# piezo-driver_v0_95-R004.net
KiCad netlist of a schematic drawn in EAGLE
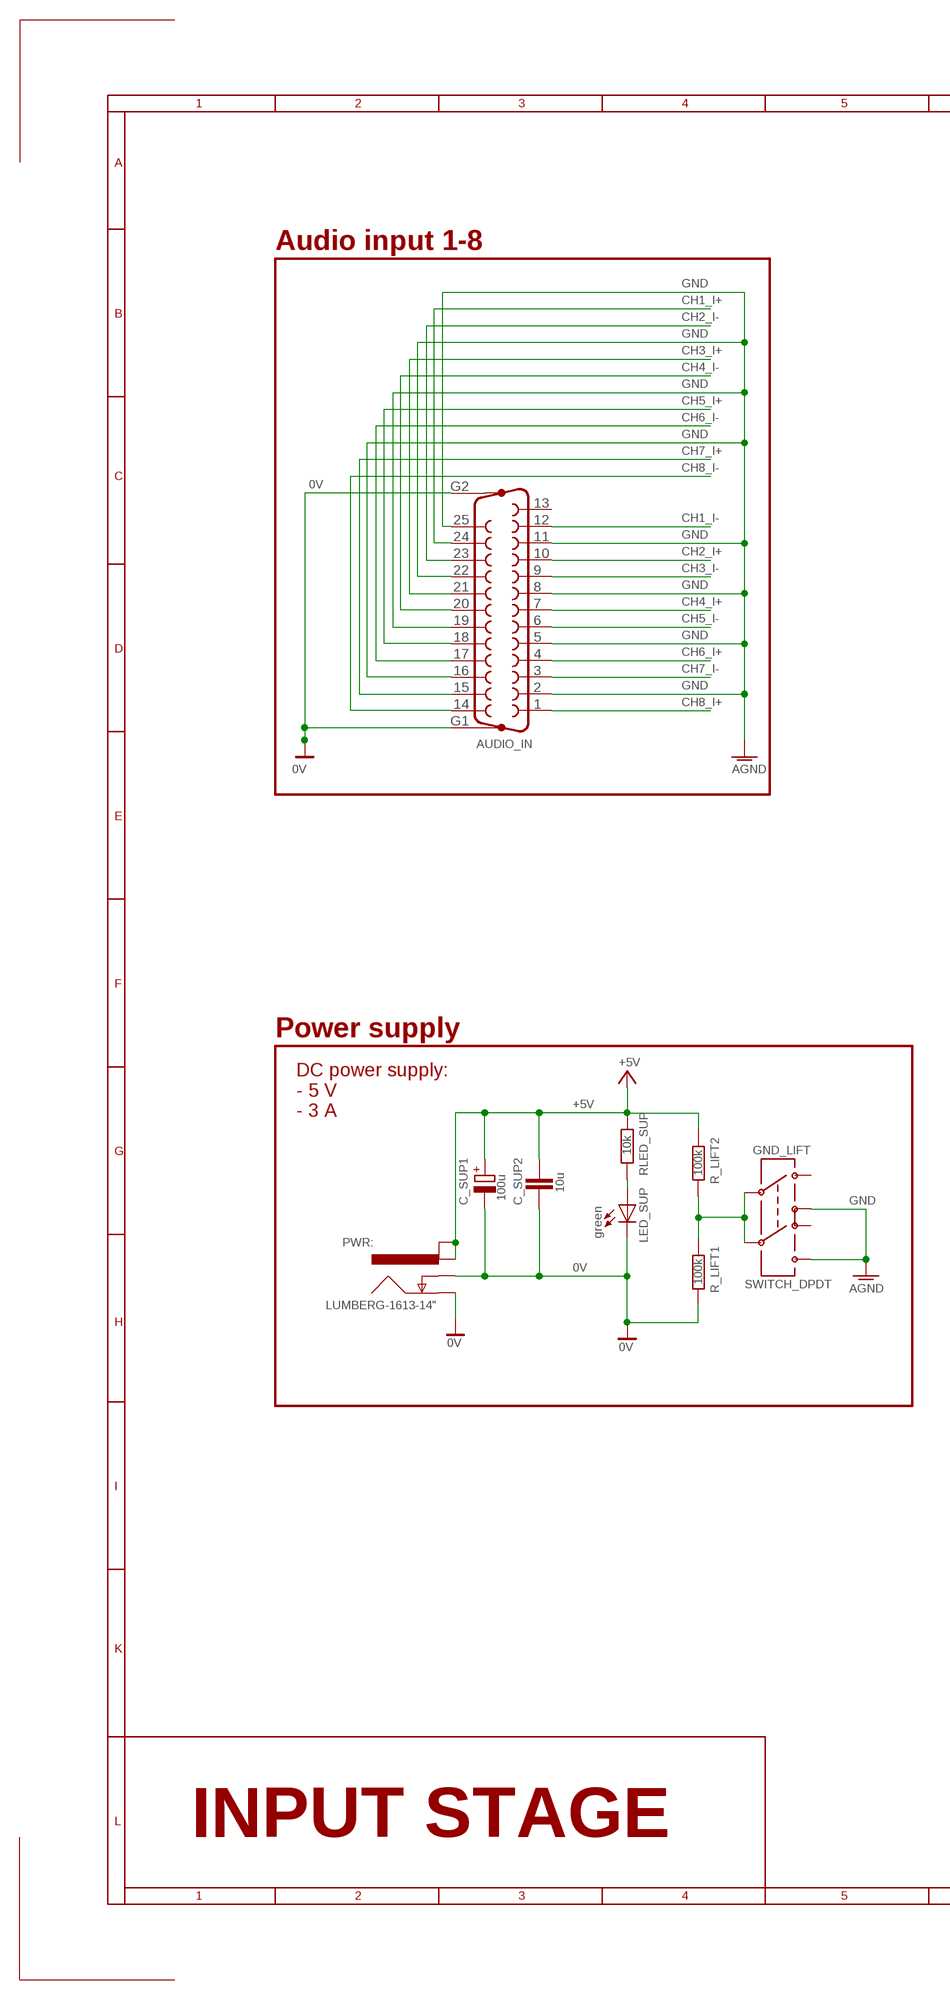
[diagram p0: schematic, sheet 1, part 1 of 2]
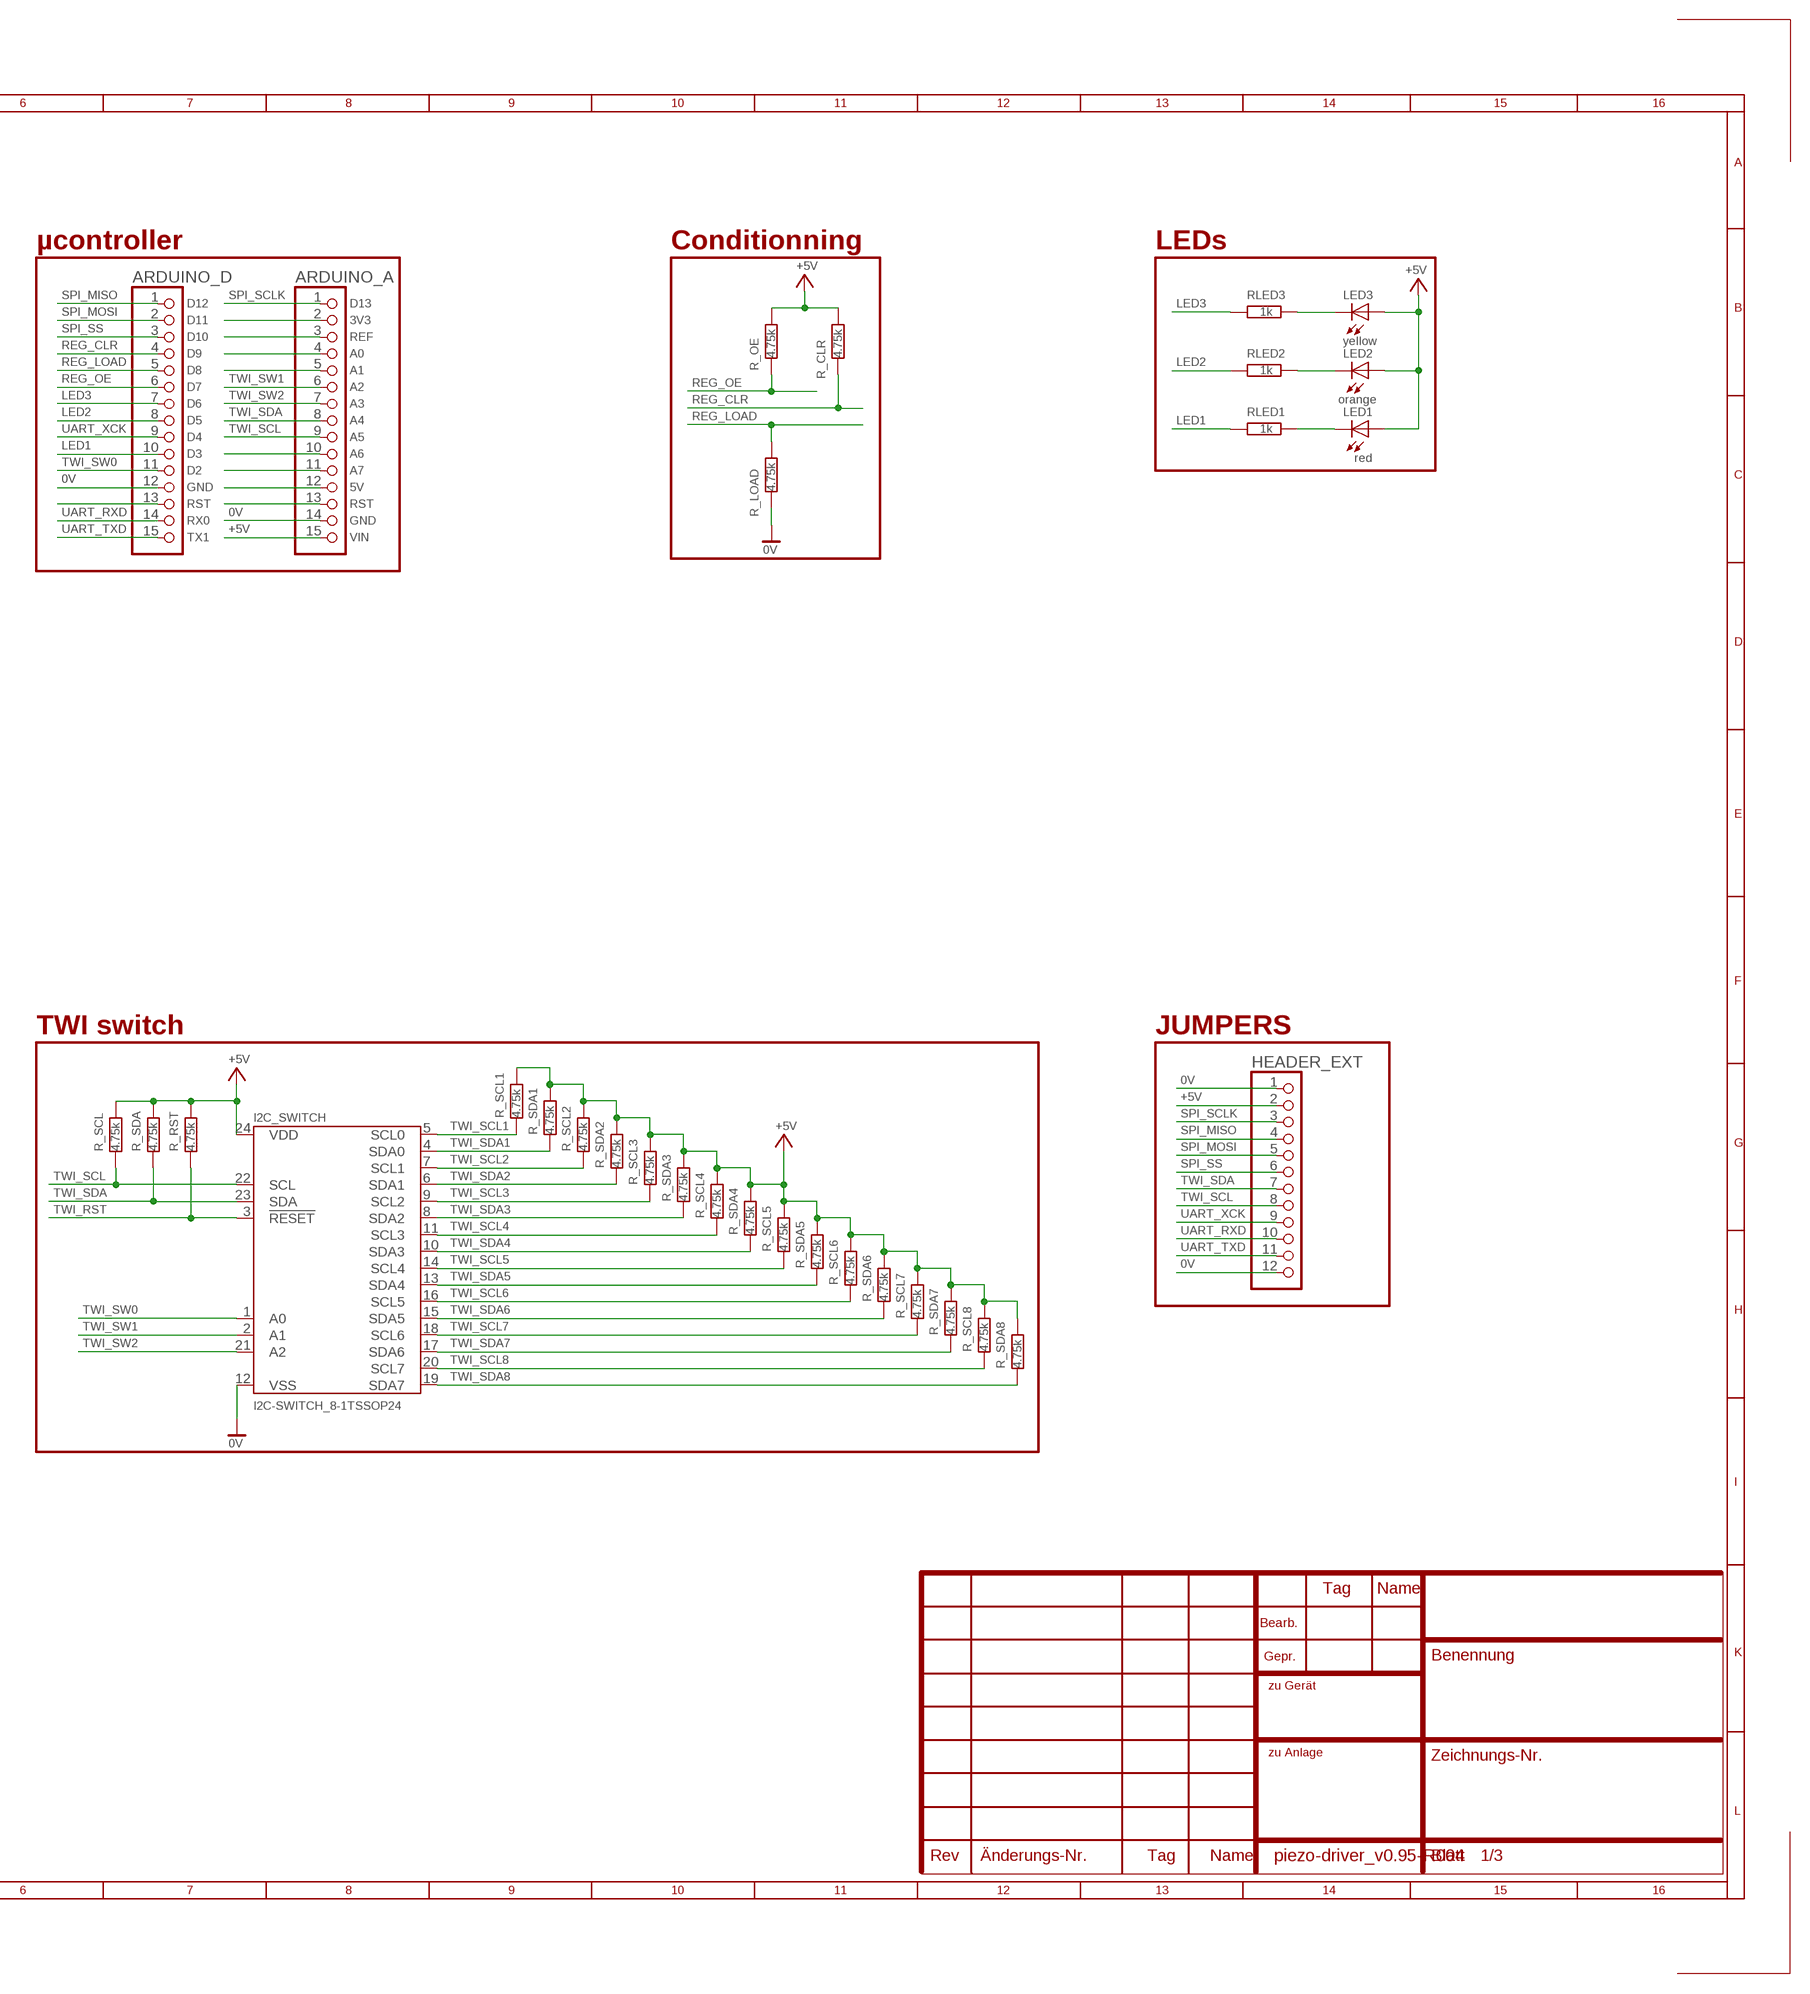
[diagram p1: schematic, sheet 1, part 2 of 2]
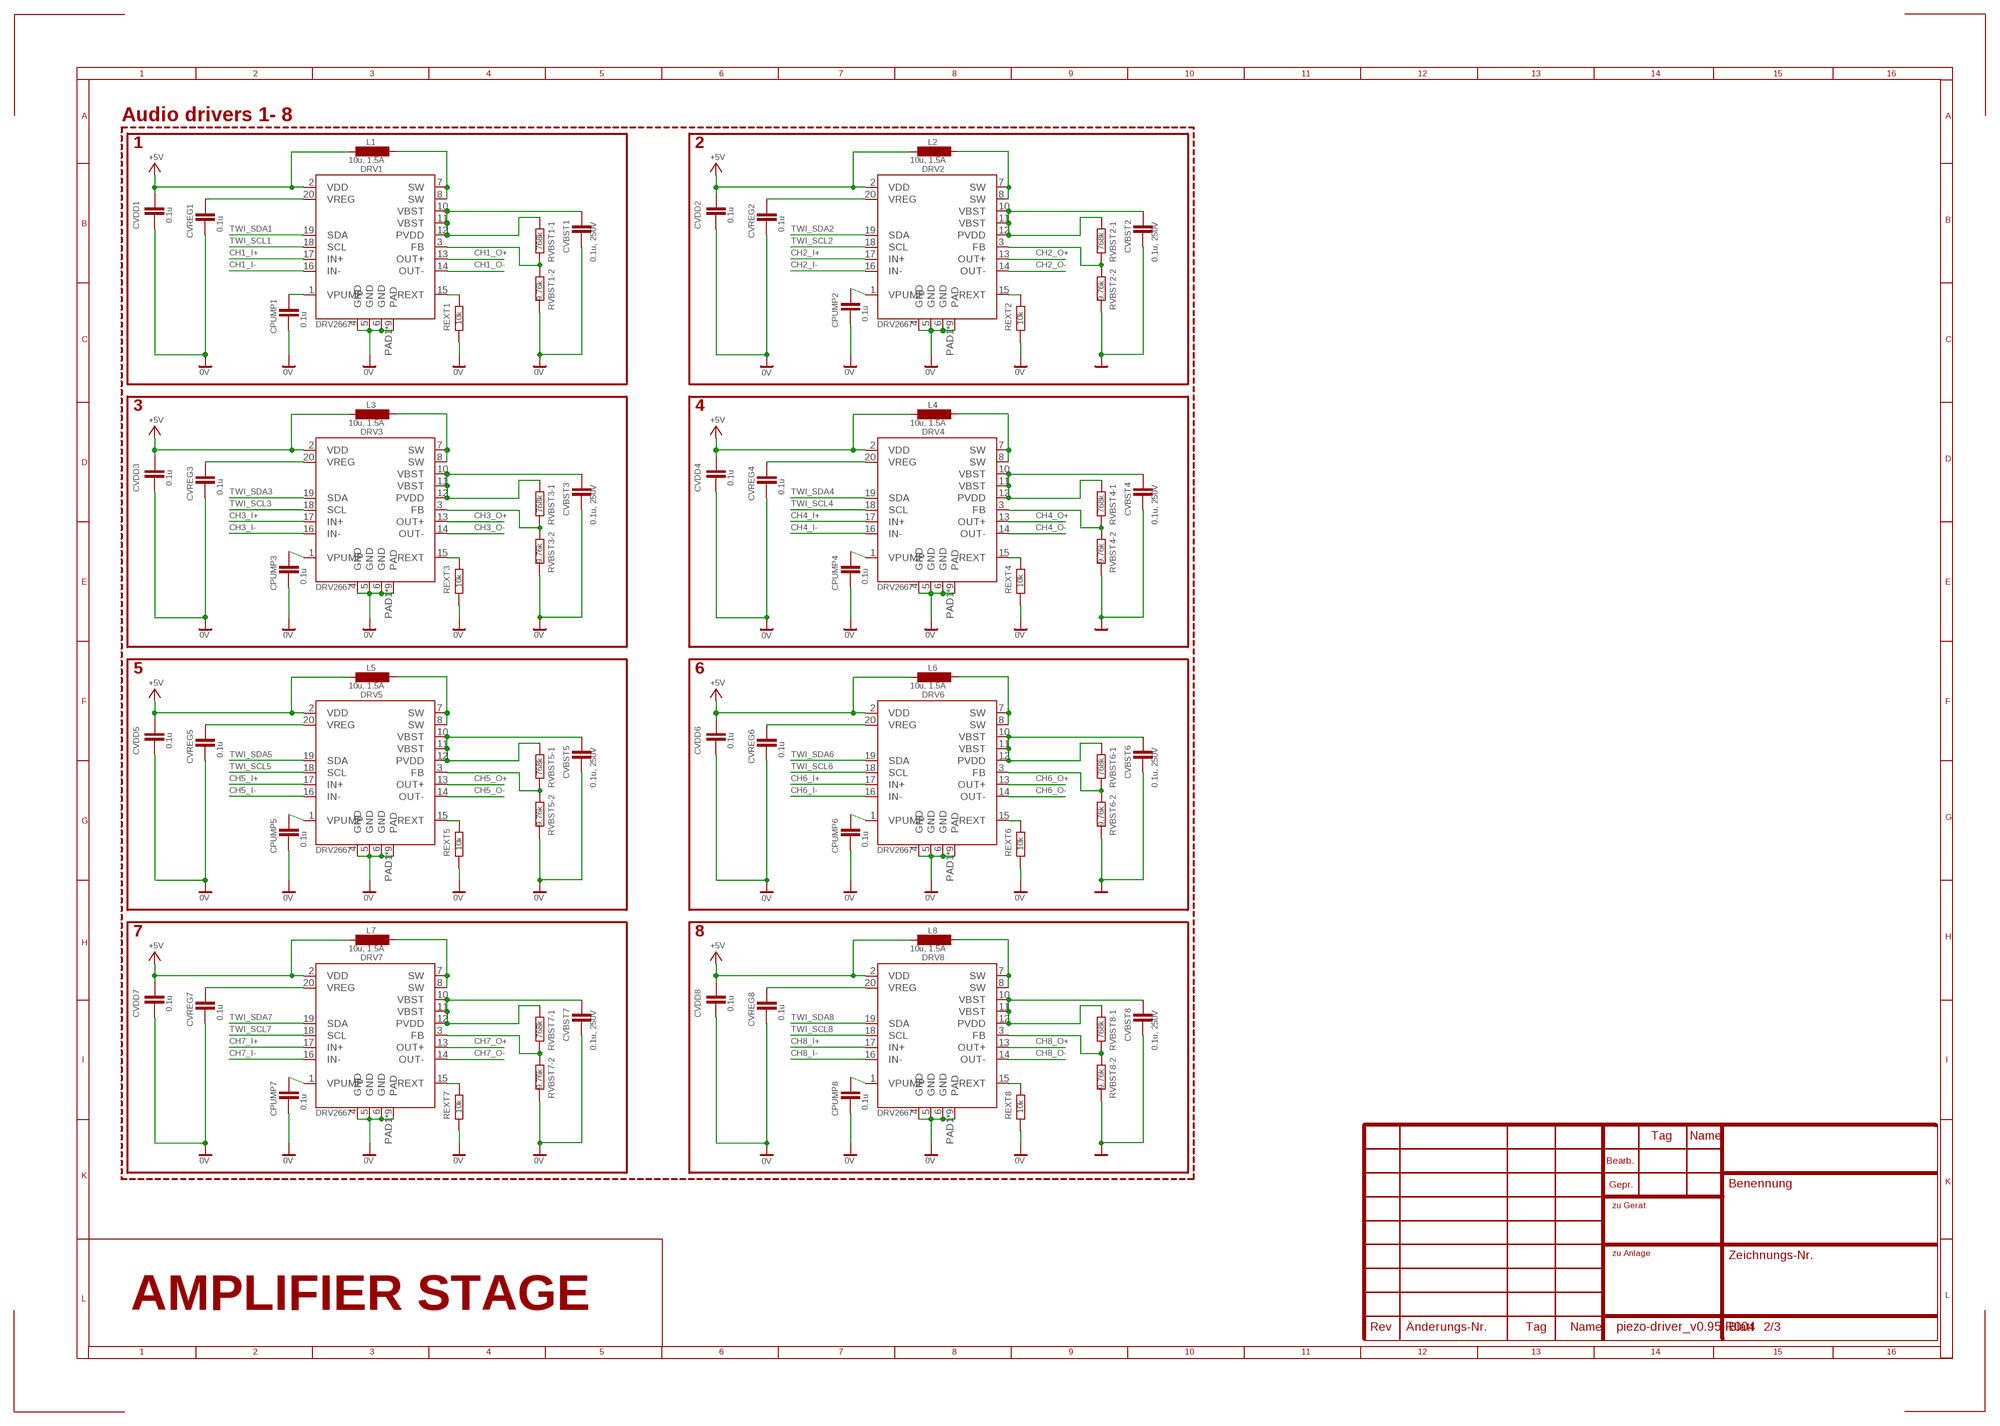
[diagram p2: schematic, sheet 2]
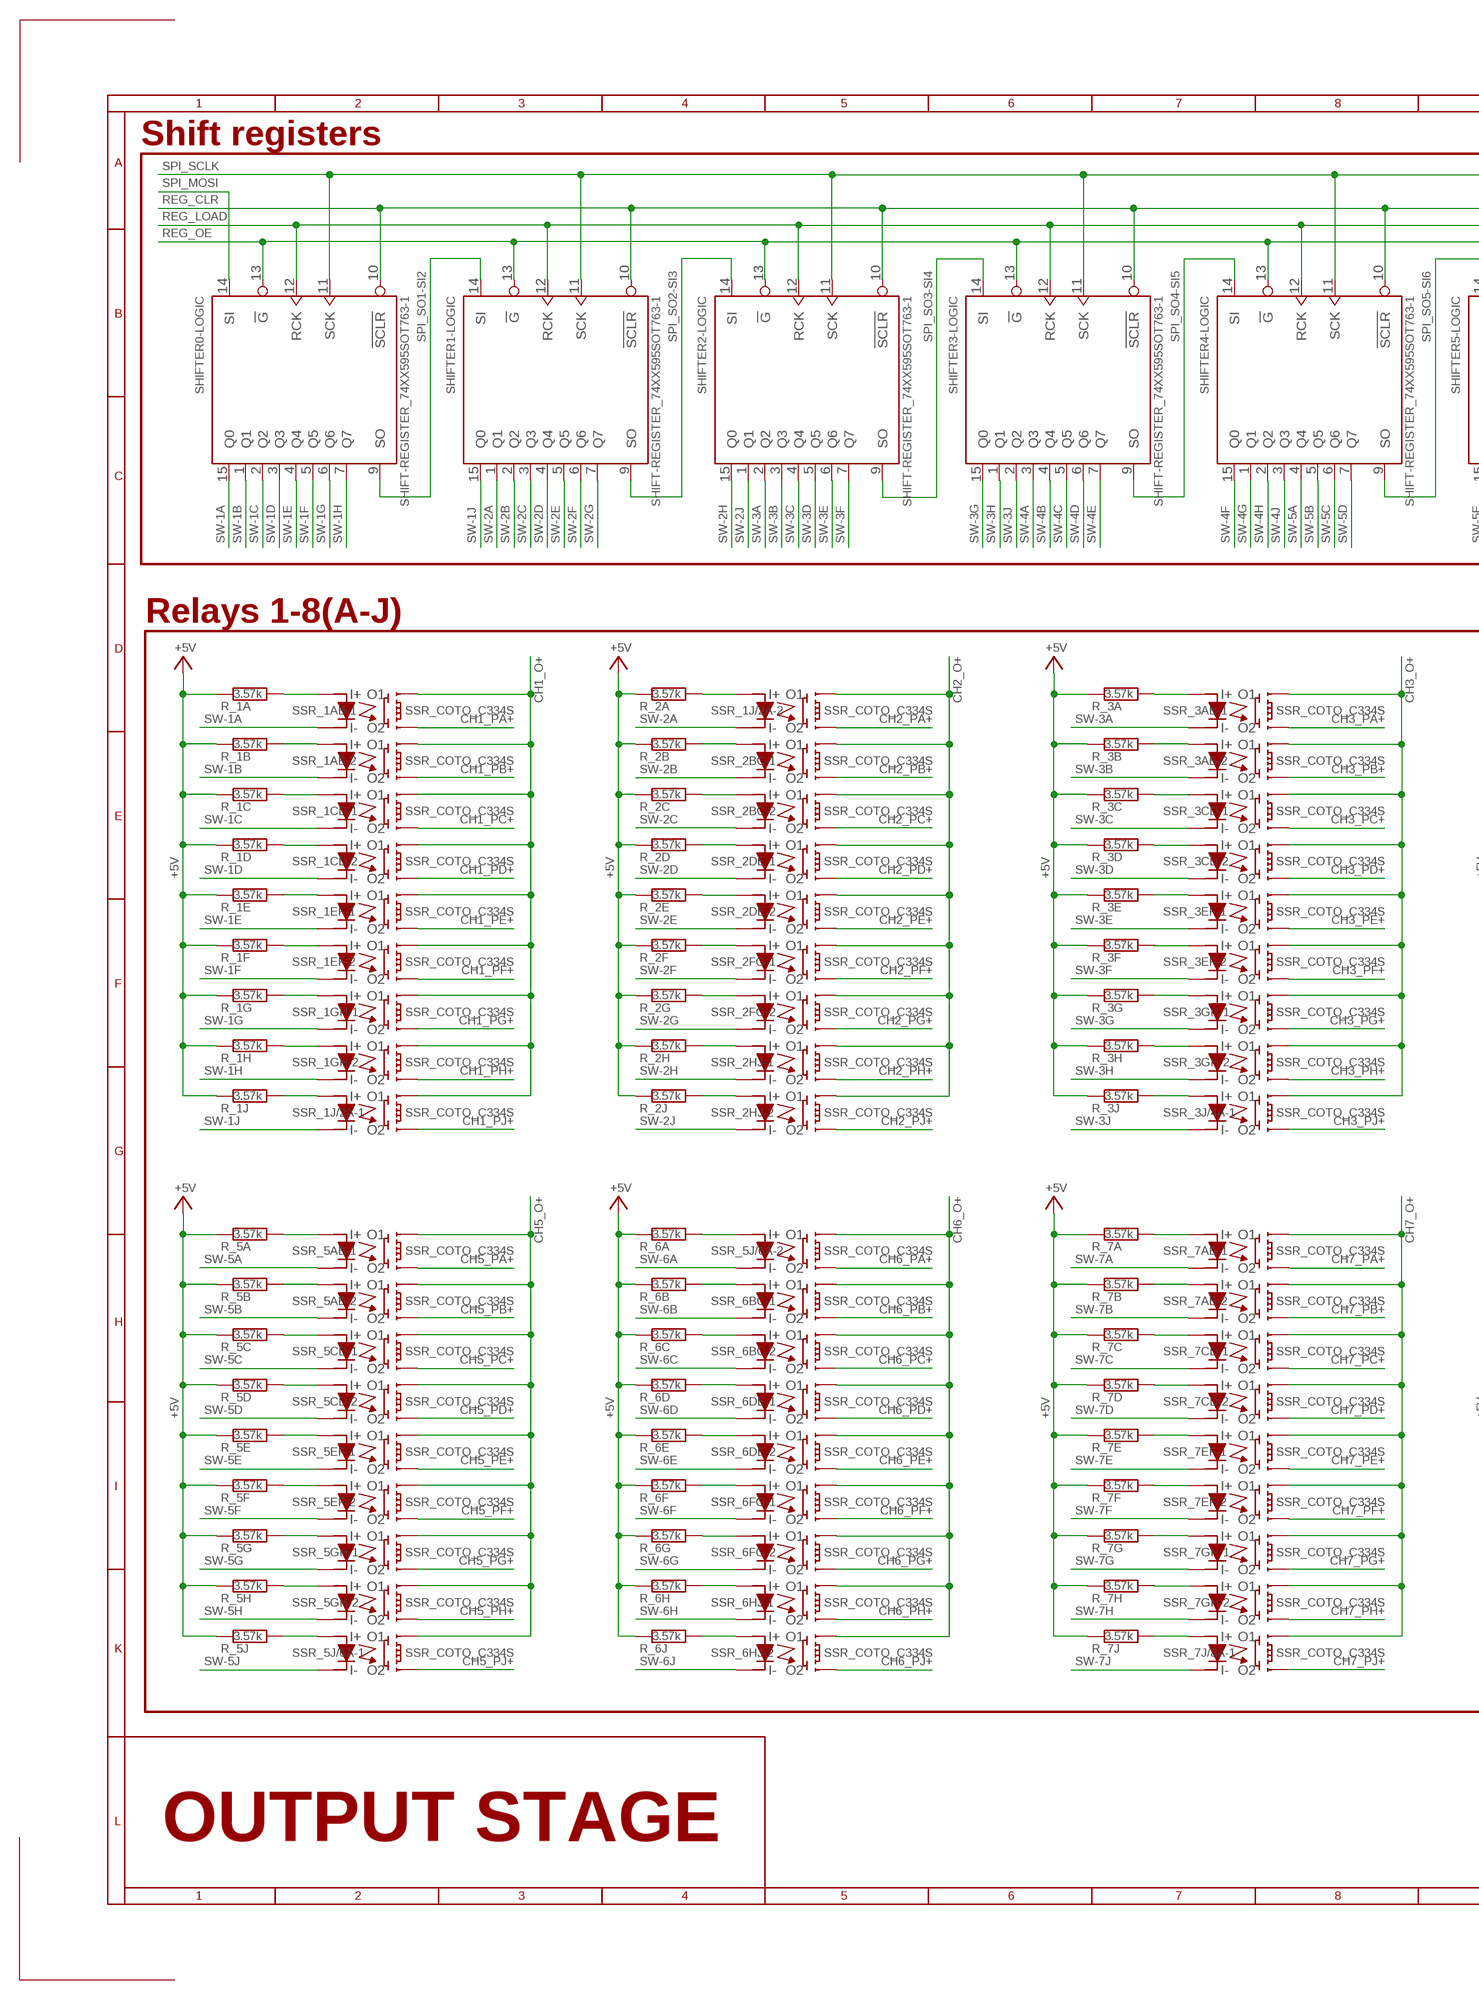
[diagram p3: schematic, sheet 3, part 1 of 2]
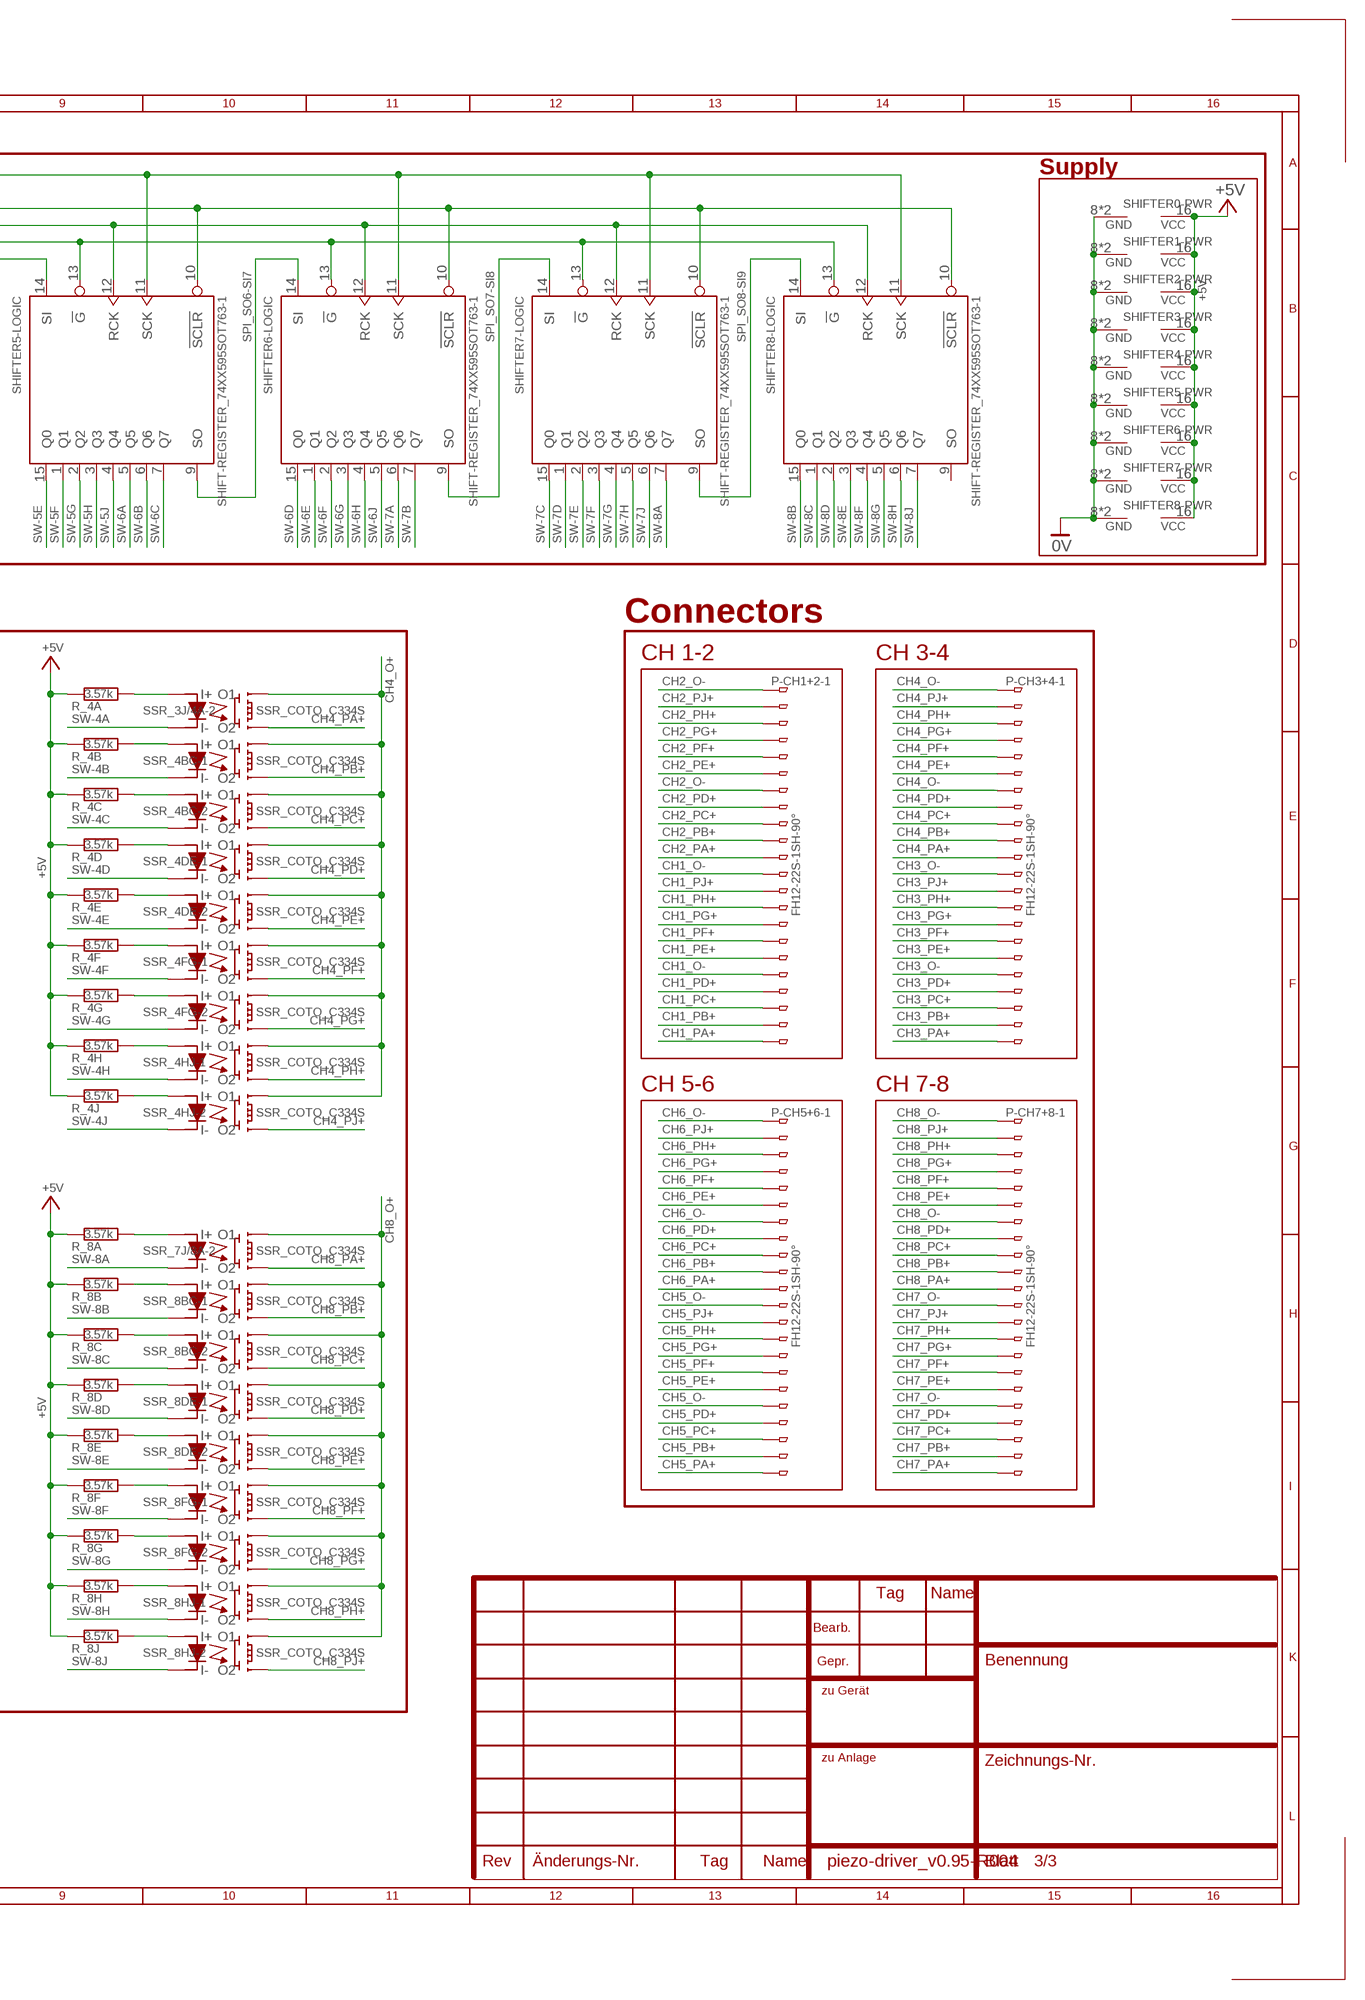
[diagram p4: schematic, sheet 3, part 2 of 2]

(export (version "E")
  (design (tool "Eeschema 10.0.6"))
  (components
    (comp (ref "CPUMP1")
      (value "0.1u")
      (footprint "eagle-import:C0402")
      (libsource (lib "eagle-import") (part "C-EUC0402"))
    )
    (comp (ref "CPUMP2")
      (value "0.1u")
      (footprint "eagle-import:C0402")
      (libsource (lib "eagle-import") (part "C-EUC0402"))
    )
    (comp (ref "CPUMP3")
      (value "0.1u")
      (footprint "eagle-import:C0402")
      (libsource (lib "eagle-import") (part "C-EUC0402"))
    )
    (comp (ref "CPUMP4")
      (value "0.1u")
      (footprint "eagle-import:C0402")
      (libsource (lib "eagle-import") (part "C-EUC0402"))
    )
    (comp (ref "CPUMP5")
      (value "0.1u")
      (footprint "eagle-import:C0402")
      (libsource (lib "eagle-import") (part "C-EUC0402"))
    )
    (comp (ref "CPUMP6")
      (value "0.1u")
      (footprint "eagle-import:C0402")
      (libsource (lib "eagle-import") (part "C-EUC0402"))
    )
    (comp (ref "CPUMP7")
      (value "0.1u")
      (footprint "eagle-import:C0402")
      (libsource (lib "eagle-import") (part "C-EUC0402"))
    )
    (comp (ref "CPUMP8")
      (value "0.1u")
      (footprint "eagle-import:C0402")
      (libsource (lib "eagle-import") (part "C-EUC0402"))
    )
    (comp (ref "CVBST1")
      (value "0.1u, 250V")
      (footprint "eagle-import:C0805")
      (libsource (lib "eagle-import") (part "C-EUC0805"))
    )
    (comp (ref "CVBST2")
      (value "0.1u, 250V")
      (footprint "eagle-import:C0805")
      (libsource (lib "eagle-import") (part "C-EUC0805"))
    )
    (comp (ref "CVBST3")
      (value "0.1u, 250V")
      (footprint "eagle-import:C0805")
      (libsource (lib "eagle-import") (part "C-EUC0805"))
    )
    (comp (ref "CVBST4")
      (value "0.1u, 250V")
      (footprint "eagle-import:C0805")
      (libsource (lib "eagle-import") (part "C-EUC0805"))
    )
    (comp (ref "CVBST5")
      (value "0.1u, 250V")
      (footprint "eagle-import:C0805")
      (libsource (lib "eagle-import") (part "C-EUC0805"))
    )
    (comp (ref "CVBST6")
      (value "0.1u, 250V")
      (footprint "eagle-import:C0805")
      (libsource (lib "eagle-import") (part "C-EUC0805"))
    )
    (comp (ref "CVBST7")
      (value "0.1u, 250V")
      (footprint "eagle-import:C0805")
      (libsource (lib "eagle-import") (part "C-EUC0805"))
    )
    (comp (ref "CVBST8")
      (value "0.1u, 250V")
      (footprint "eagle-import:C0805")
      (libsource (lib "eagle-import") (part "C-EUC0805"))
    )
    (comp (ref "CVDD1")
      (value "0.1u")
      (footprint "eagle-import:C0402")
      (libsource (lib "eagle-import") (part "C-EUC0402"))
    )
    (comp (ref "CVDD2")
      (value "0.1u")
      (footprint "eagle-import:C0402")
      (libsource (lib "eagle-import") (part "C-EUC0402"))
    )
    (comp (ref "CVDD3")
      (value "0.1u")
      (footprint "eagle-import:C0402")
      (libsource (lib "eagle-import") (part "C-EUC0402"))
    )
    (comp (ref "CVDD4")
      (value "0.1u")
      (footprint "eagle-import:C0402")
      (libsource (lib "eagle-import") (part "C-EUC0402"))
    )
    (comp (ref "CVDD5")
      (value "0.1u")
      (footprint "eagle-import:C0402")
      (libsource (lib "eagle-import") (part "C-EUC0402"))
    )
    (comp (ref "CVDD6")
      (value "0.1u")
      (footprint "eagle-import:C0402")
      (libsource (lib "eagle-import") (part "C-EUC0402"))
    )
    (comp (ref "CVDD7")
      (value "0.1u")
      (footprint "eagle-import:C0402")
      (libsource (lib "eagle-import") (part "C-EUC0402"))
    )
    (comp (ref "CVDD8")
      (value "0.1u")
      (footprint "eagle-import:C0402")
      (libsource (lib "eagle-import") (part "C-EUC0402"))
    )
    (comp (ref "CVREG1")
      (value "0.1u")
      (footprint "eagle-import:C0402")
      (libsource (lib "eagle-import") (part "C-EUC0402"))
    )
    (comp (ref "CVREG2")
      (value "0.1u")
      (footprint "eagle-import:C0402")
      (libsource (lib "eagle-import") (part "C-EUC0402"))
    )
    (comp (ref "CVREG3")
      (value "0.1u")
      (footprint "eagle-import:C0402")
      (libsource (lib "eagle-import") (part "C-EUC0402"))
    )
    (comp (ref "CVREG4")
      (value "0.1u")
      (footprint "eagle-import:C0402")
      (libsource (lib "eagle-import") (part "C-EUC0402"))
    )
    (comp (ref "CVREG5")
      (value "0.1u")
      (footprint "eagle-import:C0402")
      (libsource (lib "eagle-import") (part "C-EUC0402"))
    )
    (comp (ref "CVREG6")
      (value "0.1u")
      (footprint "eagle-import:C0402")
      (libsource (lib "eagle-import") (part "C-EUC0402"))
    )
    (comp (ref "CVREG7")
      (value "0.1u")
      (footprint "eagle-import:C0402")
      (libsource (lib "eagle-import") (part "C-EUC0402"))
    )
    (comp (ref "CVREG8")
      (value "0.1u")
      (footprint "eagle-import:C0402")
      (libsource (lib "eagle-import") (part "C-EUC0402"))
    )
    (comp (ref "DRV1")
      (value "DRV2667")
      (footprint "eagle-import:QFN-20_9TH")
      (libsource (lib "eagle-import") (part "DRV2667"))
    )
    (comp (ref "DRV2")
      (value "DRV2667")
      (footprint "eagle-import:QFN-20_9TH")
      (libsource (lib "eagle-import") (part "DRV2667"))
    )
    (comp (ref "DRV3")
      (value "DRV2667")
      (footprint "eagle-import:QFN-20_9TH")
      (libsource (lib "eagle-import") (part "DRV2667"))
    )
    (comp (ref "DRV4")
      (value "DRV2667")
      (footprint "eagle-import:QFN-20_9TH")
      (libsource (lib "eagle-import") (part "DRV2667"))
    )
    (comp (ref "DRV5")
      (value "DRV2667")
      (footprint "eagle-import:QFN-20_9TH")
      (libsource (lib "eagle-import") (part "DRV2667"))
    )
    (comp (ref "DRV6")
      (value "DRV2667")
      (footprint "eagle-import:QFN-20_9TH")
      (libsource (lib "eagle-import") (part "DRV2667"))
    )
    (comp (ref "DRV7")
      (value "DRV2667")
      (footprint "eagle-import:QFN-20_9TH")
      (libsource (lib "eagle-import") (part "DRV2667"))
    )
    (comp (ref "DRV8")
      (value "DRV2667")
      (footprint "eagle-import:QFN-20_9TH")
      (libsource (lib "eagle-import") (part "DRV2667"))
    )
    (comp (ref "L1")
      (value "10u, 1.5A")
      (footprint "eagle-import:L4.0X4.0")
      (libsource (lib "eagle-import") (part "L-EU4.0X4.0"))
    )
    (comp (ref "L2")
      (value "10u, 1.5A")
      (footprint "eagle-import:L4.0X4.0")
      (libsource (lib "eagle-import") (part "L-EU4.0X4.0"))
    )
    (comp (ref "L3")
      (value "10u, 1.5A")
      (footprint "eagle-import:L4.0X4.0")
      (libsource (lib "eagle-import") (part "L-EU4.0X4.0"))
    )
    (comp (ref "L4")
      (value "10u, 1.5A")
      (footprint "eagle-import:L4.0X4.0")
      (libsource (lib "eagle-import") (part "L-EU4.0X4.0"))
    )
    (comp (ref "L5")
      (value "10u, 1.5A")
      (footprint "eagle-import:L4.0X4.0")
      (libsource (lib "eagle-import") (part "L-EU4.0X4.0"))
    )
    (comp (ref "L6")
      (value "10u, 1.5A")
      (footprint "eagle-import:L4.0X4.0")
      (libsource (lib "eagle-import") (part "L-EU4.0X4.0"))
    )
    (comp (ref "L7")
      (value "10u, 1.5A")
      (footprint "eagle-import:L4.0X4.0")
      (libsource (lib "eagle-import") (part "L-EU4.0X4.0"))
    )
    (comp (ref "L8")
      (value "10u, 1.5A")
      (footprint "eagle-import:L4.0X4.0")
      (libsource (lib "eagle-import") (part "L-EU4.0X4.0"))
    )
    (comp (ref "REXT1")
      (value "10k")
      (footprint "eagle-import:R0402")
      (libsource (lib "eagle-import") (part "R-EU_R0402"))
    )
    (comp (ref "REXT2")
      (value "10k")
      (footprint "eagle-import:R0402")
      (libsource (lib "eagle-import") (part "R-EU_R0402"))
    )
    (comp (ref "REXT3")
      (value "10k")
      (footprint "eagle-import:R0402")
      (libsource (lib "eagle-import") (part "R-EU_R0402"))
    )
    (comp (ref "REXT4")
      (value "10k")
      (footprint "eagle-import:R0402")
      (libsource (lib "eagle-import") (part "R-EU_R0402"))
    )
    (comp (ref "REXT5")
      (value "10k")
      (footprint "eagle-import:R0402")
      (libsource (lib "eagle-import") (part "R-EU_R0402"))
    )
    (comp (ref "REXT6")
      (value "10k")
      (footprint "eagle-import:R0402")
      (libsource (lib "eagle-import") (part "R-EU_R0402"))
    )
    (comp (ref "REXT7")
      (value "10k")
      (footprint "eagle-import:R0402")
      (libsource (lib "eagle-import") (part "R-EU_R0402"))
    )
    (comp (ref "REXT8")
      (value "10k")
      (footprint "eagle-import:R0402")
      (libsource (lib "eagle-import") (part "R-EU_R0402"))
    )
    (comp (ref "RVBST1-1")
      (value "768k")
      (footprint "eagle-import:R0402")
      (libsource (lib "eagle-import") (part "R-EU_R0402"))
    )
    (comp (ref "RVBST1-2")
      (value "9.76k")
      (footprint "eagle-import:R0402")
      (libsource (lib "eagle-import") (part "R-EU_R0402"))
    )
    (comp (ref "RVBST2-1")
      (value "768k")
      (footprint "eagle-import:R0402")
      (libsource (lib "eagle-import") (part "R-EU_R0402"))
    )
    (comp (ref "RVBST2-2")
      (value "9.76k")
      (footprint "eagle-import:R0402")
      (libsource (lib "eagle-import") (part "R-EU_R0402"))
    )
    (comp (ref "RVBST3-1")
      (value "768k")
      (footprint "eagle-import:R0402")
      (libsource (lib "eagle-import") (part "R-EU_R0402"))
    )
    (comp (ref "RVBST3-2")
      (value "9.76k")
      (footprint "eagle-import:R0402")
      (libsource (lib "eagle-import") (part "R-EU_R0402"))
    )
    (comp (ref "RVBST4-1")
      (value "768k")
      (footprint "eagle-import:R0402")
      (libsource (lib "eagle-import") (part "R-EU_R0402"))
    )
    (comp (ref "RVBST4-2")
      (value "9.76k")
      (footprint "eagle-import:R0402")
      (libsource (lib "eagle-import") (part "R-EU_R0402"))
    )
    (comp (ref "RVBST5-1")
      (value "768k")
      (footprint "eagle-import:R0402")
      (libsource (lib "eagle-import") (part "R-EU_R0402"))
    )
    (comp (ref "RVBST5-2")
      (value "9.76k")
      (footprint "eagle-import:R0402")
      (libsource (lib "eagle-import") (part "R-EU_R0402"))
    )
    (comp (ref "RVBST6-1")
      (value "768k")
      (footprint "eagle-import:R0402")
      (libsource (lib "eagle-import") (part "R-EU_R0402"))
    )
    (comp (ref "RVBST6-2")
      (value "9.76k")
      (footprint "eagle-import:R0402")
      (libsource (lib "eagle-import") (part "R-EU_R0402"))
    )
    (comp (ref "RVBST7-1")
      (value "768k")
      (footprint "eagle-import:R0402")
      (libsource (lib "eagle-import") (part "R-EU_R0402"))
    )
    (comp (ref "RVBST7-2")
      (value "9.76k")
      (footprint "eagle-import:R0402")
      (libsource (lib "eagle-import") (part "R-EU_R0402"))
    )
    (comp (ref "RVBST8-1")
      (value "768k")
      (footprint "eagle-import:R0402")
      (libsource (lib "eagle-import") (part "R-EU_R0402"))
    )
    (comp (ref "RVBST8-2")
      (value "9.76k")
      (footprint "eagle-import:R0402")
      (libsource (lib "eagle-import") (part "R-EU_R0402"))
    )
    (comp (ref "P-CH1+2")
      (value "FH12-22S-1SH-90°")
      (footprint "eagle-import:FH12-22S-1SH")
      (libsource (lib "eagle-import") (part "FH12-22S-1SH-90°"))
    )
    (comp (ref "P-CH3+4")
      (value "FH12-22S-1SH-90°")
      (footprint "eagle-import:FH12-22S-1SH")
      (libsource (lib "eagle-import") (part "FH12-22S-1SH-90°"))
    )
    (comp (ref "P-CH5+6")
      (value "FH12-22S-1SH-90°")
      (footprint "eagle-import:FH12-22S-1SH")
      (libsource (lib "eagle-import") (part "FH12-22S-1SH-90°"))
    )
    (comp (ref "P-CH7+8")
      (value "FH12-22S-1SH-90°")
      (footprint "eagle-import:FH12-22S-1SH")
      (libsource (lib "eagle-import") (part "FH12-22S-1SH-90°"))
    )
    (comp (ref "R_1A")
      (value "3.57k")
      (footprint "eagle-import:R0402")
      (libsource (lib "eagle-import") (part "R-EU_R0402"))
    )
    (comp (ref "R_1B")
      (value "3.57k")
      (footprint "eagle-import:R0402")
      (libsource (lib "eagle-import") (part "R-EU_R0402"))
    )
    (comp (ref "R_1C")
      (value "3.57k")
      (footprint "eagle-import:R0402")
      (libsource (lib "eagle-import") (part "R-EU_R0402"))
    )
    (comp (ref "R_1D")
      (value "3.57k")
      (footprint "eagle-import:R0402")
      (libsource (lib "eagle-import") (part "R-EU_R0402"))
    )
    (comp (ref "R_1E")
      (value "3.57k")
      (footprint "eagle-import:R0402")
      (libsource (lib "eagle-import") (part "R-EU_R0402"))
    )
    (comp (ref "R_1F")
      (value "3.57k")
      (footprint "eagle-import:R0402")
      (libsource (lib "eagle-import") (part "R-EU_R0402"))
    )
    (comp (ref "R_1G")
      (value "3.57k")
      (footprint "eagle-import:R0402")
      (libsource (lib "eagle-import") (part "R-EU_R0402"))
    )
    (comp (ref "R_1H")
      (value "3.57k")
      (footprint "eagle-import:R0402")
      (libsource (lib "eagle-import") (part "R-EU_R0402"))
    )
    (comp (ref "R_1J")
      (value "3.57k")
      (footprint "eagle-import:R0402")
      (libsource (lib "eagle-import") (part "R-EU_R0402"))
    )
    (comp (ref "R_2A")
      (value "3.57k")
      (footprint "eagle-import:R0402")
      (libsource (lib "eagle-import") (part "R-EU_R0402"))
    )
    (comp (ref "R_2B")
      (value "3.57k")
      (footprint "eagle-import:R0402")
      (libsource (lib "eagle-import") (part "R-EU_R0402"))
    )
    (comp (ref "R_2C")
      (value "3.57k")
      (footprint "eagle-import:R0402")
      (libsource (lib "eagle-import") (part "R-EU_R0402"))
    )
    (comp (ref "R_2D")
      (value "3.57k")
      (footprint "eagle-import:R0402")
      (libsource (lib "eagle-import") (part "R-EU_R0402"))
    )
    (comp (ref "R_2E")
      (value "3.57k")
      (footprint "eagle-import:R0402")
      (libsource (lib "eagle-import") (part "R-EU_R0402"))
    )
    (comp (ref "R_2F")
      (value "3.57k")
      (footprint "eagle-import:R0402")
      (libsource (lib "eagle-import") (part "R-EU_R0402"))
    )
    (comp (ref "R_2G")
      (value "3.57k")
      (footprint "eagle-import:R0402")
      (libsource (lib "eagle-import") (part "R-EU_R0402"))
    )
    (comp (ref "R_2H")
      (value "3.57k")
      (footprint "eagle-import:R0402")
      (libsource (lib "eagle-import") (part "R-EU_R0402"))
    )
    (comp (ref "R_2J")
      (value "3.57k")
      (footprint "eagle-import:R0402")
      (libsource (lib "eagle-import") (part "R-EU_R0402"))
    )
    (comp (ref "R_3A")
      (value "3.57k")
      (footprint "eagle-import:R0402")
      (libsource (lib "eagle-import") (part "R-EU_R0402"))
    )
    (comp (ref "R_3B")
      (value "3.57k")
      (footprint "eagle-import:R0402")
      (libsource (lib "eagle-import") (part "R-EU_R0402"))
    )
    (comp (ref "R_3C")
      (value "3.57k")
      (footprint "eagle-import:R0402")
      (libsource (lib "eagle-import") (part "R-EU_R0402"))
    )
    (comp (ref "R_3D")
      (value "3.57k")
      (footprint "eagle-import:R0402")
      (libsource (lib "eagle-import") (part "R-EU_R0402"))
    )
    (comp (ref "R_3E")
      (value "3.57k")
      (footprint "eagle-import:R0402")
      (libsource (lib "eagle-import") (part "R-EU_R0402"))
    )
    (comp (ref "R_3F")
      (value "3.57k")
      (footprint "eagle-import:R0402")
      (libsource (lib "eagle-import") (part "R-EU_R0402"))
    )
    (comp (ref "R_3G")
      (value "3.57k")
      (footprint "eagle-import:R0402")
      (libsource (lib "eagle-import") (part "R-EU_R0402"))
    )
    (comp (ref "R_3H")
      (value "3.57k")
      (footprint "eagle-import:R0402")
      (libsource (lib "eagle-import") (part "R-EU_R0402"))
    )
    (comp (ref "R_3J")
      (value "3.57k")
      (footprint "eagle-import:R0402")
      (libsource (lib "eagle-import") (part "R-EU_R0402"))
    )
    (comp (ref "R_4A")
      (value "3.57k")
      (footprint "eagle-import:R0402")
      (libsource (lib "eagle-import") (part "R-EU_R0402"))
    )
    (comp (ref "R_4B")
      (value "3.57k")
      (footprint "eagle-import:R0402")
      (libsource (lib "eagle-import") (part "R-EU_R0402"))
    )
    (comp (ref "R_4C")
      (value "3.57k")
      (footprint "eagle-import:R0402")
      (libsource (lib "eagle-import") (part "R-EU_R0402"))
    )
    (comp (ref "R_4D")
      (value "3.57k")
      (footprint "eagle-import:R0402")
      (libsource (lib "eagle-import") (part "R-EU_R0402"))
    )
    (comp (ref "R_4E")
      (value "3.57k")
      (footprint "eagle-import:R0402")
      (libsource (lib "eagle-import") (part "R-EU_R0402"))
    )
    (comp (ref "R_4F")
      (value "3.57k")
      (footprint "eagle-import:R0402")
      (libsource (lib "eagle-import") (part "R-EU_R0402"))
    )
    (comp (ref "R_4G")
      (value "3.57k")
      (footprint "eagle-import:R0402")
      (libsource (lib "eagle-import") (part "R-EU_R0402"))
    )
    (comp (ref "R_4H")
      (value "3.57k")
      (footprint "eagle-import:R0402")
      (libsource (lib "eagle-import") (part "R-EU_R0402"))
    )
    (comp (ref "R_4J")
      (value "3.57k")
      (footprint "eagle-import:R0402")
      (libsource (lib "eagle-import") (part "R-EU_R0402"))
    )
    (comp (ref "R_5A")
      (value "3.57k")
      (footprint "eagle-import:R0402")
      (libsource (lib "eagle-import") (part "R-EU_R0402"))
    )
    (comp (ref "R_5B")
      (value "3.57k")
      (footprint "eagle-import:R0402")
      (libsource (lib "eagle-import") (part "R-EU_R0402"))
    )
    (comp (ref "R_5C")
      (value "3.57k")
      (footprint "eagle-import:R0402")
      (libsource (lib "eagle-import") (part "R-EU_R0402"))
    )
    (comp (ref "R_5D")
      (value "3.57k")
      (footprint "eagle-import:R0402")
      (libsource (lib "eagle-import") (part "R-EU_R0402"))
    )
    (comp (ref "R_5E")
      (value "3.57k")
      (footprint "eagle-import:R0402")
      (libsource (lib "eagle-import") (part "R-EU_R0402"))
    )
    (comp (ref "R_5F")
      (value "3.57k")
      (footprint "eagle-import:R0402")
      (libsource (lib "eagle-import") (part "R-EU_R0402"))
    )
    (comp (ref "R_5G")
      (value "3.57k")
      (footprint "eagle-import:R0402")
      (libsource (lib "eagle-import") (part "R-EU_R0402"))
    )
    (comp (ref "R_5H")
      (value "3.57k")
      (footprint "eagle-import:R0402")
      (libsource (lib "eagle-import") (part "R-EU_R0402"))
    )
    (comp (ref "R_5J")
      (value "3.57k")
      (footprint "eagle-import:R0402")
      (libsource (lib "eagle-import") (part "R-EU_R0402"))
    )
    (comp (ref "R_6A")
      (value "3.57k")
      (footprint "eagle-import:R0402")
      (libsource (lib "eagle-import") (part "R-EU_R0402"))
    )
    (comp (ref "R_6B")
      (value "3.57k")
      (footprint "eagle-import:R0402")
      (libsource (lib "eagle-import") (part "R-EU_R0402"))
    )
    (comp (ref "R_6C")
      (value "3.57k")
      (footprint "eagle-import:R0402")
      (libsource (lib "eagle-import") (part "R-EU_R0402"))
    )
    (comp (ref "R_6D")
      (value "3.57k")
      (footprint "eagle-import:R0402")
      (libsource (lib "eagle-import") (part "R-EU_R0402"))
    )
    (comp (ref "R_6E")
      (value "3.57k")
      (footprint "eagle-import:R0402")
      (libsource (lib "eagle-import") (part "R-EU_R0402"))
    )
    (comp (ref "R_6F")
      (value "3.57k")
      (footprint "eagle-import:R0402")
      (libsource (lib "eagle-import") (part "R-EU_R0402"))
    )
    (comp (ref "R_6G")
      (value "3.57k")
      (footprint "eagle-import:R0402")
      (libsource (lib "eagle-import") (part "R-EU_R0402"))
    )
    (comp (ref "R_6H")
      (value "3.57k")
      (footprint "eagle-import:R0402")
      (libsource (lib "eagle-import") (part "R-EU_R0402"))
    )
    (comp (ref "R_6J")
      (value "3.57k")
      (footprint "eagle-import:R0402")
      (libsource (lib "eagle-import") (part "R-EU_R0402"))
    )
    (comp (ref "R_7A")
      (value "3.57k")
      (footprint "eagle-import:R0402")
      (libsource (lib "eagle-import") (part "R-EU_R0402"))
    )
    (comp (ref "R_7B")
      (value "3.57k")
      (footprint "eagle-import:R0402")
      (libsource (lib "eagle-import") (part "R-EU_R0402"))
    )
    (comp (ref "R_7C")
      (value "3.57k")
      (footprint "eagle-import:R0402")
      (libsource (lib "eagle-import") (part "R-EU_R0402"))
    )
    (comp (ref "R_7D")
      (value "3.57k")
      (footprint "eagle-import:R0402")
      (libsource (lib "eagle-import") (part "R-EU_R0402"))
    )
    (comp (ref "R_7E")
      (value "3.57k")
      (footprint "eagle-import:R0402")
      (libsource (lib "eagle-import") (part "R-EU_R0402"))
    )
    (comp (ref "R_7F")
      (value "3.57k")
      (footprint "eagle-import:R0402")
      (libsource (lib "eagle-import") (part "R-EU_R0402"))
    )
    (comp (ref "R_7G")
      (value "3.57k")
      (footprint "eagle-import:R0402")
      (libsource (lib "eagle-import") (part "R-EU_R0402"))
    )
    (comp (ref "R_7H")
      (value "3.57k")
      (footprint "eagle-import:R0402")
      (libsource (lib "eagle-import") (part "R-EU_R0402"))
    )
    (comp (ref "R_7J")
      (value "3.57k")
      (footprint "eagle-import:R0402")
      (libsource (lib "eagle-import") (part "R-EU_R0402"))
    )
    (comp (ref "R_8A")
      (value "3.57k")
      (footprint "eagle-import:R0402")
      (libsource (lib "eagle-import") (part "R-EU_R0402"))
    )
    (comp (ref "R_8B")
      (value "3.57k")
      (footprint "eagle-import:R0402")
      (libsource (lib "eagle-import") (part "R-EU_R0402"))
    )
    (comp (ref "R_8C")
      (value "3.57k")
      (footprint "eagle-import:R0402")
      (libsource (lib "eagle-import") (part "R-EU_R0402"))
    )
    (comp (ref "R_8D")
      (value "3.57k")
      (footprint "eagle-import:R0402")
      (libsource (lib "eagle-import") (part "R-EU_R0402"))
    )
    (comp (ref "R_8E")
      (value "3.57k")
      (footprint "eagle-import:R0402")
      (libsource (lib "eagle-import") (part "R-EU_R0402"))
    )
    (comp (ref "R_8F")
      (value "3.57k")
      (footprint "eagle-import:R0402")
      (libsource (lib "eagle-import") (part "R-EU_R0402"))
    )
    (comp (ref "R_8G")
      (value "3.57k")
      (footprint "eagle-import:R0402")
      (libsource (lib "eagle-import") (part "R-EU_R0402"))
    )
    (comp (ref "R_8H")
      (value "3.57k")
      (footprint "eagle-import:R0402")
      (libsource (lib "eagle-import") (part "R-EU_R0402"))
    )
    (comp (ref "R_8J")
      (value "3.57k")
      (footprint "eagle-import:R0402")
      (libsource (lib "eagle-import") (part "R-EU_R0402"))
    )
    (comp (ref "SHIFTER0")
      (value "SHIFT-REGISTER_74XX595SOT763-1")
      (footprint "eagle-import:SOT763-1")
      (libsource (lib "eagle-import") (part "SHIFT-REGISTER_74XX595SOT763-1"))
    )
    (comp (ref "SHIFTER1")
      (value "SHIFT-REGISTER_74XX595SOT763-1")
      (footprint "eagle-import:SOT763-1")
      (libsource (lib "eagle-import") (part "SHIFT-REGISTER_74XX595SOT763-1"))
    )
    (comp (ref "SHIFTER2")
      (value "SHIFT-REGISTER_74XX595SOT763-1")
      (footprint "eagle-import:SOT763-1")
      (libsource (lib "eagle-import") (part "SHIFT-REGISTER_74XX595SOT763-1"))
    )
    (comp (ref "SHIFTER3")
      (value "SHIFT-REGISTER_74XX595SOT763-1")
      (footprint "eagle-import:SOT763-1")
      (libsource (lib "eagle-import") (part "SHIFT-REGISTER_74XX595SOT763-1"))
    )
    (comp (ref "SHIFTER4")
      (value "SHIFT-REGISTER_74XX595SOT763-1")
      (footprint "eagle-import:SOT763-1")
      (libsource (lib "eagle-import") (part "SHIFT-REGISTER_74XX595SOT763-1"))
    )
    (comp (ref "SHIFTER5")
      (value "SHIFT-REGISTER_74XX595SOT763-1")
      (footprint "eagle-import:SOT763-1")
      (libsource (lib "eagle-import") (part "SHIFT-REGISTER_74XX595SOT763-1"))
    )
    (comp (ref "SHIFTER6")
      (value "SHIFT-REGISTER_74XX595SOT763-1")
      (footprint "eagle-import:SOT763-1")
      (libsource (lib "eagle-import") (part "SHIFT-REGISTER_74XX595SOT763-1"))
    )
    (comp (ref "SHIFTER7")
      (value "SHIFT-REGISTER_74XX595SOT763-1")
      (footprint "eagle-import:SOT763-1")
      (libsource (lib "eagle-import") (part "SHIFT-REGISTER_74XX595SOT763-1"))
    )
    (comp (ref "SHIFTER8")
      (value "SHIFT-REGISTER_74XX595SOT763-1")
      (footprint "eagle-import:SOT763-1")
      (libsource (lib "eagle-import") (part "SHIFT-REGISTER_74XX595SOT763-1"))
    )
    (comp (ref "SSR_1AB")
      (value "SSR_COTO_C334S")
      (footprint "eagle-import:SOP8")
      (libsource (lib "eagle-import") (part "SSR_COTO_C334S"))
    )
    (comp (ref "SSR_1CD")
      (value "SSR_COTO_C334S")
      (footprint "eagle-import:SOP8")
      (libsource (lib "eagle-import") (part "SSR_COTO_C334S"))
    )
    (comp (ref "SSR_1EF")
      (value "SSR_COTO_C334S")
      (footprint "eagle-import:SOP8")
      (libsource (lib "eagle-import") (part "SSR_COTO_C334S"))
    )
    (comp (ref "SSR_1GH")
      (value "SSR_COTO_C334S")
      (footprint "eagle-import:SOP8")
      (libsource (lib "eagle-import") (part "SSR_COTO_C334S"))
    )
    (comp (ref "SSR_1J/2A")
      (value "SSR_COTO_C334S")
      (footprint "eagle-import:SOP8")
      (libsource (lib "eagle-import") (part "SSR_COTO_C334S"))
    )
    (comp (ref "SSR_2BC")
      (value "SSR_COTO_C334S")
      (footprint "eagle-import:SOP8")
      (libsource (lib "eagle-import") (part "SSR_COTO_C334S"))
    )
    (comp (ref "SSR_2DE")
      (value "SSR_COTO_C334S")
      (footprint "eagle-import:SOP8")
      (libsource (lib "eagle-import") (part "SSR_COTO_C334S"))
    )
    (comp (ref "SSR_2FG")
      (value "SSR_COTO_C334S")
      (footprint "eagle-import:SOP8")
      (libsource (lib "eagle-import") (part "SSR_COTO_C334S"))
    )
    (comp (ref "SSR_2HJ")
      (value "SSR_COTO_C334S")
      (footprint "eagle-import:SOP8")
      (libsource (lib "eagle-import") (part "SSR_COTO_C334S"))
    )
    (comp (ref "SSR_3AB")
      (value "SSR_COTO_C334S")
      (footprint "eagle-import:SOP8")
      (libsource (lib "eagle-import") (part "SSR_COTO_C334S"))
    )
    (comp (ref "SSR_3CD")
      (value "SSR_COTO_C334S")
      (footprint "eagle-import:SOP8")
      (libsource (lib "eagle-import") (part "SSR_COTO_C334S"))
    )
    (comp (ref "SSR_3EF")
      (value "SSR_COTO_C334S")
      (footprint "eagle-import:SOP8")
      (libsource (lib "eagle-import") (part "SSR_COTO_C334S"))
    )
    (comp (ref "SSR_3GH")
      (value "SSR_COTO_C334S")
      (footprint "eagle-import:SOP8")
      (libsource (lib "eagle-import") (part "SSR_COTO_C334S"))
    )
    (comp (ref "SSR_3J/4A")
      (value "SSR_COTO_C334S")
      (footprint "eagle-import:SOP8")
      (libsource (lib "eagle-import") (part "SSR_COTO_C334S"))
    )
    (comp (ref "SSR_4BC")
      (value "SSR_COTO_C334S")
      (footprint "eagle-import:SOP8")
      (libsource (lib "eagle-import") (part "SSR_COTO_C334S"))
    )
    (comp (ref "SSR_4DE")
      (value "SSR_COTO_C334S")
      (footprint "eagle-import:SOP8")
      (libsource (lib "eagle-import") (part "SSR_COTO_C334S"))
    )
    (comp (ref "SSR_4FG")
      (value "SSR_COTO_C334S")
      (footprint "eagle-import:SOP8")
      (libsource (lib "eagle-import") (part "SSR_COTO_C334S"))
    )
    (comp (ref "SSR_4HJ")
      (value "SSR_COTO_C334S")
      (footprint "eagle-import:SOP8")
      (libsource (lib "eagle-import") (part "SSR_COTO_C334S"))
    )
    (comp (ref "SSR_5AB")
      (value "SSR_COTO_C334S")
      (footprint "eagle-import:SOP8")
      (libsource (lib "eagle-import") (part "SSR_COTO_C334S"))
    )
    (comp (ref "SSR_5CD")
      (value "SSR_COTO_C334S")
      (footprint "eagle-import:SOP8")
      (libsource (lib "eagle-import") (part "SSR_COTO_C334S"))
    )
    (comp (ref "SSR_5EF")
      (value "SSR_COTO_C334S")
      (footprint "eagle-import:SOP8")
      (libsource (lib "eagle-import") (part "SSR_COTO_C334S"))
    )
    (comp (ref "SSR_5GH")
      (value "SSR_COTO_C334S")
      (footprint "eagle-import:SOP8")
      (libsource (lib "eagle-import") (part "SSR_COTO_C334S"))
    )
    (comp (ref "SSR_5J/6A")
      (value "SSR_COTO_C334S")
      (footprint "eagle-import:SOP8")
      (libsource (lib "eagle-import") (part "SSR_COTO_C334S"))
    )
    (comp (ref "SSR_6BC")
      (value "SSR_COTO_C334S")
      (footprint "eagle-import:SOP8")
      (libsource (lib "eagle-import") (part "SSR_COTO_C334S"))
    )
    (comp (ref "SSR_6DE")
      (value "SSR_COTO_C334S")
      (footprint "eagle-import:SOP8")
      (libsource (lib "eagle-import") (part "SSR_COTO_C334S"))
    )
    (comp (ref "SSR_6FG")
      (value "SSR_COTO_C334S")
      (footprint "eagle-import:SOP8")
      (libsource (lib "eagle-import") (part "SSR_COTO_C334S"))
    )
    (comp (ref "SSR_6HJ")
      (value "SSR_COTO_C334S")
      (footprint "eagle-import:SOP8")
      (libsource (lib "eagle-import") (part "SSR_COTO_C334S"))
    )
    (comp (ref "SSR_7AB")
      (value "SSR_COTO_C334S")
      (footprint "eagle-import:SOP8")
      (libsource (lib "eagle-import") (part "SSR_COTO_C334S"))
    )
    (comp (ref "SSR_7CD")
      (value "SSR_COTO_C334S")
      (footprint "eagle-import:SOP8")
      (libsource (lib "eagle-import") (part "SSR_COTO_C334S"))
    )
    (comp (ref "SSR_7EF")
      (value "SSR_COTO_C334S")
      (footprint "eagle-import:SOP8")
      (libsource (lib "eagle-import") (part "SSR_COTO_C334S"))
    )
    (comp (ref "SSR_7GH")
      (value "SSR_COTO_C334S")
      (footprint "eagle-import:SOP8")
      (libsource (lib "eagle-import") (part "SSR_COTO_C334S"))
    )
    (comp (ref "SSR_7J/8A")
      (value "SSR_COTO_C334S")
      (footprint "eagle-import:SOP8")
      (libsource (lib "eagle-import") (part "SSR_COTO_C334S"))
    )
    (comp (ref "SSR_8BC")
      (value "SSR_COTO_C334S")
      (footprint "eagle-import:SOP8")
      (libsource (lib "eagle-import") (part "SSR_COTO_C334S"))
    )
    (comp (ref "SSR_8DE")
      (value "SSR_COTO_C334S")
      (footprint "eagle-import:SOP8")
      (libsource (lib "eagle-import") (part "SSR_COTO_C334S"))
    )
    (comp (ref "SSR_8FG")
      (value "SSR_COTO_C334S")
      (footprint "eagle-import:SOP8")
      (libsource (lib "eagle-import") (part "SSR_COTO_C334S"))
    )
    (comp (ref "SSR_8HJ")
      (value "SSR_COTO_C334S")
      (footprint "eagle-import:SOP8")
      (libsource (lib "eagle-import") (part "SSR_COTO_C334S"))
    )
    (comp (ref "ARDUINO_A")
      (value "PINHD-1X15")
      (footprint "eagle-import:1X15")
      (libsource (lib "eagle-import") (part "PINHD-1X15"))
    )
    (comp (ref "ARDUINO_D")
      (value "PINHD-1X15")
      (footprint "eagle-import:1X15")
      (libsource (lib "eagle-import") (part "PINHD-1X15"))
    )
    (comp (ref "AUDIO_IN")
      (value "F25HP")
      (footprint "eagle-import:F25HP")
      (libsource (lib "eagle-import") (part "F25HP"))
    )
    (comp (ref "C_SUP1")
      (value "100u")
      (footprint "eagle-import:EIA3216")
      (libsource (lib "eagle-import") (part "CAP_POL12061"))
    )
    (comp (ref "C_SUP2")
      (value "10u")
      (footprint "eagle-import:C0805K")
      (libsource (lib "eagle-import") (part "C-EUC0805K"))
    )
    (comp (ref "GND_LIFT")
      (value "SWITCH_DPDT")
      (footprint "eagle-import:SWITCH_JS202011")
      (libsource (lib "eagle-import") (part "SWITCH_DPDT"))
    )
    (comp (ref "HEADER_EXT")
      (value "PINHD-1X12")
      (footprint "eagle-import:1X12")
      (libsource (lib "eagle-import") (part "PINHD-1X12"))
    )
    (comp (ref "I2C_SWITCH")
      (value "I2C-SWITCH_8-1TSSOP24")
      (footprint "eagle-import:TSSOP24")
      (libsource (lib "eagle-import") (part "I2C-SWITCH_8-1TSSOP24"))
    )
    (comp (ref "LED1")
      (value "red")
      (footprint "eagle-import:LED-1206")
      (libsource (lib "eagle-import") (part "LED1206"))
    )
    (comp (ref "LED2")
      (value "orange")
      (footprint "eagle-import:LED-1206")
      (libsource (lib "eagle-import") (part "LED1206"))
    )
    (comp (ref "LED3")
      (value "yellow")
      (footprint "eagle-import:LED-1206")
      (libsource (lib "eagle-import") (part "LED1206"))
    )
    (comp (ref "LED_SUP")
      (value "green")
      (footprint "eagle-import:LED-1206")
      (libsource (lib "eagle-import") (part "LED1206"))
    )
    (comp (ref "PWR:")
      (value "LUMBERG-1613-14\"")
      (footprint "eagle-import:LUMBERG-1613_14")
      (libsource (lib "eagle-import") (part "LUMBERG-1613-14{dblquote}"))
    )
    (comp (ref "RLED1")
      (value "1k")
      (footprint "eagle-import:R0402")
      (libsource (lib "eagle-import") (part "R-EU_R0402"))
    )
    (comp (ref "RLED2")
      (value "1k")
      (footprint "eagle-import:R0402")
      (libsource (lib "eagle-import") (part "R-EU_R0402"))
    )
    (comp (ref "RLED3")
      (value "1k")
      (footprint "eagle-import:R0402")
      (libsource (lib "eagle-import") (part "R-EU_R0402"))
    )
    (comp (ref "RLED_SUP")
      (value "10k")
      (footprint "eagle-import:R0402")
      (libsource (lib "eagle-import") (part "R-EU_R0402"))
    )
    (comp (ref "R_CLR")
      (value "4.75k")
      (footprint "eagle-import:R0402")
      (libsource (lib "eagle-import") (part "R-EU_R0402"))
    )
    (comp (ref "R_LIFT1")
      (value "100k")
      (footprint "eagle-import:R0402")
      (libsource (lib "eagle-import") (part "R-EU_R0402"))
    )
    (comp (ref "R_LIFT2")
      (value "100k")
      (footprint "eagle-import:R0402")
      (libsource (lib "eagle-import") (part "R-EU_R0402"))
    )
    (comp (ref "R_LOAD")
      (value "4.75k")
      (footprint "eagle-import:R0402")
      (libsource (lib "eagle-import") (part "R-EU_R0402"))
    )
    (comp (ref "R_OE")
      (value "4.75k")
      (footprint "eagle-import:R0402")
      (libsource (lib "eagle-import") (part "R-EU_R0402"))
    )
    (comp (ref "R_RST")
      (value "4.75k")
      (footprint "eagle-import:R0402")
      (libsource (lib "eagle-import") (part "R-EU_R0402"))
    )
    (comp (ref "R_SCL")
      (value "4.75k")
      (footprint "eagle-import:R0402")
      (libsource (lib "eagle-import") (part "R-EU_R0402"))
    )
    (comp (ref "R_SCL1")
      (value "4.75k")
      (footprint "eagle-import:R0402")
      (libsource (lib "eagle-import") (part "R-EU_R0402"))
    )
    (comp (ref "R_SCL2")
      (value "4.75k")
      (footprint "eagle-import:R0402")
      (libsource (lib "eagle-import") (part "R-EU_R0402"))
    )
    (comp (ref "R_SCL3")
      (value "4.75k")
      (footprint "eagle-import:R0402")
      (libsource (lib "eagle-import") (part "R-EU_R0402"))
    )
    (comp (ref "R_SCL4")
      (value "4.75k")
      (footprint "eagle-import:R0402")
      (libsource (lib "eagle-import") (part "R-EU_R0402"))
    )
    (comp (ref "R_SCL5")
      (value "4.75k")
      (footprint "eagle-import:R0402")
      (libsource (lib "eagle-import") (part "R-EU_R0402"))
    )
    (comp (ref "R_SCL6")
      (value "4.75k")
      (footprint "eagle-import:R0402")
      (libsource (lib "eagle-import") (part "R-EU_R0402"))
    )
    (comp (ref "R_SCL7")
      (value "4.75k")
      (footprint "eagle-import:R0402")
      (libsource (lib "eagle-import") (part "R-EU_R0402"))
    )
    (comp (ref "R_SCL8")
      (value "4.75k")
      (footprint "eagle-import:R0402")
      (libsource (lib "eagle-import") (part "R-EU_R0402"))
    )
    (comp (ref "R_SDA")
      (value "4.75k")
      (footprint "eagle-import:R0402")
      (libsource (lib "eagle-import") (part "R-EU_R0402"))
    )
    (comp (ref "R_SDA1")
      (value "4.75k")
      (footprint "eagle-import:R0402")
      (libsource (lib "eagle-import") (part "R-EU_R0402"))
    )
    (comp (ref "R_SDA2")
      (value "4.75k")
      (footprint "eagle-import:R0402")
      (libsource (lib "eagle-import") (part "R-EU_R0402"))
    )
    (comp (ref "R_SDA3")
      (value "4.75k")
      (footprint "eagle-import:R0402")
      (libsource (lib "eagle-import") (part "R-EU_R0402"))
    )
    (comp (ref "R_SDA4")
      (value "4.75k")
      (footprint "eagle-import:R0402")
      (libsource (lib "eagle-import") (part "R-EU_R0402"))
    )
    (comp (ref "R_SDA5")
      (value "4.75k")
      (footprint "eagle-import:R0402")
      (libsource (lib "eagle-import") (part "R-EU_R0402"))
    )
    (comp (ref "R_SDA6")
      (value "4.75k")
      (footprint "eagle-import:R0402")
      (libsource (lib "eagle-import") (part "R-EU_R0402"))
    )
    (comp (ref "R_SDA7")
      (value "4.75k")
      (footprint "eagle-import:R0402")
      (libsource (lib "eagle-import") (part "R-EU_R0402"))
    )
    (comp (ref "R_SDA8")
      (value "4.75k")
      (footprint "eagle-import:R0402")
      (libsource (lib "eagle-import") (part "R-EU_R0402"))
    )
  )
  (nets
    (net (code "1") (name "+5V") (class "Default")
      (node (ref "ARDUINO_A") (pin "15") (pinfunction "15_15") (pintype "passive"))
      (node (ref "CVDD1") (pin "1") (pinfunction "1_1") (pintype "passive"))
      (node (ref "CVDD2") (pin "1") (pinfunction "1_1") (pintype "passive"))
      (node (ref "CVDD3") (pin "1") (pinfunction "1_1") (pintype "passive"))
      (node (ref "CVDD4") (pin "1") (pinfunction "1_1") (pintype "passive"))
      (node (ref "CVDD5") (pin "1") (pinfunction "1_1") (pintype "passive"))
      (node (ref "CVDD6") (pin "1") (pinfunction "1_1") (pintype "passive"))
      (node (ref "CVDD7") (pin "1") (pinfunction "1_1") (pintype "passive"))
      (node (ref "CVDD8") (pin "1") (pinfunction "1_1") (pintype "passive"))
      (node (ref "C_SUP1") (pin "A") (pinfunction "+_A") (pintype "passive"))
      (node (ref "C_SUP2") (pin "1") (pinfunction "1_1") (pintype "passive"))
      (node (ref "DRV1") (pin "2") (pinfunction "VDD_2") (pintype "bidirectional"))
      (node (ref "DRV2") (pin "2") (pinfunction "VDD_2") (pintype "bidirectional"))
      (node (ref "DRV3") (pin "2") (pinfunction "VDD_2") (pintype "bidirectional"))
      (node (ref "DRV4") (pin "2") (pinfunction "VDD_2") (pintype "bidirectional"))
      (node (ref "DRV5") (pin "2") (pinfunction "VDD_2") (pintype "bidirectional"))
      (node (ref "DRV6") (pin "2") (pinfunction "VDD_2") (pintype "bidirectional"))
      (node (ref "DRV7") (pin "2") (pinfunction "VDD_2") (pintype "bidirectional"))
      (node (ref "DRV8") (pin "2") (pinfunction "VDD_2") (pintype "bidirectional"))
      (node (ref "HEADER_EXT") (pin "2") (pinfunction "2_2") (pintype "passive"))
      (node (ref "I2C_SWITCH") (pin "24") (pinfunction "VDD_24") (pintype "bidirectional"))
      (node (ref "L1") (pin "2") (pinfunction "2_2") (pintype "passive"))
      (node (ref "L2") (pin "2") (pinfunction "2_2") (pintype "passive"))
      (node (ref "L3") (pin "2") (pinfunction "2_2") (pintype "passive"))
      (node (ref "L4") (pin "2") (pinfunction "2_2") (pintype "passive"))
      (node (ref "L5") (pin "2") (pinfunction "2_2") (pintype "passive"))
      (node (ref "L6") (pin "2") (pinfunction "2_2") (pintype "passive"))
      (node (ref "L7") (pin "2") (pinfunction "2_2") (pintype "passive"))
      (node (ref "L8") (pin "2") (pinfunction "2_2") (pintype "passive"))
      (node (ref "LED1") (pin "A") (pinfunction "A_A") (pintype "passive"))
      (node (ref "LED2") (pin "A") (pinfunction "A_A") (pintype "passive"))
      (node (ref "LED3") (pin "A") (pinfunction "A_A") (pintype "passive"))
      (node (ref "PWR:") (pin "3") (pinfunction "PWR_1_3") (pintype "power_in"))
      (node (ref "PWR:") (pin "4") (pinfunction "PWR_2_4") (pintype "power_in"))
      (node (ref "RLED_SUP") (pin "2") (pinfunction "2_2") (pintype "passive"))
      (node (ref "R_1A") (pin "2") (pinfunction "2_2") (pintype "passive"))
      (node (ref "R_1B") (pin "2") (pinfunction "2_2") (pintype "passive"))
      (node (ref "R_1C") (pin "2") (pinfunction "2_2") (pintype "passive"))
      (node (ref "R_1D") (pin "2") (pinfunction "2_2") (pintype "passive"))
      (node (ref "R_1E") (pin "2") (pinfunction "2_2") (pintype "passive"))
      (node (ref "R_1F") (pin "2") (pinfunction "2_2") (pintype "passive"))
      (node (ref "R_1G") (pin "2") (pinfunction "2_2") (pintype "passive"))
      (node (ref "R_1H") (pin "2") (pinfunction "2_2") (pintype "passive"))
      (node (ref "R_1J") (pin "2") (pinfunction "2_2") (pintype "passive"))
      (node (ref "R_2A") (pin "2") (pinfunction "2_2") (pintype "passive"))
      (node (ref "R_2B") (pin "2") (pinfunction "2_2") (pintype "passive"))
      (node (ref "R_2C") (pin "2") (pinfunction "2_2") (pintype "passive"))
      (node (ref "R_2D") (pin "2") (pinfunction "2_2") (pintype "passive"))
      (node (ref "R_2E") (pin "2") (pinfunction "2_2") (pintype "passive"))
      (node (ref "R_2F") (pin "2") (pinfunction "2_2") (pintype "passive"))
      (node (ref "R_2G") (pin "2") (pinfunction "2_2") (pintype "passive"))
      (node (ref "R_2H") (pin "2") (pinfunction "2_2") (pintype "passive"))
      (node (ref "R_2J") (pin "2") (pinfunction "2_2") (pintype "passive"))
      (node (ref "R_3A") (pin "2") (pinfunction "2_2") (pintype "passive"))
      (node (ref "R_3B") (pin "2") (pinfunction "2_2") (pintype "passive"))
      (node (ref "R_3C") (pin "2") (pinfunction "2_2") (pintype "passive"))
      (node (ref "R_3D") (pin "2") (pinfunction "2_2") (pintype "passive"))
      (node (ref "R_3E") (pin "2") (pinfunction "2_2") (pintype "passive"))
      (node (ref "R_3F") (pin "2") (pinfunction "2_2") (pintype "passive"))
      (node (ref "R_3G") (pin "2") (pinfunction "2_2") (pintype "passive"))
      (node (ref "R_3H") (pin "2") (pinfunction "2_2") (pintype "passive"))
      (node (ref "R_3J") (pin "2") (pinfunction "2_2") (pintype "passive"))
      (node (ref "R_4A") (pin "2") (pinfunction "2_2") (pintype "passive"))
      (node (ref "R_4B") (pin "2") (pinfunction "2_2") (pintype "passive"))
      (node (ref "R_4C") (pin "2") (pinfunction "2_2") (pintype "passive"))
      (node (ref "R_4D") (pin "2") (pinfunction "2_2") (pintype "passive"))
      (node (ref "R_4E") (pin "2") (pinfunction "2_2") (pintype "passive"))
      (node (ref "R_4F") (pin "2") (pinfunction "2_2") (pintype "passive"))
      (node (ref "R_4G") (pin "2") (pinfunction "2_2") (pintype "passive"))
      (node (ref "R_4H") (pin "2") (pinfunction "2_2") (pintype "passive"))
      (node (ref "R_4J") (pin "2") (pinfunction "2_2") (pintype "passive"))
      (node (ref "R_5A") (pin "2") (pinfunction "2_2") (pintype "passive"))
      (node (ref "R_5B") (pin "2") (pinfunction "2_2") (pintype "passive"))
      (node (ref "R_5C") (pin "2") (pinfunction "2_2") (pintype "passive"))
      (node (ref "R_5D") (pin "2") (pinfunction "2_2") (pintype "passive"))
      (node (ref "R_5E") (pin "2") (pinfunction "2_2") (pintype "passive"))
      (node (ref "R_5F") (pin "2") (pinfunction "2_2") (pintype "passive"))
      (node (ref "R_5G") (pin "2") (pinfunction "2_2") (pintype "passive"))
      (node (ref "R_5H") (pin "2") (pinfunction "2_2") (pintype "passive"))
      (node (ref "R_5J") (pin "2") (pinfunction "2_2") (pintype "passive"))
      (node (ref "R_6A") (pin "2") (pinfunction "2_2") (pintype "passive"))
      (node (ref "R_6B") (pin "2") (pinfunction "2_2") (pintype "passive"))
      (node (ref "R_6C") (pin "2") (pinfunction "2_2") (pintype "passive"))
      (node (ref "R_6D") (pin "2") (pinfunction "2_2") (pintype "passive"))
      (node (ref "R_6E") (pin "2") (pinfunction "2_2") (pintype "passive"))
      (node (ref "R_6F") (pin "2") (pinfunction "2_2") (pintype "passive"))
      (node (ref "R_6G") (pin "2") (pinfunction "2_2") (pintype "passive"))
      (node (ref "R_6H") (pin "2") (pinfunction "2_2") (pintype "passive"))
      (node (ref "R_6J") (pin "2") (pinfunction "2_2") (pintype "passive"))
      (node (ref "R_7A") (pin "2") (pinfunction "2_2") (pintype "passive"))
      (node (ref "R_7B") (pin "2") (pinfunction "2_2") (pintype "passive"))
      (node (ref "R_7C") (pin "2") (pinfunction "2_2") (pintype "passive"))
      (node (ref "R_7D") (pin "2") (pinfunction "2_2") (pintype "passive"))
      (node (ref "R_7E") (pin "2") (pinfunction "2_2") (pintype "passive"))
      (node (ref "R_7F") (pin "2") (pinfunction "2_2") (pintype "passive"))
      (node (ref "R_7G") (pin "2") (pinfunction "2_2") (pintype "passive"))
      (node (ref "R_7H") (pin "2") (pinfunction "2_2") (pintype "passive"))
      (node (ref "R_7J") (pin "2") (pinfunction "2_2") (pintype "passive"))
      (node (ref "R_8A") (pin "2") (pinfunction "2_2") (pintype "passive"))
      (node (ref "R_8B") (pin "2") (pinfunction "2_2") (pintype "passive"))
      (node (ref "R_8C") (pin "2") (pinfunction "2_2") (pintype "passive"))
      (node (ref "R_8D") (pin "2") (pinfunction "2_2") (pintype "passive"))
      (node (ref "R_8E") (pin "2") (pinfunction "2_2") (pintype "passive"))
      (node (ref "R_8F") (pin "2") (pinfunction "2_2") (pintype "passive"))
      (node (ref "R_8G") (pin "2") (pinfunction "2_2") (pintype "passive"))
      (node (ref "R_8H") (pin "2") (pinfunction "2_2") (pintype "passive"))
      (node (ref "R_8J") (pin "2") (pinfunction "2_2") (pintype "passive"))
      (node (ref "R_CLR") (pin "2") (pinfunction "2_2") (pintype "passive"))
      (node (ref "R_LIFT2") (pin "2") (pinfunction "2_2") (pintype "passive"))
      (node (ref "R_OE") (pin "2") (pinfunction "2_2") (pintype "passive"))
      (node (ref "R_RST") (pin "2") (pinfunction "2_2") (pintype "passive"))
      (node (ref "R_SCL") (pin "2") (pinfunction "2_2") (pintype "passive"))
      (node (ref "R_SCL1") (pin "2") (pinfunction "2_2") (pintype "passive"))
      (node (ref "R_SCL2") (pin "2") (pinfunction "2_2") (pintype "passive"))
      (node (ref "R_SCL3") (pin "2") (pinfunction "2_2") (pintype "passive"))
      (node (ref "R_SCL4") (pin "2") (pinfunction "2_2") (pintype "passive"))
      (node (ref "R_SCL5") (pin "2") (pinfunction "2_2") (pintype "passive"))
      (node (ref "R_SCL6") (pin "2") (pinfunction "2_2") (pintype "passive"))
      (node (ref "R_SCL7") (pin "2") (pinfunction "2_2") (pintype "passive"))
      (node (ref "R_SCL8") (pin "2") (pinfunction "2_2") (pintype "passive"))
      (node (ref "R_SDA") (pin "2") (pinfunction "2_2") (pintype "passive"))
      (node (ref "R_SDA1") (pin "2") (pinfunction "2_2") (pintype "passive"))
      (node (ref "R_SDA2") (pin "2") (pinfunction "2_2") (pintype "passive"))
      (node (ref "R_SDA3") (pin "2") (pinfunction "2_2") (pintype "passive"))
      (node (ref "R_SDA4") (pin "2") (pinfunction "2_2") (pintype "passive"))
      (node (ref "R_SDA5") (pin "2") (pinfunction "2_2") (pintype "passive"))
      (node (ref "R_SDA6") (pin "2") (pinfunction "2_2") (pintype "passive"))
      (node (ref "R_SDA7") (pin "2") (pinfunction "2_2") (pintype "passive"))
      (node (ref "R_SDA8") (pin "2") (pinfunction "2_2") (pintype "passive"))
      (node (ref "SHIFTER0") (pin "16") (pinfunction "VCC_16") (pintype "power_in"))
      (node (ref "SHIFTER1") (pin "16") (pinfunction "VCC_16") (pintype "power_in"))
      (node (ref "SHIFTER2") (pin "16") (pinfunction "VCC_16") (pintype "power_in"))
      (node (ref "SHIFTER3") (pin "16") (pinfunction "VCC_16") (pintype "power_in"))
      (node (ref "SHIFTER4") (pin "16") (pinfunction "VCC_16") (pintype "power_in"))
      (node (ref "SHIFTER5") (pin "16") (pinfunction "VCC_16") (pintype "power_in"))
      (node (ref "SHIFTER6") (pin "16") (pinfunction "VCC_16") (pintype "power_in"))
      (node (ref "SHIFTER7") (pin "16") (pinfunction "VCC_16") (pintype "power_in"))
      (node (ref "SHIFTER8") (pin "16") (pinfunction "VCC_16") (pintype "power_in"))
    )
    (net (code "2") (name "0V") (class "Default")
      (node (ref "ARDUINO_A") (pin "14") (pinfunction "14_14") (pintype "passive"))
      (node (ref "ARDUINO_D") (pin "12") (pinfunction "12_12") (pintype "passive"))
      (node (ref "AUDIO_IN") (pin "G1") (pinfunction "G1_G1") (pintype "passive"))
      (node (ref "AUDIO_IN") (pin "G2") (pinfunction "G2_G2") (pintype "passive"))
      (node (ref "CPUMP1") (pin "2") (pinfunction "2_2") (pintype "passive"))
      (node (ref "CPUMP2") (pin "2") (pinfunction "2_2") (pintype "passive"))
      (node (ref "CPUMP3") (pin "2") (pinfunction "2_2") (pintype "passive"))
      (node (ref "CPUMP4") (pin "2") (pinfunction "2_2") (pintype "passive"))
      (node (ref "CPUMP5") (pin "2") (pinfunction "2_2") (pintype "passive"))
      (node (ref "CPUMP6") (pin "2") (pinfunction "2_2") (pintype "passive"))
      (node (ref "CPUMP7") (pin "2") (pinfunction "2_2") (pintype "passive"))
      (node (ref "CPUMP8") (pin "2") (pinfunction "2_2") (pintype "passive"))
      (node (ref "CVBST1") (pin "2") (pinfunction "2_2") (pintype "passive"))
      (node (ref "CVBST2") (pin "2") (pinfunction "2_2") (pintype "passive"))
      (node (ref "CVBST3") (pin "2") (pinfunction "2_2") (pintype "passive"))
      (node (ref "CVBST4") (pin "2") (pinfunction "2_2") (pintype "passive"))
      (node (ref "CVBST5") (pin "2") (pinfunction "2_2") (pintype "passive"))
      (node (ref "CVBST6") (pin "2") (pinfunction "2_2") (pintype "passive"))
      (node (ref "CVBST7") (pin "2") (pinfunction "2_2") (pintype "passive"))
      (node (ref "CVBST8") (pin "2") (pinfunction "2_2") (pintype "passive"))
      (node (ref "CVDD1") (pin "2") (pinfunction "2_2") (pintype "passive"))
      (node (ref "CVDD2") (pin "2") (pinfunction "2_2") (pintype "passive"))
      (node (ref "CVDD3") (pin "2") (pinfunction "2_2") (pintype "passive"))
      (node (ref "CVDD4") (pin "2") (pinfunction "2_2") (pintype "passive"))
      (node (ref "CVDD5") (pin "2") (pinfunction "2_2") (pintype "passive"))
      (node (ref "CVDD6") (pin "2") (pinfunction "2_2") (pintype "passive"))
      (node (ref "CVDD7") (pin "2") (pinfunction "2_2") (pintype "passive"))
      (node (ref "CVDD8") (pin "2") (pinfunction "2_2") (pintype "passive"))
      (node (ref "CVREG1") (pin "2") (pinfunction "2_2") (pintype "passive"))
      (node (ref "CVREG2") (pin "2") (pinfunction "2_2") (pintype "passive"))
      (node (ref "CVREG3") (pin "2") (pinfunction "2_2") (pintype "passive"))
      (node (ref "CVREG4") (pin "2") (pinfunction "2_2") (pintype "passive"))
      (node (ref "CVREG5") (pin "2") (pinfunction "2_2") (pintype "passive"))
      (node (ref "CVREG6") (pin "2") (pinfunction "2_2") (pintype "passive"))
      (node (ref "CVREG7") (pin "2") (pinfunction "2_2") (pintype "passive"))
      (node (ref "CVREG8") (pin "2") (pinfunction "2_2") (pintype "passive"))
      (node (ref "C_SUP1") (pin "C") (pinfunction "-_C") (pintype "passive"))
      (node (ref "C_SUP2") (pin "2") (pinfunction "2_2") (pintype "passive"))
      (node (ref "DRV1") (pin "4") (pinfunction "GND_4") (pintype "bidirectional"))
      (node (ref "DRV1") (pin "5") (pinfunction "GND_5") (pintype "bidirectional"))
      (node (ref "DRV1") (pin "6") (pinfunction "GND_6") (pintype "bidirectional"))
      (node (ref "DRV1") (pin "PAD1") (pinfunction "PAD_PAD1") (pintype "bidirectional"))
      (node (ref "DRV1") (pin "PAD2") (pinfunction "PAD_PAD2") (pintype "bidirectional"))
      (node (ref "DRV1") (pin "PAD3") (pinfunction "PAD_PAD3") (pintype "bidirectional"))
      (node (ref "DRV1") (pin "PAD4") (pinfunction "PAD_PAD4") (pintype "bidirectional"))
      (node (ref "DRV1") (pin "PAD5") (pinfunction "PAD_PAD5") (pintype "bidirectional"))
      (node (ref "DRV1") (pin "PAD6") (pinfunction "PAD_PAD6") (pintype "bidirectional"))
      (node (ref "DRV1") (pin "PAD7") (pinfunction "PAD_PAD7") (pintype "bidirectional"))
      (node (ref "DRV1") (pin "PAD8") (pinfunction "PAD_PAD8") (pintype "bidirectional"))
      (node (ref "DRV1") (pin "PAD9") (pinfunction "PAD_PAD9") (pintype "bidirectional"))
      (node (ref "DRV2") (pin "4") (pinfunction "GND_4") (pintype "bidirectional"))
      (node (ref "DRV2") (pin "5") (pinfunction "GND_5") (pintype "bidirectional"))
      (node (ref "DRV2") (pin "6") (pinfunction "GND_6") (pintype "bidirectional"))
      (node (ref "DRV2") (pin "PAD1") (pinfunction "PAD_PAD1") (pintype "bidirectional"))
      (node (ref "DRV2") (pin "PAD2") (pinfunction "PAD_PAD2") (pintype "bidirectional"))
      (node (ref "DRV2") (pin "PAD3") (pinfunction "PAD_PAD3") (pintype "bidirectional"))
      (node (ref "DRV2") (pin "PAD4") (pinfunction "PAD_PAD4") (pintype "bidirectional"))
      (node (ref "DRV2") (pin "PAD5") (pinfunction "PAD_PAD5") (pintype "bidirectional"))
      (node (ref "DRV2") (pin "PAD6") (pinfunction "PAD_PAD6") (pintype "bidirectional"))
      (node (ref "DRV2") (pin "PAD7") (pinfunction "PAD_PAD7") (pintype "bidirectional"))
      (node (ref "DRV2") (pin "PAD8") (pinfunction "PAD_PAD8") (pintype "bidirectional"))
      (node (ref "DRV2") (pin "PAD9") (pinfunction "PAD_PAD9") (pintype "bidirectional"))
      (node (ref "DRV3") (pin "4") (pinfunction "GND_4") (pintype "bidirectional"))
      (node (ref "DRV3") (pin "5") (pinfunction "GND_5") (pintype "bidirectional"))
      (node (ref "DRV3") (pin "6") (pinfunction "GND_6") (pintype "bidirectional"))
      (node (ref "DRV3") (pin "PAD1") (pinfunction "PAD_PAD1") (pintype "bidirectional"))
      (node (ref "DRV3") (pin "PAD2") (pinfunction "PAD_PAD2") (pintype "bidirectional"))
      (node (ref "DRV3") (pin "PAD3") (pinfunction "PAD_PAD3") (pintype "bidirectional"))
      (node (ref "DRV3") (pin "PAD4") (pinfunction "PAD_PAD4") (pintype "bidirectional"))
      (node (ref "DRV3") (pin "PAD5") (pinfunction "PAD_PAD5") (pintype "bidirectional"))
      (node (ref "DRV3") (pin "PAD6") (pinfunction "PAD_PAD6") (pintype "bidirectional"))
      (node (ref "DRV3") (pin "PAD7") (pinfunction "PAD_PAD7") (pintype "bidirectional"))
      (node (ref "DRV3") (pin "PAD8") (pinfunction "PAD_PAD8") (pintype "bidirectional"))
      (node (ref "DRV3") (pin "PAD9") (pinfunction "PAD_PAD9") (pintype "bidirectional"))
      (node (ref "DRV4") (pin "4") (pinfunction "GND_4") (pintype "bidirectional"))
      (node (ref "DRV4") (pin "5") (pinfunction "GND_5") (pintype "bidirectional"))
      (node (ref "DRV4") (pin "6") (pinfunction "GND_6") (pintype "bidirectional"))
      (node (ref "DRV4") (pin "PAD1") (pinfunction "PAD_PAD1") (pintype "bidirectional"))
      (node (ref "DRV4") (pin "PAD2") (pinfunction "PAD_PAD2") (pintype "bidirectional"))
      (node (ref "DRV4") (pin "PAD3") (pinfunction "PAD_PAD3") (pintype "bidirectional"))
      (node (ref "DRV4") (pin "PAD4") (pinfunction "PAD_PAD4") (pintype "bidirectional"))
      (node (ref "DRV4") (pin "PAD5") (pinfunction "PAD_PAD5") (pintype "bidirectional"))
      (node (ref "DRV4") (pin "PAD6") (pinfunction "PAD_PAD6") (pintype "bidirectional"))
      (node (ref "DRV4") (pin "PAD7") (pinfunction "PAD_PAD7") (pintype "bidirectional"))
      (node (ref "DRV4") (pin "PAD8") (pinfunction "PAD_PAD8") (pintype "bidirectional"))
      (node (ref "DRV4") (pin "PAD9") (pinfunction "PAD_PAD9") (pintype "bidirectional"))
      (node (ref "DRV5") (pin "4") (pinfunction "GND_4") (pintype "bidirectional"))
      (node (ref "DRV5") (pin "5") (pinfunction "GND_5") (pintype "bidirectional"))
      (node (ref "DRV5") (pin "6") (pinfunction "GND_6") (pintype "bidirectional"))
      (node (ref "DRV5") (pin "PAD1") (pinfunction "PAD_PAD1") (pintype "bidirectional"))
      (node (ref "DRV5") (pin "PAD2") (pinfunction "PAD_PAD2") (pintype "bidirectional"))
      (node (ref "DRV5") (pin "PAD3") (pinfunction "PAD_PAD3") (pintype "bidirectional"))
      (node (ref "DRV5") (pin "PAD4") (pinfunction "PAD_PAD4") (pintype "bidirectional"))
      (node (ref "DRV5") (pin "PAD5") (pinfunction "PAD_PAD5") (pintype "bidirectional"))
      (node (ref "DRV5") (pin "PAD6") (pinfunction "PAD_PAD6") (pintype "bidirectional"))
      (node (ref "DRV5") (pin "PAD7") (pinfunction "PAD_PAD7") (pintype "bidirectional"))
      (node (ref "DRV5") (pin "PAD8") (pinfunction "PAD_PAD8") (pintype "bidirectional"))
      (node (ref "DRV5") (pin "PAD9") (pinfunction "PAD_PAD9") (pintype "bidirectional"))
      (node (ref "DRV6") (pin "4") (pinfunction "GND_4") (pintype "bidirectional"))
      (node (ref "DRV6") (pin "5") (pinfunction "GND_5") (pintype "bidirectional"))
      (node (ref "DRV6") (pin "6") (pinfunction "GND_6") (pintype "bidirectional"))
      (node (ref "DRV6") (pin "PAD1") (pinfunction "PAD_PAD1") (pintype "bidirectional"))
      (node (ref "DRV6") (pin "PAD2") (pinfunction "PAD_PAD2") (pintype "bidirectional"))
      (node (ref "DRV6") (pin "PAD3") (pinfunction "PAD_PAD3") (pintype "bidirectional"))
      (node (ref "DRV6") (pin "PAD4") (pinfunction "PAD_PAD4") (pintype "bidirectional"))
      (node (ref "DRV6") (pin "PAD5") (pinfunction "PAD_PAD5") (pintype "bidirectional"))
      (node (ref "DRV6") (pin "PAD6") (pinfunction "PAD_PAD6") (pintype "bidirectional"))
      (node (ref "DRV6") (pin "PAD7") (pinfunction "PAD_PAD7") (pintype "bidirectional"))
      (node (ref "DRV6") (pin "PAD8") (pinfunction "PAD_PAD8") (pintype "bidirectional"))
      (node (ref "DRV6") (pin "PAD9") (pinfunction "PAD_PAD9") (pintype "bidirectional"))
      (node (ref "DRV7") (pin "4") (pinfunction "GND_4") (pintype "bidirectional"))
      (node (ref "DRV7") (pin "5") (pinfunction "GND_5") (pintype "bidirectional"))
      (node (ref "DRV7") (pin "6") (pinfunction "GND_6") (pintype "bidirectional"))
      (node (ref "DRV7") (pin "PAD1") (pinfunction "PAD_PAD1") (pintype "bidirectional"))
      (node (ref "DRV7") (pin "PAD2") (pinfunction "PAD_PAD2") (pintype "bidirectional"))
      (node (ref "DRV7") (pin "PAD3") (pinfunction "PAD_PAD3") (pintype "bidirectional"))
      (node (ref "DRV7") (pin "PAD4") (pinfunction "PAD_PAD4") (pintype "bidirectional"))
      (node (ref "DRV7") (pin "PAD5") (pinfunction "PAD_PAD5") (pintype "bidirectional"))
      (node (ref "DRV7") (pin "PAD6") (pinfunction "PAD_PAD6") (pintype "bidirectional"))
      (node (ref "DRV7") (pin "PAD7") (pinfunction "PAD_PAD7") (pintype "bidirectional"))
      (node (ref "DRV7") (pin "PAD8") (pinfunction "PAD_PAD8") (pintype "bidirectional"))
      (node (ref "DRV7") (pin "PAD9") (pinfunction "PAD_PAD9") (pintype "bidirectional"))
      (node (ref "DRV8") (pin "4") (pinfunction "GND_4") (pintype "bidirectional"))
      (node (ref "DRV8") (pin "5") (pinfunction "GND_5") (pintype "bidirectional"))
      (node (ref "DRV8") (pin "6") (pinfunction "GND_6") (pintype "bidirectional"))
      (node (ref "DRV8") (pin "PAD1") (pinfunction "PAD_PAD1") (pintype "bidirectional"))
      (node (ref "DRV8") (pin "PAD2") (pinfunction "PAD_PAD2") (pintype "bidirectional"))
      (node (ref "DRV8") (pin "PAD3") (pinfunction "PAD_PAD3") (pintype "bidirectional"))
      (node (ref "DRV8") (pin "PAD4") (pinfunction "PAD_PAD4") (pintype "bidirectional"))
      (node (ref "DRV8") (pin "PAD5") (pinfunction "PAD_PAD5") (pintype "bidirectional"))
      (node (ref "DRV8") (pin "PAD6") (pinfunction "PAD_PAD6") (pintype "bidirectional"))
      (node (ref "DRV8") (pin "PAD7") (pinfunction "PAD_PAD7") (pintype "bidirectional"))
      (node (ref "DRV8") (pin "PAD8") (pinfunction "PAD_PAD8") (pintype "bidirectional"))
      (node (ref "DRV8") (pin "PAD9") (pinfunction "PAD_PAD9") (pintype "bidirectional"))
      (node (ref "HEADER_EXT") (pin "1") (pinfunction "1_1") (pintype "passive"))
      (node (ref "HEADER_EXT") (pin "12") (pinfunction "12_12") (pintype "passive"))
      (node (ref "I2C_SWITCH") (pin "12") (pinfunction "VSS_12") (pintype "bidirectional"))
      (node (ref "LED_SUP") (pin "C") (pinfunction "C_C") (pintype "passive"))
      (node (ref "PWR:") (pin "1") (pinfunction "GND_1") (pintype "power_in"))
      (node (ref "PWR:") (pin "2") (pinfunction "GND_INS_2") (pintype "power_in"))
      (node (ref "REXT1") (pin "1") (pinfunction "1_1") (pintype "passive"))
      (node (ref "REXT2") (pin "1") (pinfunction "1_1") (pintype "passive"))
      (node (ref "REXT3") (pin "1") (pinfunction "1_1") (pintype "passive"))
      (node (ref "REXT4") (pin "1") (pinfunction "1_1") (pintype "passive"))
      (node (ref "REXT5") (pin "1") (pinfunction "1_1") (pintype "passive"))
      (node (ref "REXT6") (pin "1") (pinfunction "1_1") (pintype "passive"))
      (node (ref "REXT7") (pin "1") (pinfunction "1_1") (pintype "passive"))
      (node (ref "REXT8") (pin "1") (pinfunction "1_1") (pintype "passive"))
      (node (ref "RVBST1-2") (pin "1") (pinfunction "1_1") (pintype "passive"))
      (node (ref "RVBST2-2") (pin "1") (pinfunction "1_1") (pintype "passive"))
      (node (ref "RVBST3-2") (pin "1") (pinfunction "1_1") (pintype "passive"))
      (node (ref "RVBST4-2") (pin "1") (pinfunction "1_1") (pintype "passive"))
      (node (ref "RVBST5-2") (pin "1") (pinfunction "1_1") (pintype "passive"))
      (node (ref "RVBST6-2") (pin "1") (pinfunction "1_1") (pintype "passive"))
      (node (ref "RVBST7-2") (pin "1") (pinfunction "1_1") (pintype "passive"))
      (node (ref "RVBST8-2") (pin "1") (pinfunction "1_1") (pintype "passive"))
      (node (ref "R_LIFT1") (pin "1") (pinfunction "1_1") (pintype "passive"))
      (node (ref "R_LOAD") (pin "1") (pinfunction "1_1") (pintype "passive"))
      (node (ref "SHIFTER0") (pin "8") (pinfunction "GND_8") (pintype "power_in"))
      (node (ref "SHIFTER0") (pin "PAD") (pinfunction "GND_PAD") (pintype "power_in"))
      (node (ref "SHIFTER1") (pin "8") (pinfunction "GND_8") (pintype "power_in"))
      (node (ref "SHIFTER1") (pin "PAD") (pinfunction "GND_PAD") (pintype "power_in"))
      (node (ref "SHIFTER2") (pin "8") (pinfunction "GND_8") (pintype "power_in"))
      (node (ref "SHIFTER2") (pin "PAD") (pinfunction "GND_PAD") (pintype "power_in"))
      (node (ref "SHIFTER3") (pin "8") (pinfunction "GND_8") (pintype "power_in"))
      (node (ref "SHIFTER3") (pin "PAD") (pinfunction "GND_PAD") (pintype "power_in"))
      (node (ref "SHIFTER4") (pin "8") (pinfunction "GND_8") (pintype "power_in"))
      (node (ref "SHIFTER4") (pin "PAD") (pinfunction "GND_PAD") (pintype "power_in"))
      (node (ref "SHIFTER5") (pin "8") (pinfunction "GND_8") (pintype "power_in"))
      (node (ref "SHIFTER5") (pin "PAD") (pinfunction "GND_PAD") (pintype "power_in"))
      (node (ref "SHIFTER6") (pin "8") (pinfunction "GND_8") (pintype "power_in"))
      (node (ref "SHIFTER6") (pin "PAD") (pinfunction "GND_PAD") (pintype "power_in"))
      (node (ref "SHIFTER7") (pin "8") (pinfunction "GND_8") (pintype "power_in"))
      (node (ref "SHIFTER7") (pin "PAD") (pinfunction "GND_PAD") (pintype "power_in"))
      (node (ref "SHIFTER8") (pin "8") (pinfunction "GND_8") (pintype "power_in"))
      (node (ref "SHIFTER8") (pin "PAD") (pinfunction "GND_PAD") (pintype "power_in"))
    )
    (net (code "3") (name "CH1_I+") (class "Default")
      (node (ref "AUDIO_IN") (pin "24") (pinfunction "24_24") (pintype "passive"))
      (node (ref "DRV1") (pin "17") (pinfunction "IN+_17") (pintype "bidirectional"))
    )
    (net (code "4") (name "CH1_I-") (class "Default")
      (node (ref "AUDIO_IN") (pin "12") (pinfunction "12_12") (pintype "passive"))
      (node (ref "DRV1") (pin "16") (pinfunction "IN-_16") (pintype "bidirectional"))
    )
    (net (code "5") (name "CH1_O+") (class "Default")
      (node (ref "DRV1") (pin "13") (pinfunction "OUT+_13") (pintype "bidirectional"))
      (node (ref "SSR_1AB") (pin "5") (pinfunction "O1_5") (pintype "bidirectional"))
      (node (ref "SSR_1AB") (pin "7") (pinfunction "O1_7") (pintype "bidirectional"))
      (node (ref "SSR_1CD") (pin "5") (pinfunction "O1_5") (pintype "bidirectional"))
      (node (ref "SSR_1CD") (pin "7") (pinfunction "O1_7") (pintype "bidirectional"))
      (node (ref "SSR_1EF") (pin "5") (pinfunction "O1_5") (pintype "bidirectional"))
      (node (ref "SSR_1EF") (pin "7") (pinfunction "O1_7") (pintype "bidirectional"))
      (node (ref "SSR_1GH") (pin "5") (pinfunction "O1_5") (pintype "bidirectional"))
      (node (ref "SSR_1GH") (pin "7") (pinfunction "O1_7") (pintype "bidirectional"))
      (node (ref "SSR_1J/2A") (pin "7") (pinfunction "O1_7") (pintype "bidirectional"))
    )
    (net (code "6") (name "CH1_O-") (class "Default")
      (node (ref "DRV1") (pin "14") (pinfunction "OUT-_14") (pintype "bidirectional"))
      (node (ref "P-CH1+2") (pin "12") (pinfunction "1_12") (pintype "passive"))
      (node (ref "P-CH1+2") (pin "18") (pinfunction "1_18") (pintype "passive"))
    )
    (net (code "7") (name "CH1_PA+") (class "Default")
      (node (ref "P-CH1+2") (pin "22") (pinfunction "1_22") (pintype "passive"))
      (node (ref "SSR_1AB") (pin "8") (pinfunction "O2_8") (pintype "bidirectional"))
    )
    (net (code "8") (name "CH1_PB+") (class "Default")
      (node (ref "P-CH1+2") (pin "21") (pinfunction "1_21") (pintype "passive"))
      (node (ref "SSR_1AB") (pin "6") (pinfunction "O2_6") (pintype "bidirectional"))
    )
    (net (code "9") (name "CH1_PC+") (class "Default")
      (node (ref "P-CH1+2") (pin "20") (pinfunction "1_20") (pintype "passive"))
      (node (ref "SSR_1CD") (pin "8") (pinfunction "O2_8") (pintype "bidirectional"))
    )
    (net (code "10") (name "CH1_PD+") (class "Default")
      (node (ref "P-CH1+2") (pin "19") (pinfunction "1_19") (pintype "passive"))
      (node (ref "SSR_1CD") (pin "6") (pinfunction "O2_6") (pintype "bidirectional"))
    )
    (net (code "11") (name "CH1_PE+") (class "Default")
      (node (ref "P-CH1+2") (pin "17") (pinfunction "1_17") (pintype "passive"))
      (node (ref "SSR_1EF") (pin "8") (pinfunction "O2_8") (pintype "bidirectional"))
    )
    (net (code "12") (name "CH1_PF+") (class "Default")
      (node (ref "P-CH1+2") (pin "16") (pinfunction "1_16") (pintype "passive"))
      (node (ref "SSR_1EF") (pin "6") (pinfunction "O2_6") (pintype "bidirectional"))
    )
    (net (code "13") (name "CH1_PG+") (class "Default")
      (node (ref "P-CH1+2") (pin "15") (pinfunction "1_15") (pintype "passive"))
      (node (ref "SSR_1GH") (pin "8") (pinfunction "O2_8") (pintype "bidirectional"))
    )
    (net (code "14") (name "CH1_PH+") (class "Default")
      (node (ref "P-CH1+2") (pin "14") (pinfunction "1_14") (pintype "passive"))
      (node (ref "SSR_1GH") (pin "6") (pinfunction "O2_6") (pintype "bidirectional"))
    )
    (net (code "15") (name "CH1_PJ+") (class "Default")
      (node (ref "P-CH1+2") (pin "13") (pinfunction "1_13") (pintype "passive"))
      (node (ref "SSR_1J/2A") (pin "8") (pinfunction "O2_8") (pintype "bidirectional"))
    )
    (net (code "16") (name "CH2_I+") (class "Default")
      (node (ref "AUDIO_IN") (pin "10") (pinfunction "10_10") (pintype "passive"))
      (node (ref "DRV2") (pin "17") (pinfunction "IN+_17") (pintype "bidirectional"))
    )
    (net (code "17") (name "CH2_I-") (class "Default")
      (node (ref "AUDIO_IN") (pin "23") (pinfunction "23_23") (pintype "passive"))
      (node (ref "DRV2") (pin "16") (pinfunction "IN-_16") (pintype "bidirectional"))
    )
    (net (code "18") (name "CH2_O+") (class "Default")
      (node (ref "DRV2") (pin "13") (pinfunction "OUT+_13") (pintype "bidirectional"))
      (node (ref "SSR_1J/2A") (pin "5") (pinfunction "O1_5") (pintype "bidirectional"))
      (node (ref "SSR_2BC") (pin "5") (pinfunction "O1_5") (pintype "bidirectional"))
      (node (ref "SSR_2BC") (pin "7") (pinfunction "O1_7") (pintype "bidirectional"))
      (node (ref "SSR_2DE") (pin "5") (pinfunction "O1_5") (pintype "bidirectional"))
      (node (ref "SSR_2DE") (pin "7") (pinfunction "O1_7") (pintype "bidirectional"))
      (node (ref "SSR_2FG") (pin "5") (pinfunction "O1_5") (pintype "bidirectional"))
      (node (ref "SSR_2FG") (pin "7") (pinfunction "O1_7") (pintype "bidirectional"))
      (node (ref "SSR_2HJ") (pin "5") (pinfunction "O1_5") (pintype "bidirectional"))
      (node (ref "SSR_2HJ") (pin "7") (pinfunction "O1_7") (pintype "bidirectional"))
    )
    (net (code "19") (name "CH2_O-") (class "Default")
      (node (ref "DRV2") (pin "14") (pinfunction "OUT-_14") (pintype "bidirectional"))
      (node (ref "P-CH1+2") (pin "1") (pinfunction "1_1") (pintype "passive"))
      (node (ref "P-CH1+2") (pin "7") (pinfunction "1_7") (pintype "passive"))
    )
    (net (code "20") (name "CH2_PA+") (class "Default")
      (node (ref "P-CH1+2") (pin "11") (pinfunction "1_11") (pintype "passive"))
      (node (ref "SSR_1J/2A") (pin "6") (pinfunction "O2_6") (pintype "bidirectional"))
    )
    (net (code "21") (name "CH2_PB+") (class "Default")
      (node (ref "P-CH1+2") (pin "10") (pinfunction "1_10") (pintype "passive"))
      (node (ref "SSR_2BC") (pin "8") (pinfunction "O2_8") (pintype "bidirectional"))
    )
    (net (code "22") (name "CH2_PC+") (class "Default")
      (node (ref "P-CH1+2") (pin "9") (pinfunction "1_9") (pintype "passive"))
      (node (ref "SSR_2BC") (pin "6") (pinfunction "O2_6") (pintype "bidirectional"))
    )
    (net (code "23") (name "CH2_PD+") (class "Default")
      (node (ref "P-CH1+2") (pin "8") (pinfunction "1_8") (pintype "passive"))
      (node (ref "SSR_2DE") (pin "8") (pinfunction "O2_8") (pintype "bidirectional"))
    )
    (net (code "24") (name "CH2_PE+") (class "Default")
      (node (ref "P-CH1+2") (pin "6") (pinfunction "1_6") (pintype "passive"))
      (node (ref "SSR_2DE") (pin "6") (pinfunction "O2_6") (pintype "bidirectional"))
    )
    (net (code "25") (name "CH2_PF+") (class "Default")
      (node (ref "P-CH1+2") (pin "5") (pinfunction "1_5") (pintype "passive"))
      (node (ref "SSR_2FG") (pin "8") (pinfunction "O2_8") (pintype "bidirectional"))
    )
    (net (code "26") (name "CH2_PG+") (class "Default")
      (node (ref "P-CH1+2") (pin "4") (pinfunction "1_4") (pintype "passive"))
      (node (ref "SSR_2FG") (pin "6") (pinfunction "O2_6") (pintype "bidirectional"))
    )
    (net (code "27") (name "CH2_PH+") (class "Default")
      (node (ref "P-CH1+2") (pin "3") (pinfunction "1_3") (pintype "passive"))
      (node (ref "SSR_2HJ") (pin "8") (pinfunction "O2_8") (pintype "bidirectional"))
    )
    (net (code "28") (name "CH2_PJ+") (class "Default")
      (node (ref "P-CH1+2") (pin "2") (pinfunction "1_2") (pintype "passive"))
      (node (ref "SSR_2HJ") (pin "6") (pinfunction "O2_6") (pintype "bidirectional"))
    )
    (net (code "29") (name "CH3_I+") (class "Default")
      (node (ref "AUDIO_IN") (pin "21") (pinfunction "21_21") (pintype "passive"))
      (node (ref "DRV3") (pin "17") (pinfunction "IN+_17") (pintype "bidirectional"))
    )
    (net (code "30") (name "CH3_I-") (class "Default")
      (node (ref "AUDIO_IN") (pin "9") (pinfunction "9_9") (pintype "passive"))
      (node (ref "DRV3") (pin "16") (pinfunction "IN-_16") (pintype "bidirectional"))
    )
    (net (code "31") (name "CH3_O+") (class "Default")
      (node (ref "DRV3") (pin "13") (pinfunction "OUT+_13") (pintype "bidirectional"))
      (node (ref "SSR_3AB") (pin "5") (pinfunction "O1_5") (pintype "bidirectional"))
      (node (ref "SSR_3AB") (pin "7") (pinfunction "O1_7") (pintype "bidirectional"))
      (node (ref "SSR_3CD") (pin "5") (pinfunction "O1_5") (pintype "bidirectional"))
      (node (ref "SSR_3CD") (pin "7") (pinfunction "O1_7") (pintype "bidirectional"))
      (node (ref "SSR_3EF") (pin "5") (pinfunction "O1_5") (pintype "bidirectional"))
      (node (ref "SSR_3EF") (pin "7") (pinfunction "O1_7") (pintype "bidirectional"))
      (node (ref "SSR_3GH") (pin "5") (pinfunction "O1_5") (pintype "bidirectional"))
      (node (ref "SSR_3GH") (pin "7") (pinfunction "O1_7") (pintype "bidirectional"))
      (node (ref "SSR_3J/4A") (pin "7") (pinfunction "O1_7") (pintype "bidirectional"))
    )
    (net (code "32") (name "CH3_O-") (class "Default")
      (node (ref "DRV3") (pin "14") (pinfunction "OUT-_14") (pintype "bidirectional"))
      (node (ref "P-CH3+4") (pin "12") (pinfunction "1_12") (pintype "passive"))
      (node (ref "P-CH3+4") (pin "18") (pinfunction "1_18") (pintype "passive"))
    )
    (net (code "33") (name "CH3_PA+") (class "Default")
      (node (ref "P-CH3+4") (pin "22") (pinfunction "1_22") (pintype "passive"))
      (node (ref "SSR_3AB") (pin "8") (pinfunction "O2_8") (pintype "bidirectional"))
    )
    (net (code "34") (name "CH3_PB+") (class "Default")
      (node (ref "P-CH3+4") (pin "21") (pinfunction "1_21") (pintype "passive"))
      (node (ref "SSR_3AB") (pin "6") (pinfunction "O2_6") (pintype "bidirectional"))
    )
    (net (code "35") (name "CH3_PC+") (class "Default")
      (node (ref "P-CH3+4") (pin "20") (pinfunction "1_20") (pintype "passive"))
      (node (ref "SSR_3CD") (pin "8") (pinfunction "O2_8") (pintype "bidirectional"))
    )
    (net (code "36") (name "CH3_PD+") (class "Default")
      (node (ref "P-CH3+4") (pin "19") (pinfunction "1_19") (pintype "passive"))
      (node (ref "SSR_3CD") (pin "6") (pinfunction "O2_6") (pintype "bidirectional"))
    )
    (net (code "37") (name "CH3_PE+") (class "Default")
      (node (ref "P-CH3+4") (pin "17") (pinfunction "1_17") (pintype "passive"))
      (node (ref "SSR_3EF") (pin "8") (pinfunction "O2_8") (pintype "bidirectional"))
    )
    (net (code "38") (name "CH3_PF+") (class "Default")
      (node (ref "P-CH3+4") (pin "16") (pinfunction "1_16") (pintype "passive"))
      (node (ref "SSR_3EF") (pin "6") (pinfunction "O2_6") (pintype "bidirectional"))
    )
    (net (code "39") (name "CH3_PG+") (class "Default")
      (node (ref "P-CH3+4") (pin "15") (pinfunction "1_15") (pintype "passive"))
      (node (ref "SSR_3GH") (pin "8") (pinfunction "O2_8") (pintype "bidirectional"))
    )
    (net (code "40") (name "CH3_PH+") (class "Default")
      (node (ref "P-CH3+4") (pin "14") (pinfunction "1_14") (pintype "passive"))
      (node (ref "SSR_3GH") (pin "6") (pinfunction "O2_6") (pintype "bidirectional"))
    )
    (net (code "41") (name "CH3_PJ+") (class "Default")
      (node (ref "P-CH3+4") (pin "13") (pinfunction "1_13") (pintype "passive"))
      (node (ref "SSR_3J/4A") (pin "8") (pinfunction "O2_8") (pintype "bidirectional"))
    )
    (net (code "42") (name "CH4_I+") (class "Default")
      (node (ref "AUDIO_IN") (pin "7") (pinfunction "7_7") (pintype "passive"))
      (node (ref "DRV4") (pin "17") (pinfunction "IN+_17") (pintype "bidirectional"))
    )
    (net (code "43") (name "CH4_I-") (class "Default")
      (node (ref "AUDIO_IN") (pin "20") (pinfunction "20_20") (pintype "passive"))
      (node (ref "DRV4") (pin "16") (pinfunction "IN-_16") (pintype "bidirectional"))
    )
    (net (code "44") (name "CH4_O+") (class "Default")
      (node (ref "DRV4") (pin "13") (pinfunction "OUT+_13") (pintype "bidirectional"))
      (node (ref "SSR_3J/4A") (pin "5") (pinfunction "O1_5") (pintype "bidirectional"))
      (node (ref "SSR_4BC") (pin "5") (pinfunction "O1_5") (pintype "bidirectional"))
      (node (ref "SSR_4BC") (pin "7") (pinfunction "O1_7") (pintype "bidirectional"))
      (node (ref "SSR_4DE") (pin "5") (pinfunction "O1_5") (pintype "bidirectional"))
      (node (ref "SSR_4DE") (pin "7") (pinfunction "O1_7") (pintype "bidirectional"))
      (node (ref "SSR_4FG") (pin "5") (pinfunction "O1_5") (pintype "bidirectional"))
      (node (ref "SSR_4FG") (pin "7") (pinfunction "O1_7") (pintype "bidirectional"))
      (node (ref "SSR_4HJ") (pin "5") (pinfunction "O1_5") (pintype "bidirectional"))
      (node (ref "SSR_4HJ") (pin "7") (pinfunction "O1_7") (pintype "bidirectional"))
    )
    (net (code "45") (name "CH4_O-") (class "Default")
      (node (ref "DRV4") (pin "14") (pinfunction "OUT-_14") (pintype "bidirectional"))
      (node (ref "P-CH3+4") (pin "1") (pinfunction "1_1") (pintype "passive"))
      (node (ref "P-CH3+4") (pin "7") (pinfunction "1_7") (pintype "passive"))
    )
    (net (code "46") (name "CH4_PA+") (class "Default")
      (node (ref "P-CH3+4") (pin "11") (pinfunction "1_11") (pintype "passive"))
      (node (ref "SSR_3J/4A") (pin "6") (pinfunction "O2_6") (pintype "bidirectional"))
    )
    (net (code "47") (name "CH4_PB+") (class "Default")
      (node (ref "P-CH3+4") (pin "10") (pinfunction "1_10") (pintype "passive"))
      (node (ref "SSR_4BC") (pin "8") (pinfunction "O2_8") (pintype "bidirectional"))
    )
    (net (code "48") (name "CH4_PC+") (class "Default")
      (node (ref "P-CH3+4") (pin "9") (pinfunction "1_9") (pintype "passive"))
      (node (ref "SSR_4BC") (pin "6") (pinfunction "O2_6") (pintype "bidirectional"))
    )
    (net (code "49") (name "CH4_PD+") (class "Default")
      (node (ref "P-CH3+4") (pin "8") (pinfunction "1_8") (pintype "passive"))
      (node (ref "SSR_4DE") (pin "8") (pinfunction "O2_8") (pintype "bidirectional"))
    )
    (net (code "50") (name "CH4_PE+") (class "Default")
      (node (ref "P-CH3+4") (pin "6") (pinfunction "1_6") (pintype "passive"))
      (node (ref "SSR_4DE") (pin "6") (pinfunction "O2_6") (pintype "bidirectional"))
    )
    (net (code "51") (name "CH4_PF+") (class "Default")
      (node (ref "P-CH3+4") (pin "5") (pinfunction "1_5") (pintype "passive"))
      (node (ref "SSR_4FG") (pin "8") (pinfunction "O2_8") (pintype "bidirectional"))
    )
    (net (code "52") (name "CH4_PG+") (class "Default")
      (node (ref "P-CH3+4") (pin "4") (pinfunction "1_4") (pintype "passive"))
      (node (ref "SSR_4FG") (pin "6") (pinfunction "O2_6") (pintype "bidirectional"))
    )
    (net (code "53") (name "CH4_PH+") (class "Default")
      (node (ref "P-CH3+4") (pin "3") (pinfunction "1_3") (pintype "passive"))
      (node (ref "SSR_4HJ") (pin "8") (pinfunction "O2_8") (pintype "bidirectional"))
    )
    (net (code "54") (name "CH4_PJ+") (class "Default")
      (node (ref "P-CH3+4") (pin "2") (pinfunction "1_2") (pintype "passive"))
      (node (ref "SSR_4HJ") (pin "6") (pinfunction "O2_6") (pintype "bidirectional"))
    )
    (net (code "55") (name "CH5_I+") (class "Default")
      (node (ref "AUDIO_IN") (pin "18") (pinfunction "18_18") (pintype "passive"))
      (node (ref "DRV5") (pin "17") (pinfunction "IN+_17") (pintype "bidirectional"))
    )
    (net (code "56") (name "CH5_I-") (class "Default")
      (node (ref "AUDIO_IN") (pin "6") (pinfunction "6_6") (pintype "passive"))
      (node (ref "DRV5") (pin "16") (pinfunction "IN-_16") (pintype "bidirectional"))
    )
    (net (code "57") (name "CH5_O+") (class "Default")
      (node (ref "DRV5") (pin "13") (pinfunction "OUT+_13") (pintype "bidirectional"))
      (node (ref "SSR_5AB") (pin "5") (pinfunction "O1_5") (pintype "bidirectional"))
      (node (ref "SSR_5AB") (pin "7") (pinfunction "O1_7") (pintype "bidirectional"))
      (node (ref "SSR_5CD") (pin "5") (pinfunction "O1_5") (pintype "bidirectional"))
      (node (ref "SSR_5CD") (pin "7") (pinfunction "O1_7") (pintype "bidirectional"))
      (node (ref "SSR_5EF") (pin "5") (pinfunction "O1_5") (pintype "bidirectional"))
      (node (ref "SSR_5EF") (pin "7") (pinfunction "O1_7") (pintype "bidirectional"))
      (node (ref "SSR_5GH") (pin "5") (pinfunction "O1_5") (pintype "bidirectional"))
      (node (ref "SSR_5GH") (pin "7") (pinfunction "O1_7") (pintype "bidirectional"))
      (node (ref "SSR_5J/6A") (pin "7") (pinfunction "O1_7") (pintype "bidirectional"))
    )
    (net (code "58") (name "CH5_O-") (class "Default")
      (node (ref "DRV5") (pin "14") (pinfunction "OUT-_14") (pintype "bidirectional"))
      (node (ref "P-CH5+6") (pin "12") (pinfunction "1_12") (pintype "passive"))
      (node (ref "P-CH5+6") (pin "18") (pinfunction "1_18") (pintype "passive"))
    )
    (net (code "59") (name "CH5_PA+") (class "Default")
      (node (ref "P-CH5+6") (pin "22") (pinfunction "1_22") (pintype "passive"))
      (node (ref "SSR_5AB") (pin "8") (pinfunction "O2_8") (pintype "bidirectional"))
    )
    (net (code "60") (name "CH5_PB+") (class "Default")
      (node (ref "P-CH5+6") (pin "21") (pinfunction "1_21") (pintype "passive"))
      (node (ref "SSR_5AB") (pin "6") (pinfunction "O2_6") (pintype "bidirectional"))
    )
    (net (code "61") (name "CH5_PC+") (class "Default")
      (node (ref "P-CH5+6") (pin "20") (pinfunction "1_20") (pintype "passive"))
      (node (ref "SSR_5CD") (pin "8") (pinfunction "O2_8") (pintype "bidirectional"))
    )
    (net (code "62") (name "CH5_PD+") (class "Default")
      (node (ref "P-CH5+6") (pin "19") (pinfunction "1_19") (pintype "passive"))
      (node (ref "SSR_5CD") (pin "6") (pinfunction "O2_6") (pintype "bidirectional"))
    )
    (net (code "63") (name "CH5_PE+") (class "Default")
      (node (ref "P-CH5+6") (pin "17") (pinfunction "1_17") (pintype "passive"))
      (node (ref "SSR_5EF") (pin "8") (pinfunction "O2_8") (pintype "bidirectional"))
    )
    (net (code "64") (name "CH5_PF+") (class "Default")
      (node (ref "P-CH5+6") (pin "16") (pinfunction "1_16") (pintype "passive"))
      (node (ref "SSR_5EF") (pin "6") (pinfunction "O2_6") (pintype "bidirectional"))
    )
    (net (code "65") (name "CH5_PG+") (class "Default")
      (node (ref "P-CH5+6") (pin "15") (pinfunction "1_15") (pintype "passive"))
      (node (ref "SSR_5GH") (pin "8") (pinfunction "O2_8") (pintype "bidirectional"))
    )
    (net (code "66") (name "CH5_PH+") (class "Default")
      (node (ref "P-CH5+6") (pin "14") (pinfunction "1_14") (pintype "passive"))
      (node (ref "SSR_5GH") (pin "6") (pinfunction "O2_6") (pintype "bidirectional"))
    )
    (net (code "67") (name "CH5_PJ+") (class "Default")
      (node (ref "P-CH5+6") (pin "13") (pinfunction "1_13") (pintype "passive"))
      (node (ref "SSR_5J/6A") (pin "8") (pinfunction "O2_8") (pintype "bidirectional"))
    )
    (net (code "68") (name "CH6_I+") (class "Default")
      (node (ref "AUDIO_IN") (pin "4") (pinfunction "4_4") (pintype "passive"))
      (node (ref "DRV6") (pin "17") (pinfunction "IN+_17") (pintype "bidirectional"))
    )
    (net (code "69") (name "CH6_I-") (class "Default")
      (node (ref "AUDIO_IN") (pin "17") (pinfunction "17_17") (pintype "passive"))
      (node (ref "DRV6") (pin "16") (pinfunction "IN-_16") (pintype "bidirectional"))
    )
    (net (code "70") (name "CH6_O+") (class "Default")
      (node (ref "DRV6") (pin "13") (pinfunction "OUT+_13") (pintype "bidirectional"))
      (node (ref "SSR_5J/6A") (pin "5") (pinfunction "O1_5") (pintype "bidirectional"))
      (node (ref "SSR_6BC") (pin "5") (pinfunction "O1_5") (pintype "bidirectional"))
      (node (ref "SSR_6BC") (pin "7") (pinfunction "O1_7") (pintype "bidirectional"))
      (node (ref "SSR_6DE") (pin "5") (pinfunction "O1_5") (pintype "bidirectional"))
      (node (ref "SSR_6DE") (pin "7") (pinfunction "O1_7") (pintype "bidirectional"))
      (node (ref "SSR_6FG") (pin "5") (pinfunction "O1_5") (pintype "bidirectional"))
      (node (ref "SSR_6FG") (pin "7") (pinfunction "O1_7") (pintype "bidirectional"))
      (node (ref "SSR_6HJ") (pin "5") (pinfunction "O1_5") (pintype "bidirectional"))
      (node (ref "SSR_6HJ") (pin "7") (pinfunction "O1_7") (pintype "bidirectional"))
    )
    (net (code "71") (name "CH6_O-") (class "Default")
      (node (ref "DRV6") (pin "14") (pinfunction "OUT-_14") (pintype "bidirectional"))
      (node (ref "P-CH5+6") (pin "1") (pinfunction "1_1") (pintype "passive"))
      (node (ref "P-CH5+6") (pin "7") (pinfunction "1_7") (pintype "passive"))
    )
    (net (code "72") (name "CH6_PA+") (class "Default")
      (node (ref "P-CH5+6") (pin "11") (pinfunction "1_11") (pintype "passive"))
      (node (ref "SSR_5J/6A") (pin "6") (pinfunction "O2_6") (pintype "bidirectional"))
    )
    (net (code "73") (name "CH6_PB+") (class "Default")
      (node (ref "P-CH5+6") (pin "10") (pinfunction "1_10") (pintype "passive"))
      (node (ref "SSR_6BC") (pin "8") (pinfunction "O2_8") (pintype "bidirectional"))
    )
    (net (code "74") (name "CH6_PC+") (class "Default")
      (node (ref "P-CH5+6") (pin "9") (pinfunction "1_9") (pintype "passive"))
      (node (ref "SSR_6BC") (pin "6") (pinfunction "O2_6") (pintype "bidirectional"))
    )
    (net (code "75") (name "CH6_PD+") (class "Default")
      (node (ref "P-CH5+6") (pin "8") (pinfunction "1_8") (pintype "passive"))
      (node (ref "SSR_6DE") (pin "8") (pinfunction "O2_8") (pintype "bidirectional"))
    )
    (net (code "76") (name "CH6_PE+") (class "Default")
      (node (ref "P-CH5+6") (pin "6") (pinfunction "1_6") (pintype "passive"))
      (node (ref "SSR_6DE") (pin "6") (pinfunction "O2_6") (pintype "bidirectional"))
    )
    (net (code "77") (name "CH6_PF+") (class "Default")
      (node (ref "P-CH5+6") (pin "5") (pinfunction "1_5") (pintype "passive"))
      (node (ref "SSR_6FG") (pin "8") (pinfunction "O2_8") (pintype "bidirectional"))
    )
    (net (code "78") (name "CH6_PG+") (class "Default")
      (node (ref "P-CH5+6") (pin "4") (pinfunction "1_4") (pintype "passive"))
      (node (ref "SSR_6FG") (pin "6") (pinfunction "O2_6") (pintype "bidirectional"))
    )
    (net (code "79") (name "CH6_PH+") (class "Default")
      (node (ref "P-CH5+6") (pin "3") (pinfunction "1_3") (pintype "passive"))
      (node (ref "SSR_6HJ") (pin "8") (pinfunction "O2_8") (pintype "bidirectional"))
    )
    (net (code "80") (name "CH6_PJ+") (class "Default")
      (node (ref "P-CH5+6") (pin "2") (pinfunction "1_2") (pintype "passive"))
      (node (ref "SSR_6HJ") (pin "6") (pinfunction "O2_6") (pintype "bidirectional"))
    )
    (net (code "81") (name "CH7_I+") (class "Default")
      (node (ref "AUDIO_IN") (pin "15") (pinfunction "15_15") (pintype "passive"))
      (node (ref "DRV7") (pin "17") (pinfunction "IN+_17") (pintype "bidirectional"))
    )
    (net (code "82") (name "CH7_I-") (class "Default")
      (node (ref "AUDIO_IN") (pin "3") (pinfunction "3_3") (pintype "passive"))
      (node (ref "DRV7") (pin "16") (pinfunction "IN-_16") (pintype "bidirectional"))
    )
    (net (code "83") (name "CH7_O+") (class "Default")
      (node (ref "DRV7") (pin "13") (pinfunction "OUT+_13") (pintype "bidirectional"))
      (node (ref "SSR_7AB") (pin "5") (pinfunction "O1_5") (pintype "bidirectional"))
      (node (ref "SSR_7AB") (pin "7") (pinfunction "O1_7") (pintype "bidirectional"))
      (node (ref "SSR_7CD") (pin "5") (pinfunction "O1_5") (pintype "bidirectional"))
      (node (ref "SSR_7CD") (pin "7") (pinfunction "O1_7") (pintype "bidirectional"))
      (node (ref "SSR_7EF") (pin "5") (pinfunction "O1_5") (pintype "bidirectional"))
      (node (ref "SSR_7EF") (pin "7") (pinfunction "O1_7") (pintype "bidirectional"))
      (node (ref "SSR_7GH") (pin "5") (pinfunction "O1_5") (pintype "bidirectional"))
      (node (ref "SSR_7GH") (pin "7") (pinfunction "O1_7") (pintype "bidirectional"))
      (node (ref "SSR_7J/8A") (pin "7") (pinfunction "O1_7") (pintype "bidirectional"))
    )
    (net (code "84") (name "CH7_O-") (class "Default")
      (node (ref "DRV7") (pin "14") (pinfunction "OUT-_14") (pintype "bidirectional"))
      (node (ref "P-CH7+8") (pin "12") (pinfunction "1_12") (pintype "passive"))
      (node (ref "P-CH7+8") (pin "18") (pinfunction "1_18") (pintype "passive"))
    )
    (net (code "85") (name "CH7_PA+") (class "Default")
      (node (ref "P-CH7+8") (pin "22") (pinfunction "1_22") (pintype "passive"))
      (node (ref "SSR_7AB") (pin "8") (pinfunction "O2_8") (pintype "bidirectional"))
    )
    (net (code "86") (name "CH7_PB+") (class "Default")
      (node (ref "P-CH7+8") (pin "21") (pinfunction "1_21") (pintype "passive"))
      (node (ref "SSR_7AB") (pin "6") (pinfunction "O2_6") (pintype "bidirectional"))
    )
    (net (code "87") (name "CH7_PC+") (class "Default")
      (node (ref "P-CH7+8") (pin "20") (pinfunction "1_20") (pintype "passive"))
      (node (ref "SSR_7CD") (pin "8") (pinfunction "O2_8") (pintype "bidirectional"))
    )
    (net (code "88") (name "CH7_PD+") (class "Default")
      (node (ref "P-CH7+8") (pin "19") (pinfunction "1_19") (pintype "passive"))
      (node (ref "SSR_7CD") (pin "6") (pinfunction "O2_6") (pintype "bidirectional"))
    )
    (net (code "89") (name "CH7_PE+") (class "Default")
      (node (ref "P-CH7+8") (pin "17") (pinfunction "1_17") (pintype "passive"))
      (node (ref "SSR_7EF") (pin "8") (pinfunction "O2_8") (pintype "bidirectional"))
    )
    (net (code "90") (name "CH7_PF+") (class "Default")
      (node (ref "P-CH7+8") (pin "16") (pinfunction "1_16") (pintype "passive"))
      (node (ref "SSR_7EF") (pin "6") (pinfunction "O2_6") (pintype "bidirectional"))
    )
    (net (code "91") (name "CH7_PG+") (class "Default")
      (node (ref "P-CH7+8") (pin "15") (pinfunction "1_15") (pintype "passive"))
      (node (ref "SSR_7GH") (pin "8") (pinfunction "O2_8") (pintype "bidirectional"))
    )
    (net (code "92") (name "CH7_PH+") (class "Default")
      (node (ref "P-CH7+8") (pin "14") (pinfunction "1_14") (pintype "passive"))
      (node (ref "SSR_7GH") (pin "6") (pinfunction "O2_6") (pintype "bidirectional"))
    )
    (net (code "93") (name "CH7_PJ+") (class "Default")
      (node (ref "P-CH7+8") (pin "13") (pinfunction "1_13") (pintype "passive"))
      (node (ref "SSR_7J/8A") (pin "8") (pinfunction "O2_8") (pintype "bidirectional"))
    )
    (net (code "94") (name "CH8_I+") (class "Default")
      (node (ref "AUDIO_IN") (pin "1") (pinfunction "1_1") (pintype "passive"))
      (node (ref "DRV8") (pin "17") (pinfunction "IN+_17") (pintype "bidirectional"))
    )
    (net (code "95") (name "CH8_I-") (class "Default")
      (node (ref "AUDIO_IN") (pin "14") (pinfunction "14_14") (pintype "passive"))
      (node (ref "DRV8") (pin "16") (pinfunction "IN-_16") (pintype "bidirectional"))
    )
    (net (code "96") (name "CH8_O+") (class "Default")
      (node (ref "DRV8") (pin "13") (pinfunction "OUT+_13") (pintype "bidirectional"))
      (node (ref "SSR_7J/8A") (pin "5") (pinfunction "O1_5") (pintype "bidirectional"))
      (node (ref "SSR_8BC") (pin "5") (pinfunction "O1_5") (pintype "bidirectional"))
      (node (ref "SSR_8BC") (pin "7") (pinfunction "O1_7") (pintype "bidirectional"))
      (node (ref "SSR_8DE") (pin "5") (pinfunction "O1_5") (pintype "bidirectional"))
      (node (ref "SSR_8DE") (pin "7") (pinfunction "O1_7") (pintype "bidirectional"))
      (node (ref "SSR_8FG") (pin "5") (pinfunction "O1_5") (pintype "bidirectional"))
      (node (ref "SSR_8FG") (pin "7") (pinfunction "O1_7") (pintype "bidirectional"))
      (node (ref "SSR_8HJ") (pin "5") (pinfunction "O1_5") (pintype "bidirectional"))
      (node (ref "SSR_8HJ") (pin "7") (pinfunction "O1_7") (pintype "bidirectional"))
    )
    (net (code "97") (name "CH8_O-") (class "Default")
      (node (ref "DRV8") (pin "14") (pinfunction "OUT-_14") (pintype "bidirectional"))
      (node (ref "P-CH7+8") (pin "1") (pinfunction "1_1") (pintype "passive"))
      (node (ref "P-CH7+8") (pin "7") (pinfunction "1_7") (pintype "passive"))
    )
    (net (code "98") (name "CH8_PA+") (class "Default")
      (node (ref "P-CH7+8") (pin "11") (pinfunction "1_11") (pintype "passive"))
      (node (ref "SSR_7J/8A") (pin "6") (pinfunction "O2_6") (pintype "bidirectional"))
    )
    (net (code "99") (name "CH8_PB+") (class "Default")
      (node (ref "P-CH7+8") (pin "10") (pinfunction "1_10") (pintype "passive"))
      (node (ref "SSR_8BC") (pin "8") (pinfunction "O2_8") (pintype "bidirectional"))
    )
    (net (code "100") (name "CH8_PC+") (class "Default")
      (node (ref "P-CH7+8") (pin "9") (pinfunction "1_9") (pintype "passive"))
      (node (ref "SSR_8BC") (pin "6") (pinfunction "O2_6") (pintype "bidirectional"))
    )
    (net (code "101") (name "CH8_PD+") (class "Default")
      (node (ref "P-CH7+8") (pin "8") (pinfunction "1_8") (pintype "passive"))
      (node (ref "SSR_8DE") (pin "8") (pinfunction "O2_8") (pintype "bidirectional"))
    )
    (net (code "102") (name "CH8_PE+") (class "Default")
      (node (ref "P-CH7+8") (pin "6") (pinfunction "1_6") (pintype "passive"))
      (node (ref "SSR_8DE") (pin "6") (pinfunction "O2_6") (pintype "bidirectional"))
    )
    (net (code "103") (name "CH8_PF+") (class "Default")
      (node (ref "P-CH7+8") (pin "5") (pinfunction "1_5") (pintype "passive"))
      (node (ref "SSR_8FG") (pin "8") (pinfunction "O2_8") (pintype "bidirectional"))
    )
    (net (code "104") (name "CH8_PG+") (class "Default")
      (node (ref "P-CH7+8") (pin "4") (pinfunction "1_4") (pintype "passive"))
      (node (ref "SSR_8FG") (pin "6") (pinfunction "O2_6") (pintype "bidirectional"))
    )
    (net (code "105") (name "CH8_PH+") (class "Default")
      (node (ref "P-CH7+8") (pin "3") (pinfunction "1_3") (pintype "passive"))
      (node (ref "SSR_8HJ") (pin "8") (pinfunction "O2_8") (pintype "bidirectional"))
    )
    (net (code "106") (name "CH8_PJ+") (class "Default")
      (node (ref "P-CH7+8") (pin "2") (pinfunction "1_2") (pintype "passive"))
      (node (ref "SSR_8HJ") (pin "6") (pinfunction "O2_6") (pintype "bidirectional"))
    )
    (net (code "107") (name "GND") (class "Default")
      (node (ref "AUDIO_IN") (pin "11") (pinfunction "11_11") (pintype "passive"))
      (node (ref "AUDIO_IN") (pin "16") (pinfunction "16_16") (pintype "passive"))
      (node (ref "AUDIO_IN") (pin "19") (pinfunction "19_19") (pintype "passive"))
      (node (ref "AUDIO_IN") (pin "2") (pinfunction "2_2") (pintype "passive"))
      (node (ref "AUDIO_IN") (pin "22") (pinfunction "22_22") (pintype "passive"))
      (node (ref "AUDIO_IN") (pin "25") (pinfunction "25_25") (pintype "passive"))
      (node (ref "AUDIO_IN") (pin "5") (pinfunction "5_5") (pintype "passive"))
      (node (ref "AUDIO_IN") (pin "8") (pinfunction "8_8") (pintype "passive"))
      (node (ref "GND_LIFT") (pin "1") (pinfunction "T1A_1") (pintype "bidirectional"))
      (node (ref "GND_LIFT") (pin "6") (pinfunction "T2A_6") (pintype "bidirectional"))
    )
    (net (code "108") (name "LED1") (class "Default")
      (node (ref "ARDUINO_D") (pin "10") (pinfunction "10_10") (pintype "passive"))
      (node (ref "RLED1") (pin "1") (pinfunction "1_1") (pintype "passive"))
    )
    (net (code "109") (name "LED2") (class "Default")
      (node (ref "ARDUINO_D") (pin "8") (pinfunction "8_8") (pintype "passive"))
      (node (ref "RLED2") (pin "1") (pinfunction "1_1") (pintype "passive"))
    )
    (net (code "110") (name "LED3") (class "Default")
      (node (ref "ARDUINO_D") (pin "7") (pinfunction "7_7") (pintype "passive"))
      (node (ref "RLED3") (pin "1") (pinfunction "1_1") (pintype "passive"))
    )
    (net (code "111") (name "Net-(DRV1-FB)") (class "Default")
      (node (ref "DRV1") (pin "3") (pinfunction "FB_3") (pintype "bidirectional"))
      (node (ref "RVBST1-1") (pin "1") (pinfunction "1_1") (pintype "passive"))
      (node (ref "RVBST1-2") (pin "2") (pinfunction "2_2") (pintype "passive"))
    )
    (net (code "112") (name "Net-(DRV1-PVDD)") (class "Default")
      (node (ref "CVBST1") (pin "1") (pinfunction "1_1") (pintype "passive"))
      (node (ref "DRV1") (pin "10") (pinfunction "VBST_10") (pintype "bidirectional"))
      (node (ref "DRV1") (pin "11") (pinfunction "VBST_11") (pintype "bidirectional"))
      (node (ref "DRV1") (pin "12") (pinfunction "PVDD_12") (pintype "bidirectional"))
      (node (ref "RVBST1-1") (pin "2") (pinfunction "2_2") (pintype "passive"))
    )
    (net (code "113") (name "Net-(DRV1-REXT)") (class "Default")
      (node (ref "DRV1") (pin "15") (pinfunction "REXT_15") (pintype "bidirectional"))
      (node (ref "REXT1") (pin "2") (pinfunction "2_2") (pintype "passive"))
    )
    (net (code "114") (name "Net-(DRV1-SW-Pad7)") (class "Default")
      (node (ref "DRV1") (pin "7") (pinfunction "SW_7") (pintype "bidirectional"))
      (node (ref "DRV1") (pin "8") (pinfunction "SW_8") (pintype "bidirectional"))
      (node (ref "L1") (pin "1") (pinfunction "1_1") (pintype "passive"))
    )
    (net (code "115") (name "Net-(DRV1-VPUMP)") (class "Default")
      (node (ref "CPUMP1") (pin "1") (pinfunction "1_1") (pintype "passive"))
      (node (ref "DRV1") (pin "1") (pinfunction "VPUMP_1") (pintype "bidirectional"))
    )
    (net (code "116") (name "Net-(DRV1-VREG)") (class "Default")
      (node (ref "CVREG1") (pin "1") (pinfunction "1_1") (pintype "passive"))
      (node (ref "DRV1") (pin "20") (pinfunction "VREG_20") (pintype "bidirectional"))
    )
    (net (code "117") (name "Net-(DRV2-FB)") (class "Default")
      (node (ref "DRV2") (pin "3") (pinfunction "FB_3") (pintype "bidirectional"))
      (node (ref "RVBST2-1") (pin "1") (pinfunction "1_1") (pintype "passive"))
      (node (ref "RVBST2-2") (pin "2") (pinfunction "2_2") (pintype "passive"))
    )
    (net (code "118") (name "Net-(DRV2-PVDD)") (class "Default")
      (node (ref "CVBST2") (pin "1") (pinfunction "1_1") (pintype "passive"))
      (node (ref "DRV2") (pin "10") (pinfunction "VBST_10") (pintype "bidirectional"))
      (node (ref "DRV2") (pin "11") (pinfunction "VBST_11") (pintype "bidirectional"))
      (node (ref "DRV2") (pin "12") (pinfunction "PVDD_12") (pintype "bidirectional"))
      (node (ref "RVBST2-1") (pin "2") (pinfunction "2_2") (pintype "passive"))
    )
    (net (code "119") (name "Net-(DRV2-REXT)") (class "Default")
      (node (ref "DRV2") (pin "15") (pinfunction "REXT_15") (pintype "bidirectional"))
      (node (ref "REXT2") (pin "2") (pinfunction "2_2") (pintype "passive"))
    )
    (net (code "120") (name "Net-(DRV2-SW-Pad7)") (class "Default")
      (node (ref "DRV2") (pin "7") (pinfunction "SW_7") (pintype "bidirectional"))
      (node (ref "DRV2") (pin "8") (pinfunction "SW_8") (pintype "bidirectional"))
      (node (ref "L2") (pin "1") (pinfunction "1_1") (pintype "passive"))
    )
    (net (code "121") (name "Net-(DRV2-VPUMP)") (class "Default")
      (node (ref "CPUMP2") (pin "1") (pinfunction "1_1") (pintype "passive"))
      (node (ref "DRV2") (pin "1") (pinfunction "VPUMP_1") (pintype "bidirectional"))
    )
    (net (code "122") (name "Net-(DRV2-VREG)") (class "Default")
      (node (ref "CVREG2") (pin "1") (pinfunction "1_1") (pintype "passive"))
      (node (ref "DRV2") (pin "20") (pinfunction "VREG_20") (pintype "bidirectional"))
    )
    (net (code "123") (name "Net-(DRV3-FB)") (class "Default")
      (node (ref "DRV3") (pin "3") (pinfunction "FB_3") (pintype "bidirectional"))
      (node (ref "RVBST3-1") (pin "1") (pinfunction "1_1") (pintype "passive"))
      (node (ref "RVBST3-2") (pin "2") (pinfunction "2_2") (pintype "passive"))
    )
    (net (code "124") (name "Net-(DRV3-PVDD)") (class "Default")
      (node (ref "CVBST3") (pin "1") (pinfunction "1_1") (pintype "passive"))
      (node (ref "DRV3") (pin "10") (pinfunction "VBST_10") (pintype "bidirectional"))
      (node (ref "DRV3") (pin "11") (pinfunction "VBST_11") (pintype "bidirectional"))
      (node (ref "DRV3") (pin "12") (pinfunction "PVDD_12") (pintype "bidirectional"))
      (node (ref "RVBST3-1") (pin "2") (pinfunction "2_2") (pintype "passive"))
    )
    (net (code "125") (name "Net-(DRV3-REXT)") (class "Default")
      (node (ref "DRV3") (pin "15") (pinfunction "REXT_15") (pintype "bidirectional"))
      (node (ref "REXT3") (pin "2") (pinfunction "2_2") (pintype "passive"))
    )
    (net (code "126") (name "Net-(DRV3-SW-Pad7)") (class "Default")
      (node (ref "DRV3") (pin "7") (pinfunction "SW_7") (pintype "bidirectional"))
      (node (ref "DRV3") (pin "8") (pinfunction "SW_8") (pintype "bidirectional"))
      (node (ref "L3") (pin "1") (pinfunction "1_1") (pintype "passive"))
    )
    (net (code "127") (name "Net-(DRV3-VPUMP)") (class "Default")
      (node (ref "CPUMP3") (pin "1") (pinfunction "1_1") (pintype "passive"))
      (node (ref "DRV3") (pin "1") (pinfunction "VPUMP_1") (pintype "bidirectional"))
    )
    (net (code "128") (name "Net-(DRV3-VREG)") (class "Default")
      (node (ref "CVREG3") (pin "1") (pinfunction "1_1") (pintype "passive"))
      (node (ref "DRV3") (pin "20") (pinfunction "VREG_20") (pintype "bidirectional"))
    )
    (net (code "129") (name "Net-(DRV4-FB)") (class "Default")
      (node (ref "DRV4") (pin "3") (pinfunction "FB_3") (pintype "bidirectional"))
      (node (ref "RVBST4-1") (pin "1") (pinfunction "1_1") (pintype "passive"))
      (node (ref "RVBST4-2") (pin "2") (pinfunction "2_2") (pintype "passive"))
    )
    (net (code "130") (name "Net-(DRV4-PVDD)") (class "Default")
      (node (ref "CVBST4") (pin "1") (pinfunction "1_1") (pintype "passive"))
      (node (ref "DRV4") (pin "10") (pinfunction "VBST_10") (pintype "bidirectional"))
      (node (ref "DRV4") (pin "11") (pinfunction "VBST_11") (pintype "bidirectional"))
      (node (ref "DRV4") (pin "12") (pinfunction "PVDD_12") (pintype "bidirectional"))
      (node (ref "RVBST4-1") (pin "2") (pinfunction "2_2") (pintype "passive"))
    )
    (net (code "131") (name "Net-(DRV4-REXT)") (class "Default")
      (node (ref "DRV4") (pin "15") (pinfunction "REXT_15") (pintype "bidirectional"))
      (node (ref "REXT4") (pin "2") (pinfunction "2_2") (pintype "passive"))
    )
    (net (code "132") (name "Net-(DRV4-SW-Pad7)") (class "Default")
      (node (ref "DRV4") (pin "7") (pinfunction "SW_7") (pintype "bidirectional"))
      (node (ref "DRV4") (pin "8") (pinfunction "SW_8") (pintype "bidirectional"))
      (node (ref "L4") (pin "1") (pinfunction "1_1") (pintype "passive"))
    )
    (net (code "133") (name "Net-(DRV4-VPUMP)") (class "Default")
      (node (ref "CPUMP4") (pin "1") (pinfunction "1_1") (pintype "passive"))
      (node (ref "DRV4") (pin "1") (pinfunction "VPUMP_1") (pintype "bidirectional"))
    )
    (net (code "134") (name "Net-(DRV4-VREG)") (class "Default")
      (node (ref "CVREG4") (pin "1") (pinfunction "1_1") (pintype "passive"))
      (node (ref "DRV4") (pin "20") (pinfunction "VREG_20") (pintype "bidirectional"))
    )
    (net (code "135") (name "Net-(DRV5-FB)") (class "Default")
      (node (ref "DRV5") (pin "3") (pinfunction "FB_3") (pintype "bidirectional"))
      (node (ref "RVBST5-1") (pin "1") (pinfunction "1_1") (pintype "passive"))
      (node (ref "RVBST5-2") (pin "2") (pinfunction "2_2") (pintype "passive"))
    )
    (net (code "136") (name "Net-(DRV5-PVDD)") (class "Default")
      (node (ref "CVBST5") (pin "1") (pinfunction "1_1") (pintype "passive"))
      (node (ref "DRV5") (pin "10") (pinfunction "VBST_10") (pintype "bidirectional"))
      (node (ref "DRV5") (pin "11") (pinfunction "VBST_11") (pintype "bidirectional"))
      (node (ref "DRV5") (pin "12") (pinfunction "PVDD_12") (pintype "bidirectional"))
      (node (ref "RVBST5-1") (pin "2") (pinfunction "2_2") (pintype "passive"))
    )
    (net (code "137") (name "Net-(DRV5-REXT)") (class "Default")
      (node (ref "DRV5") (pin "15") (pinfunction "REXT_15") (pintype "bidirectional"))
      (node (ref "REXT5") (pin "2") (pinfunction "2_2") (pintype "passive"))
    )
    (net (code "138") (name "Net-(DRV5-SW-Pad7)") (class "Default")
      (node (ref "DRV5") (pin "7") (pinfunction "SW_7") (pintype "bidirectional"))
      (node (ref "DRV5") (pin "8") (pinfunction "SW_8") (pintype "bidirectional"))
      (node (ref "L5") (pin "1") (pinfunction "1_1") (pintype "passive"))
    )
    (net (code "139") (name "Net-(DRV5-VPUMP)") (class "Default")
      (node (ref "CPUMP5") (pin "1") (pinfunction "1_1") (pintype "passive"))
      (node (ref "DRV5") (pin "1") (pinfunction "VPUMP_1") (pintype "bidirectional"))
    )
    (net (code "140") (name "Net-(DRV5-VREG)") (class "Default")
      (node (ref "CVREG5") (pin "1") (pinfunction "1_1") (pintype "passive"))
      (node (ref "DRV5") (pin "20") (pinfunction "VREG_20") (pintype "bidirectional"))
    )
    (net (code "141") (name "Net-(DRV6-FB)") (class "Default")
      (node (ref "DRV6") (pin "3") (pinfunction "FB_3") (pintype "bidirectional"))
      (node (ref "RVBST6-1") (pin "1") (pinfunction "1_1") (pintype "passive"))
      (node (ref "RVBST6-2") (pin "2") (pinfunction "2_2") (pintype "passive"))
    )
    (net (code "142") (name "Net-(DRV6-PVDD)") (class "Default")
      (node (ref "CVBST6") (pin "1") (pinfunction "1_1") (pintype "passive"))
      (node (ref "DRV6") (pin "10") (pinfunction "VBST_10") (pintype "bidirectional"))
      (node (ref "DRV6") (pin "11") (pinfunction "VBST_11") (pintype "bidirectional"))
      (node (ref "DRV6") (pin "12") (pinfunction "PVDD_12") (pintype "bidirectional"))
      (node (ref "RVBST6-1") (pin "2") (pinfunction "2_2") (pintype "passive"))
    )
    (net (code "143") (name "Net-(DRV6-REXT)") (class "Default")
      (node (ref "DRV6") (pin "15") (pinfunction "REXT_15") (pintype "bidirectional"))
      (node (ref "REXT6") (pin "2") (pinfunction "2_2") (pintype "passive"))
    )
    (net (code "144") (name "Net-(DRV6-SW-Pad7)") (class "Default")
      (node (ref "DRV6") (pin "7") (pinfunction "SW_7") (pintype "bidirectional"))
      (node (ref "DRV6") (pin "8") (pinfunction "SW_8") (pintype "bidirectional"))
      (node (ref "L6") (pin "1") (pinfunction "1_1") (pintype "passive"))
    )
    (net (code "145") (name "Net-(DRV6-VPUMP)") (class "Default")
      (node (ref "CPUMP6") (pin "1") (pinfunction "1_1") (pintype "passive"))
      (node (ref "DRV6") (pin "1") (pinfunction "VPUMP_1") (pintype "bidirectional"))
    )
    (net (code "146") (name "Net-(DRV6-VREG)") (class "Default")
      (node (ref "CVREG6") (pin "1") (pinfunction "1_1") (pintype "passive"))
      (node (ref "DRV6") (pin "20") (pinfunction "VREG_20") (pintype "bidirectional"))
    )
    (net (code "147") (name "Net-(DRV7-FB)") (class "Default")
      (node (ref "DRV7") (pin "3") (pinfunction "FB_3") (pintype "bidirectional"))
      (node (ref "RVBST7-1") (pin "1") (pinfunction "1_1") (pintype "passive"))
      (node (ref "RVBST7-2") (pin "2") (pinfunction "2_2") (pintype "passive"))
    )
    (net (code "148") (name "Net-(DRV7-PVDD)") (class "Default")
      (node (ref "CVBST7") (pin "1") (pinfunction "1_1") (pintype "passive"))
      (node (ref "DRV7") (pin "10") (pinfunction "VBST_10") (pintype "bidirectional"))
      (node (ref "DRV7") (pin "11") (pinfunction "VBST_11") (pintype "bidirectional"))
      (node (ref "DRV7") (pin "12") (pinfunction "PVDD_12") (pintype "bidirectional"))
      (node (ref "RVBST7-1") (pin "2") (pinfunction "2_2") (pintype "passive"))
    )
    (net (code "149") (name "Net-(DRV7-REXT)") (class "Default")
      (node (ref "DRV7") (pin "15") (pinfunction "REXT_15") (pintype "bidirectional"))
      (node (ref "REXT7") (pin "2") (pinfunction "2_2") (pintype "passive"))
    )
    (net (code "150") (name "Net-(DRV7-SW-Pad7)") (class "Default")
      (node (ref "DRV7") (pin "7") (pinfunction "SW_7") (pintype "bidirectional"))
      (node (ref "DRV7") (pin "8") (pinfunction "SW_8") (pintype "bidirectional"))
      (node (ref "L7") (pin "1") (pinfunction "1_1") (pintype "passive"))
    )
    (net (code "151") (name "Net-(DRV7-VPUMP)") (class "Default")
      (node (ref "CPUMP7") (pin "1") (pinfunction "1_1") (pintype "passive"))
      (node (ref "DRV7") (pin "1") (pinfunction "VPUMP_1") (pintype "bidirectional"))
    )
    (net (code "152") (name "Net-(DRV7-VREG)") (class "Default")
      (node (ref "CVREG7") (pin "1") (pinfunction "1_1") (pintype "passive"))
      (node (ref "DRV7") (pin "20") (pinfunction "VREG_20") (pintype "bidirectional"))
    )
    (net (code "153") (name "Net-(DRV8-FB)") (class "Default")
      (node (ref "DRV8") (pin "3") (pinfunction "FB_3") (pintype "bidirectional"))
      (node (ref "RVBST8-1") (pin "1") (pinfunction "1_1") (pintype "passive"))
      (node (ref "RVBST8-2") (pin "2") (pinfunction "2_2") (pintype "passive"))
    )
    (net (code "154") (name "Net-(DRV8-PVDD)") (class "Default")
      (node (ref "CVBST8") (pin "1") (pinfunction "1_1") (pintype "passive"))
      (node (ref "DRV8") (pin "10") (pinfunction "VBST_10") (pintype "bidirectional"))
      (node (ref "DRV8") (pin "11") (pinfunction "VBST_11") (pintype "bidirectional"))
      (node (ref "DRV8") (pin "12") (pinfunction "PVDD_12") (pintype "bidirectional"))
      (node (ref "RVBST8-1") (pin "2") (pinfunction "2_2") (pintype "passive"))
    )
    (net (code "155") (name "Net-(DRV8-REXT)") (class "Default")
      (node (ref "DRV8") (pin "15") (pinfunction "REXT_15") (pintype "bidirectional"))
      (node (ref "REXT8") (pin "2") (pinfunction "2_2") (pintype "passive"))
    )
    (net (code "156") (name "Net-(DRV8-SW-Pad7)") (class "Default")
      (node (ref "DRV8") (pin "7") (pinfunction "SW_7") (pintype "bidirectional"))
      (node (ref "DRV8") (pin "8") (pinfunction "SW_8") (pintype "bidirectional"))
      (node (ref "L8") (pin "1") (pinfunction "1_1") (pintype "passive"))
    )
    (net (code "157") (name "Net-(DRV8-VPUMP)") (class "Default")
      (node (ref "CPUMP8") (pin "1") (pinfunction "1_1") (pintype "passive"))
      (node (ref "DRV8") (pin "1") (pinfunction "VPUMP_1") (pintype "bidirectional"))
    )
    (net (code "158") (name "Net-(DRV8-VREG)") (class "Default")
      (node (ref "CVREG8") (pin "1") (pinfunction "1_1") (pintype "passive"))
      (node (ref "DRV8") (pin "20") (pinfunction "VREG_20") (pintype "bidirectional"))
    )
    (net (code "159") (name "Net-(GND_LIFT-P1)") (class "Default")
      (node (ref "GND_LIFT") (pin "2") (pinfunction "P1_2") (pintype "bidirectional"))
      (node (ref "GND_LIFT") (pin "5") (pinfunction "P2_5") (pintype "bidirectional"))
      (node (ref "R_LIFT1") (pin "2") (pinfunction "2_2") (pintype "passive"))
      (node (ref "R_LIFT2") (pin "1") (pinfunction "1_1") (pintype "passive"))
    )
    (net (code "160") (name "Net-(LED1-PadC)") (class "Default")
      (node (ref "LED1") (pin "C") (pinfunction "C_C") (pintype "passive"))
      (node (ref "RLED1") (pin "2") (pinfunction "2_2") (pintype "passive"))
    )
    (net (code "161") (name "Net-(LED2-PadC)") (class "Default")
      (node (ref "LED2") (pin "C") (pinfunction "C_C") (pintype "passive"))
      (node (ref "RLED2") (pin "2") (pinfunction "2_2") (pintype "passive"))
    )
    (net (code "162") (name "Net-(LED3-PadC)") (class "Default")
      (node (ref "LED3") (pin "C") (pinfunction "C_C") (pintype "passive"))
      (node (ref "RLED3") (pin "2") (pinfunction "2_2") (pintype "passive"))
    )
    (net (code "163") (name "Net-(LED_SUP-PadA)") (class "Default")
      (node (ref "LED_SUP") (pin "A") (pinfunction "A_A") (pintype "passive"))
      (node (ref "RLED_SUP") (pin "1") (pinfunction "1_1") (pintype "passive"))
    )
    (net (code "164") (name "Net-(SSR_1ABA-I+)") (class "Default")
      (node (ref "R_1A") (pin "1") (pinfunction "1_1") (pintype "passive"))
      (node (ref "SSR_1AB") (pin "1") (pinfunction "I+_1") (pintype "bidirectional"))
    )
    (net (code "165") (name "Net-(SSR_1ABB-I+)") (class "Default")
      (node (ref "R_1B") (pin "1") (pinfunction "1_1") (pintype "passive"))
      (node (ref "SSR_1AB") (pin "3") (pinfunction "I+_3") (pintype "bidirectional"))
    )
    (net (code "166") (name "Net-(SSR_1CDA-I+)") (class "Default")
      (node (ref "R_1C") (pin "1") (pinfunction "1_1") (pintype "passive"))
      (node (ref "SSR_1CD") (pin "1") (pinfunction "I+_1") (pintype "bidirectional"))
    )
    (net (code "167") (name "Net-(SSR_1CDB-I+)") (class "Default")
      (node (ref "R_1D") (pin "1") (pinfunction "1_1") (pintype "passive"))
      (node (ref "SSR_1CD") (pin "3") (pinfunction "I+_3") (pintype "bidirectional"))
    )
    (net (code "168") (name "Net-(SSR_1EFA-I+)") (class "Default")
      (node (ref "R_1E") (pin "1") (pinfunction "1_1") (pintype "passive"))
      (node (ref "SSR_1EF") (pin "1") (pinfunction "I+_1") (pintype "bidirectional"))
    )
    (net (code "169") (name "Net-(SSR_1EFB-I+)") (class "Default")
      (node (ref "R_1F") (pin "1") (pinfunction "1_1") (pintype "passive"))
      (node (ref "SSR_1EF") (pin "3") (pinfunction "I+_3") (pintype "bidirectional"))
    )
    (net (code "170") (name "Net-(SSR_1GHA-I+)") (class "Default")
      (node (ref "R_1G") (pin "1") (pinfunction "1_1") (pintype "passive"))
      (node (ref "SSR_1GH") (pin "1") (pinfunction "I+_1") (pintype "bidirectional"))
    )
    (net (code "171") (name "Net-(SSR_1GHB-I+)") (class "Default")
      (node (ref "R_1H") (pin "1") (pinfunction "1_1") (pintype "passive"))
      (node (ref "SSR_1GH") (pin "3") (pinfunction "I+_3") (pintype "bidirectional"))
    )
    (net (code "172") (name "Net-(SSR_1J/2AA-I+)") (class "Default")
      (node (ref "R_1J") (pin "1") (pinfunction "1_1") (pintype "passive"))
      (node (ref "SSR_1J/2A") (pin "1") (pinfunction "I+_1") (pintype "bidirectional"))
    )
    (net (code "173") (name "Net-(SSR_1J/2AB-I+)") (class "Default")
      (node (ref "R_2A") (pin "1") (pinfunction "1_1") (pintype "passive"))
      (node (ref "SSR_1J/2A") (pin "3") (pinfunction "I+_3") (pintype "bidirectional"))
    )
    (net (code "174") (name "Net-(SSR_2BCA-I+)") (class "Default")
      (node (ref "R_2B") (pin "1") (pinfunction "1_1") (pintype "passive"))
      (node (ref "SSR_2BC") (pin "1") (pinfunction "I+_1") (pintype "bidirectional"))
    )
    (net (code "175") (name "Net-(SSR_2BCB-I+)") (class "Default")
      (node (ref "R_2C") (pin "1") (pinfunction "1_1") (pintype "passive"))
      (node (ref "SSR_2BC") (pin "3") (pinfunction "I+_3") (pintype "bidirectional"))
    )
    (net (code "176") (name "Net-(SSR_2DEA-I+)") (class "Default")
      (node (ref "R_2D") (pin "1") (pinfunction "1_1") (pintype "passive"))
      (node (ref "SSR_2DE") (pin "1") (pinfunction "I+_1") (pintype "bidirectional"))
    )
    (net (code "177") (name "Net-(SSR_2DEB-I+)") (class "Default")
      (node (ref "R_2E") (pin "1") (pinfunction "1_1") (pintype "passive"))
      (node (ref "SSR_2DE") (pin "3") (pinfunction "I+_3") (pintype "bidirectional"))
    )
    (net (code "178") (name "Net-(SSR_2FGA-I+)") (class "Default")
      (node (ref "R_2F") (pin "1") (pinfunction "1_1") (pintype "passive"))
      (node (ref "SSR_2FG") (pin "1") (pinfunction "I+_1") (pintype "bidirectional"))
    )
    (net (code "179") (name "Net-(SSR_2FGB-I+)") (class "Default")
      (node (ref "R_2G") (pin "1") (pinfunction "1_1") (pintype "passive"))
      (node (ref "SSR_2FG") (pin "3") (pinfunction "I+_3") (pintype "bidirectional"))
    )
    (net (code "180") (name "Net-(SSR_2HJA-I+)") (class "Default")
      (node (ref "R_2H") (pin "1") (pinfunction "1_1") (pintype "passive"))
      (node (ref "SSR_2HJ") (pin "1") (pinfunction "I+_1") (pintype "bidirectional"))
    )
    (net (code "181") (name "Net-(SSR_2HJB-I+)") (class "Default")
      (node (ref "R_2J") (pin "1") (pinfunction "1_1") (pintype "passive"))
      (node (ref "SSR_2HJ") (pin "3") (pinfunction "I+_3") (pintype "bidirectional"))
    )
    (net (code "182") (name "Net-(SSR_3ABA-I+)") (class "Default")
      (node (ref "R_3A") (pin "1") (pinfunction "1_1") (pintype "passive"))
      (node (ref "SSR_3AB") (pin "1") (pinfunction "I+_1") (pintype "bidirectional"))
    )
    (net (code "183") (name "Net-(SSR_3ABB-I+)") (class "Default")
      (node (ref "R_3B") (pin "1") (pinfunction "1_1") (pintype "passive"))
      (node (ref "SSR_3AB") (pin "3") (pinfunction "I+_3") (pintype "bidirectional"))
    )
    (net (code "184") (name "Net-(SSR_3CDA-I+)") (class "Default")
      (node (ref "R_3C") (pin "1") (pinfunction "1_1") (pintype "passive"))
      (node (ref "SSR_3CD") (pin "1") (pinfunction "I+_1") (pintype "bidirectional"))
    )
    (net (code "185") (name "Net-(SSR_3CDB-I+)") (class "Default")
      (node (ref "R_3D") (pin "1") (pinfunction "1_1") (pintype "passive"))
      (node (ref "SSR_3CD") (pin "3") (pinfunction "I+_3") (pintype "bidirectional"))
    )
    (net (code "186") (name "Net-(SSR_3EFA-I+)") (class "Default")
      (node (ref "R_3E") (pin "1") (pinfunction "1_1") (pintype "passive"))
      (node (ref "SSR_3EF") (pin "1") (pinfunction "I+_1") (pintype "bidirectional"))
    )
    (net (code "187") (name "Net-(SSR_3EFB-I+)") (class "Default")
      (node (ref "R_3F") (pin "1") (pinfunction "1_1") (pintype "passive"))
      (node (ref "SSR_3EF") (pin "3") (pinfunction "I+_3") (pintype "bidirectional"))
    )
    (net (code "188") (name "Net-(SSR_3GHA-I+)") (class "Default")
      (node (ref "R_3G") (pin "1") (pinfunction "1_1") (pintype "passive"))
      (node (ref "SSR_3GH") (pin "1") (pinfunction "I+_1") (pintype "bidirectional"))
    )
    (net (code "189") (name "Net-(SSR_3GHB-I+)") (class "Default")
      (node (ref "R_3H") (pin "1") (pinfunction "1_1") (pintype "passive"))
      (node (ref "SSR_3GH") (pin "3") (pinfunction "I+_3") (pintype "bidirectional"))
    )
    (net (code "190") (name "Net-(SSR_3J/4AA-I+)") (class "Default")
      (node (ref "R_3J") (pin "1") (pinfunction "1_1") (pintype "passive"))
      (node (ref "SSR_3J/4A") (pin "1") (pinfunction "I+_1") (pintype "bidirectional"))
    )
    (net (code "191") (name "Net-(SSR_3J/4AB-I+)") (class "Default")
      (node (ref "R_4A") (pin "1") (pinfunction "1_1") (pintype "passive"))
      (node (ref "SSR_3J/4A") (pin "3") (pinfunction "I+_3") (pintype "bidirectional"))
    )
    (net (code "192") (name "Net-(SSR_4BCA-I+)") (class "Default")
      (node (ref "R_4B") (pin "1") (pinfunction "1_1") (pintype "passive"))
      (node (ref "SSR_4BC") (pin "1") (pinfunction "I+_1") (pintype "bidirectional"))
    )
    (net (code "193") (name "Net-(SSR_4BCB-I+)") (class "Default")
      (node (ref "R_4C") (pin "1") (pinfunction "1_1") (pintype "passive"))
      (node (ref "SSR_4BC") (pin "3") (pinfunction "I+_3") (pintype "bidirectional"))
    )
    (net (code "194") (name "Net-(SSR_4DEA-I+)") (class "Default")
      (node (ref "R_4D") (pin "1") (pinfunction "1_1") (pintype "passive"))
      (node (ref "SSR_4DE") (pin "1") (pinfunction "I+_1") (pintype "bidirectional"))
    )
    (net (code "195") (name "Net-(SSR_4DEB-I+)") (class "Default")
      (node (ref "R_4E") (pin "1") (pinfunction "1_1") (pintype "passive"))
      (node (ref "SSR_4DE") (pin "3") (pinfunction "I+_3") (pintype "bidirectional"))
    )
    (net (code "196") (name "Net-(SSR_4FGA-I+)") (class "Default")
      (node (ref "R_4F") (pin "1") (pinfunction "1_1") (pintype "passive"))
      (node (ref "SSR_4FG") (pin "1") (pinfunction "I+_1") (pintype "bidirectional"))
    )
    (net (code "197") (name "Net-(SSR_4FGB-I+)") (class "Default")
      (node (ref "R_4G") (pin "1") (pinfunction "1_1") (pintype "passive"))
      (node (ref "SSR_4FG") (pin "3") (pinfunction "I+_3") (pintype "bidirectional"))
    )
    (net (code "198") (name "Net-(SSR_4HJA-I+)") (class "Default")
      (node (ref "R_4H") (pin "1") (pinfunction "1_1") (pintype "passive"))
      (node (ref "SSR_4HJ") (pin "1") (pinfunction "I+_1") (pintype "bidirectional"))
    )
    (net (code "199") (name "Net-(SSR_4HJB-I+)") (class "Default")
      (node (ref "R_4J") (pin "1") (pinfunction "1_1") (pintype "passive"))
      (node (ref "SSR_4HJ") (pin "3") (pinfunction "I+_3") (pintype "bidirectional"))
    )
    (net (code "200") (name "Net-(SSR_5ABA-I+)") (class "Default")
      (node (ref "R_5A") (pin "1") (pinfunction "1_1") (pintype "passive"))
      (node (ref "SSR_5AB") (pin "1") (pinfunction "I+_1") (pintype "bidirectional"))
    )
    (net (code "201") (name "Net-(SSR_5ABB-I+)") (class "Default")
      (node (ref "R_5B") (pin "1") (pinfunction "1_1") (pintype "passive"))
      (node (ref "SSR_5AB") (pin "3") (pinfunction "I+_3") (pintype "bidirectional"))
    )
    (net (code "202") (name "Net-(SSR_5CDA-I+)") (class "Default")
      (node (ref "R_5C") (pin "1") (pinfunction "1_1") (pintype "passive"))
      (node (ref "SSR_5CD") (pin "1") (pinfunction "I+_1") (pintype "bidirectional"))
    )
    (net (code "203") (name "Net-(SSR_5CDB-I+)") (class "Default")
      (node (ref "R_5D") (pin "1") (pinfunction "1_1") (pintype "passive"))
      (node (ref "SSR_5CD") (pin "3") (pinfunction "I+_3") (pintype "bidirectional"))
    )
    (net (code "204") (name "Net-(SSR_5EFA-I+)") (class "Default")
      (node (ref "R_5E") (pin "1") (pinfunction "1_1") (pintype "passive"))
      (node (ref "SSR_5EF") (pin "1") (pinfunction "I+_1") (pintype "bidirectional"))
    )
    (net (code "205") (name "Net-(SSR_5EFB-I+)") (class "Default")
      (node (ref "R_5F") (pin "1") (pinfunction "1_1") (pintype "passive"))
      (node (ref "SSR_5EF") (pin "3") (pinfunction "I+_3") (pintype "bidirectional"))
    )
    (net (code "206") (name "Net-(SSR_5GHA-I+)") (class "Default")
      (node (ref "R_5G") (pin "1") (pinfunction "1_1") (pintype "passive"))
      (node (ref "SSR_5GH") (pin "1") (pinfunction "I+_1") (pintype "bidirectional"))
    )
    (net (code "207") (name "Net-(SSR_5GHB-I+)") (class "Default")
      (node (ref "R_5H") (pin "1") (pinfunction "1_1") (pintype "passive"))
      (node (ref "SSR_5GH") (pin "3") (pinfunction "I+_3") (pintype "bidirectional"))
    )
    (net (code "208") (name "Net-(SSR_5J/6AA-I+)") (class "Default")
      (node (ref "R_5J") (pin "1") (pinfunction "1_1") (pintype "passive"))
      (node (ref "SSR_5J/6A") (pin "1") (pinfunction "I+_1") (pintype "bidirectional"))
    )
    (net (code "209") (name "Net-(SSR_5J/6AB-I+)") (class "Default")
      (node (ref "R_6A") (pin "1") (pinfunction "1_1") (pintype "passive"))
      (node (ref "SSR_5J/6A") (pin "3") (pinfunction "I+_3") (pintype "bidirectional"))
    )
    (net (code "210") (name "Net-(SSR_6BCA-I+)") (class "Default")
      (node (ref "R_6B") (pin "1") (pinfunction "1_1") (pintype "passive"))
      (node (ref "SSR_6BC") (pin "1") (pinfunction "I+_1") (pintype "bidirectional"))
    )
    (net (code "211") (name "Net-(SSR_6BCB-I+)") (class "Default")
      (node (ref "R_6C") (pin "1") (pinfunction "1_1") (pintype "passive"))
      (node (ref "SSR_6BC") (pin "3") (pinfunction "I+_3") (pintype "bidirectional"))
    )
    (net (code "212") (name "Net-(SSR_6DEA-I+)") (class "Default")
      (node (ref "R_6D") (pin "1") (pinfunction "1_1") (pintype "passive"))
      (node (ref "SSR_6DE") (pin "1") (pinfunction "I+_1") (pintype "bidirectional"))
    )
    (net (code "213") (name "Net-(SSR_6DEB-I+)") (class "Default")
      (node (ref "R_6E") (pin "1") (pinfunction "1_1") (pintype "passive"))
      (node (ref "SSR_6DE") (pin "3") (pinfunction "I+_3") (pintype "bidirectional"))
    )
    (net (code "214") (name "Net-(SSR_6FGA-I+)") (class "Default")
      (node (ref "R_6F") (pin "1") (pinfunction "1_1") (pintype "passive"))
      (node (ref "SSR_6FG") (pin "1") (pinfunction "I+_1") (pintype "bidirectional"))
    )
    (net (code "215") (name "Net-(SSR_6FGB-I+)") (class "Default")
      (node (ref "R_6G") (pin "1") (pinfunction "1_1") (pintype "passive"))
      (node (ref "SSR_6FG") (pin "3") (pinfunction "I+_3") (pintype "bidirectional"))
    )
    (net (code "216") (name "Net-(SSR_6HJA-I+)") (class "Default")
      (node (ref "R_6H") (pin "1") (pinfunction "1_1") (pintype "passive"))
      (node (ref "SSR_6HJ") (pin "1") (pinfunction "I+_1") (pintype "bidirectional"))
    )
    (net (code "217") (name "Net-(SSR_6HJB-I+)") (class "Default")
      (node (ref "R_6J") (pin "1") (pinfunction "1_1") (pintype "passive"))
      (node (ref "SSR_6HJ") (pin "3") (pinfunction "I+_3") (pintype "bidirectional"))
    )
    (net (code "218") (name "Net-(SSR_7ABA-I+)") (class "Default")
      (node (ref "R_7A") (pin "1") (pinfunction "1_1") (pintype "passive"))
      (node (ref "SSR_7AB") (pin "1") (pinfunction "I+_1") (pintype "bidirectional"))
    )
    (net (code "219") (name "Net-(SSR_7ABB-I+)") (class "Default")
      (node (ref "R_7B") (pin "1") (pinfunction "1_1") (pintype "passive"))
      (node (ref "SSR_7AB") (pin "3") (pinfunction "I+_3") (pintype "bidirectional"))
    )
    (net (code "220") (name "Net-(SSR_7CDA-I+)") (class "Default")
      (node (ref "R_7C") (pin "1") (pinfunction "1_1") (pintype "passive"))
      (node (ref "SSR_7CD") (pin "1") (pinfunction "I+_1") (pintype "bidirectional"))
    )
    (net (code "221") (name "Net-(SSR_7CDB-I+)") (class "Default")
      (node (ref "R_7D") (pin "1") (pinfunction "1_1") (pintype "passive"))
      (node (ref "SSR_7CD") (pin "3") (pinfunction "I+_3") (pintype "bidirectional"))
    )
    (net (code "222") (name "Net-(SSR_7EFA-I+)") (class "Default")
      (node (ref "R_7E") (pin "1") (pinfunction "1_1") (pintype "passive"))
      (node (ref "SSR_7EF") (pin "1") (pinfunction "I+_1") (pintype "bidirectional"))
    )
    (net (code "223") (name "Net-(SSR_7EFB-I+)") (class "Default")
      (node (ref "R_7F") (pin "1") (pinfunction "1_1") (pintype "passive"))
      (node (ref "SSR_7EF") (pin "3") (pinfunction "I+_3") (pintype "bidirectional"))
    )
    (net (code "224") (name "Net-(SSR_7GHA-I+)") (class "Default")
      (node (ref "R_7G") (pin "1") (pinfunction "1_1") (pintype "passive"))
      (node (ref "SSR_7GH") (pin "1") (pinfunction "I+_1") (pintype "bidirectional"))
    )
    (net (code "225") (name "Net-(SSR_7GHB-I+)") (class "Default")
      (node (ref "R_7H") (pin "1") (pinfunction "1_1") (pintype "passive"))
      (node (ref "SSR_7GH") (pin "3") (pinfunction "I+_3") (pintype "bidirectional"))
    )
    (net (code "226") (name "Net-(SSR_7J/8AA-I+)") (class "Default")
      (node (ref "R_7J") (pin "1") (pinfunction "1_1") (pintype "passive"))
      (node (ref "SSR_7J/8A") (pin "1") (pinfunction "I+_1") (pintype "bidirectional"))
    )
    (net (code "227") (name "Net-(SSR_7J/8AB-I+)") (class "Default")
      (node (ref "R_8A") (pin "1") (pinfunction "1_1") (pintype "passive"))
      (node (ref "SSR_7J/8A") (pin "3") (pinfunction "I+_3") (pintype "bidirectional"))
    )
    (net (code "228") (name "Net-(SSR_8BCA-I+)") (class "Default")
      (node (ref "R_8B") (pin "1") (pinfunction "1_1") (pintype "passive"))
      (node (ref "SSR_8BC") (pin "1") (pinfunction "I+_1") (pintype "bidirectional"))
    )
    (net (code "229") (name "Net-(SSR_8BCB-I+)") (class "Default")
      (node (ref "R_8C") (pin "1") (pinfunction "1_1") (pintype "passive"))
      (node (ref "SSR_8BC") (pin "3") (pinfunction "I+_3") (pintype "bidirectional"))
    )
    (net (code "230") (name "Net-(SSR_8DEA-I+)") (class "Default")
      (node (ref "R_8D") (pin "1") (pinfunction "1_1") (pintype "passive"))
      (node (ref "SSR_8DE") (pin "1") (pinfunction "I+_1") (pintype "bidirectional"))
    )
    (net (code "231") (name "Net-(SSR_8DEB-I+)") (class "Default")
      (node (ref "R_8E") (pin "1") (pinfunction "1_1") (pintype "passive"))
      (node (ref "SSR_8DE") (pin "3") (pinfunction "I+_3") (pintype "bidirectional"))
    )
    (net (code "232") (name "Net-(SSR_8FGA-I+)") (class "Default")
      (node (ref "R_8F") (pin "1") (pinfunction "1_1") (pintype "passive"))
      (node (ref "SSR_8FG") (pin "1") (pinfunction "I+_1") (pintype "bidirectional"))
    )
    (net (code "233") (name "Net-(SSR_8FGB-I+)") (class "Default")
      (node (ref "R_8G") (pin "1") (pinfunction "1_1") (pintype "passive"))
      (node (ref "SSR_8FG") (pin "3") (pinfunction "I+_3") (pintype "bidirectional"))
    )
    (net (code "234") (name "Net-(SSR_8HJA-I+)") (class "Default")
      (node (ref "R_8H") (pin "1") (pinfunction "1_1") (pintype "passive"))
      (node (ref "SSR_8HJ") (pin "1") (pinfunction "I+_1") (pintype "bidirectional"))
    )
    (net (code "235") (name "Net-(SSR_8HJB-I+)") (class "Default")
      (node (ref "R_8J") (pin "1") (pinfunction "1_1") (pintype "passive"))
      (node (ref "SSR_8HJ") (pin "3") (pinfunction "I+_3") (pintype "bidirectional"))
    )
    (net (code "236") (name "REG_CLR") (class "Default")
      (node (ref "ARDUINO_D") (pin "4") (pinfunction "4_4") (pintype "passive"))
      (node (ref "R_CLR") (pin "1") (pinfunction "1_1") (pintype "passive"))
      (node (ref "SHIFTER0") (pin "10") (pinfunction "~{SCLR}_10") (pintype "bidirectional"))
      (node (ref "SHIFTER1") (pin "10") (pinfunction "~{SCLR}_10") (pintype "bidirectional"))
      (node (ref "SHIFTER2") (pin "10") (pinfunction "~{SCLR}_10") (pintype "bidirectional"))
      (node (ref "SHIFTER3") (pin "10") (pinfunction "~{SCLR}_10") (pintype "bidirectional"))
      (node (ref "SHIFTER4") (pin "10") (pinfunction "~{SCLR}_10") (pintype "bidirectional"))
      (node (ref "SHIFTER5") (pin "10") (pinfunction "~{SCLR}_10") (pintype "bidirectional"))
      (node (ref "SHIFTER6") (pin "10") (pinfunction "~{SCLR}_10") (pintype "bidirectional"))
      (node (ref "SHIFTER7") (pin "10") (pinfunction "~{SCLR}_10") (pintype "bidirectional"))
      (node (ref "SHIFTER8") (pin "10") (pinfunction "~{SCLR}_10") (pintype "bidirectional"))
    )
    (net (code "237") (name "REG_LOAD") (class "Default")
      (node (ref "ARDUINO_D") (pin "5") (pinfunction "5_5") (pintype "passive"))
      (node (ref "R_LOAD") (pin "2") (pinfunction "2_2") (pintype "passive"))
      (node (ref "SHIFTER0") (pin "12") (pinfunction "RCK_12") (pintype "bidirectional"))
      (node (ref "SHIFTER1") (pin "12") (pinfunction "RCK_12") (pintype "bidirectional"))
      (node (ref "SHIFTER2") (pin "12") (pinfunction "RCK_12") (pintype "bidirectional"))
      (node (ref "SHIFTER3") (pin "12") (pinfunction "RCK_12") (pintype "bidirectional"))
      (node (ref "SHIFTER4") (pin "12") (pinfunction "RCK_12") (pintype "bidirectional"))
      (node (ref "SHIFTER5") (pin "12") (pinfunction "RCK_12") (pintype "bidirectional"))
      (node (ref "SHIFTER6") (pin "12") (pinfunction "RCK_12") (pintype "bidirectional"))
      (node (ref "SHIFTER7") (pin "12") (pinfunction "RCK_12") (pintype "bidirectional"))
      (node (ref "SHIFTER8") (pin "12") (pinfunction "RCK_12") (pintype "bidirectional"))
    )
    (net (code "238") (name "REG_OE") (class "Default")
      (node (ref "ARDUINO_D") (pin "6") (pinfunction "6_6") (pintype "passive"))
      (node (ref "R_OE") (pin "1") (pinfunction "1_1") (pintype "passive"))
      (node (ref "SHIFTER0") (pin "13") (pinfunction "~{G}_13") (pintype "bidirectional"))
      (node (ref "SHIFTER1") (pin "13") (pinfunction "~{G}_13") (pintype "bidirectional"))
      (node (ref "SHIFTER2") (pin "13") (pinfunction "~{G}_13") (pintype "bidirectional"))
      (node (ref "SHIFTER3") (pin "13") (pinfunction "~{G}_13") (pintype "bidirectional"))
      (node (ref "SHIFTER4") (pin "13") (pinfunction "~{G}_13") (pintype "bidirectional"))
      (node (ref "SHIFTER5") (pin "13") (pinfunction "~{G}_13") (pintype "bidirectional"))
      (node (ref "SHIFTER6") (pin "13") (pinfunction "~{G}_13") (pintype "bidirectional"))
      (node (ref "SHIFTER7") (pin "13") (pinfunction "~{G}_13") (pintype "bidirectional"))
      (node (ref "SHIFTER8") (pin "13") (pinfunction "~{G}_13") (pintype "bidirectional"))
    )
    (net (code "239") (name "SPI_MISO") (class "Default")
      (node (ref "ARDUINO_D") (pin "1") (pinfunction "1_1") (pintype "passive"))
      (node (ref "HEADER_EXT") (pin "4") (pinfunction "4_4") (pintype "passive"))
    )
    (net (code "240") (name "SPI_MOSI") (class "Default")
      (node (ref "ARDUINO_D") (pin "2") (pinfunction "2_2") (pintype "passive"))
      (node (ref "HEADER_EXT") (pin "5") (pinfunction "5_5") (pintype "passive"))
      (node (ref "SHIFTER0") (pin "14") (pinfunction "SI_14") (pintype "bidirectional"))
    )
    (net (code "241") (name "SPI_SCLK") (class "Default")
      (node (ref "ARDUINO_A") (pin "1") (pinfunction "1_1") (pintype "passive"))
      (node (ref "HEADER_EXT") (pin "3") (pinfunction "3_3") (pintype "passive"))
      (node (ref "SHIFTER0") (pin "11") (pinfunction "SCK_11") (pintype "bidirectional"))
      (node (ref "SHIFTER1") (pin "11") (pinfunction "SCK_11") (pintype "bidirectional"))
      (node (ref "SHIFTER2") (pin "11") (pinfunction "SCK_11") (pintype "bidirectional"))
      (node (ref "SHIFTER3") (pin "11") (pinfunction "SCK_11") (pintype "bidirectional"))
      (node (ref "SHIFTER4") (pin "11") (pinfunction "SCK_11") (pintype "bidirectional"))
      (node (ref "SHIFTER5") (pin "11") (pinfunction "SCK_11") (pintype "bidirectional"))
      (node (ref "SHIFTER6") (pin "11") (pinfunction "SCK_11") (pintype "bidirectional"))
      (node (ref "SHIFTER7") (pin "11") (pinfunction "SCK_11") (pintype "bidirectional"))
      (node (ref "SHIFTER8") (pin "11") (pinfunction "SCK_11") (pintype "bidirectional"))
    )
    (net (code "242") (name "SPI_SO1-SI2") (class "Default")
      (node (ref "SHIFTER0") (pin "9") (pinfunction "SO_9") (pintype "bidirectional"))
      (node (ref "SHIFTER1") (pin "14") (pinfunction "SI_14") (pintype "bidirectional"))
    )
    (net (code "243") (name "SPI_SO2-SI3") (class "Default")
      (node (ref "SHIFTER1") (pin "9") (pinfunction "SO_9") (pintype "bidirectional"))
      (node (ref "SHIFTER2") (pin "14") (pinfunction "SI_14") (pintype "bidirectional"))
    )
    (net (code "244") (name "SPI_SO3-SI4") (class "Default")
      (node (ref "SHIFTER2") (pin "9") (pinfunction "SO_9") (pintype "bidirectional"))
      (node (ref "SHIFTER3") (pin "14") (pinfunction "SI_14") (pintype "bidirectional"))
    )
    (net (code "245") (name "SPI_SO4-SI5") (class "Default")
      (node (ref "SHIFTER3") (pin "9") (pinfunction "SO_9") (pintype "bidirectional"))
      (node (ref "SHIFTER4") (pin "14") (pinfunction "SI_14") (pintype "bidirectional"))
    )
    (net (code "246") (name "SPI_SO5-SI6") (class "Default")
      (node (ref "SHIFTER4") (pin "9") (pinfunction "SO_9") (pintype "bidirectional"))
      (node (ref "SHIFTER5") (pin "14") (pinfunction "SI_14") (pintype "bidirectional"))
    )
    (net (code "247") (name "SPI_SO6-SI7") (class "Default")
      (node (ref "SHIFTER5") (pin "9") (pinfunction "SO_9") (pintype "bidirectional"))
      (node (ref "SHIFTER6") (pin "14") (pinfunction "SI_14") (pintype "bidirectional"))
    )
    (net (code "248") (name "SPI_SO7-SI8") (class "Default")
      (node (ref "SHIFTER6") (pin "9") (pinfunction "SO_9") (pintype "bidirectional"))
      (node (ref "SHIFTER7") (pin "14") (pinfunction "SI_14") (pintype "bidirectional"))
    )
    (net (code "249") (name "SPI_SO8-SI9") (class "Default")
      (node (ref "SHIFTER7") (pin "9") (pinfunction "SO_9") (pintype "bidirectional"))
      (node (ref "SHIFTER8") (pin "14") (pinfunction "SI_14") (pintype "bidirectional"))
    )
    (net (code "250") (name "SPI_SS") (class "Default")
      (node (ref "ARDUINO_D") (pin "3") (pinfunction "3_3") (pintype "passive"))
      (node (ref "HEADER_EXT") (pin "6") (pinfunction "6_6") (pintype "passive"))
    )
    (net (code "251") (name "SW-1A") (class "Default")
      (node (ref "SHIFTER0") (pin "15") (pinfunction "Q0_15") (pintype "bidirectional"))
      (node (ref "SSR_1AB") (pin "2") (pinfunction "I-_2") (pintype "bidirectional"))
    )
    (net (code "252") (name "SW-1B") (class "Default")
      (node (ref "SHIFTER0") (pin "1") (pinfunction "Q1_1") (pintype "bidirectional"))
      (node (ref "SSR_1AB") (pin "4") (pinfunction "I-_4") (pintype "bidirectional"))
    )
    (net (code "253") (name "SW-1C") (class "Default")
      (node (ref "SHIFTER0") (pin "2") (pinfunction "Q2_2") (pintype "bidirectional"))
      (node (ref "SSR_1CD") (pin "2") (pinfunction "I-_2") (pintype "bidirectional"))
    )
    (net (code "254") (name "SW-1D") (class "Default")
      (node (ref "SHIFTER0") (pin "3") (pinfunction "Q3_3") (pintype "bidirectional"))
      (node (ref "SSR_1CD") (pin "4") (pinfunction "I-_4") (pintype "bidirectional"))
    )
    (net (code "255") (name "SW-1E") (class "Default")
      (node (ref "SHIFTER0") (pin "4") (pinfunction "Q4_4") (pintype "bidirectional"))
      (node (ref "SSR_1EF") (pin "2") (pinfunction "I-_2") (pintype "bidirectional"))
    )
    (net (code "256") (name "SW-1F") (class "Default")
      (node (ref "SHIFTER0") (pin "5") (pinfunction "Q5_5") (pintype "bidirectional"))
      (node (ref "SSR_1EF") (pin "4") (pinfunction "I-_4") (pintype "bidirectional"))
    )
    (net (code "257") (name "SW-1G") (class "Default")
      (node (ref "SHIFTER0") (pin "6") (pinfunction "Q6_6") (pintype "bidirectional"))
      (node (ref "SSR_1GH") (pin "2") (pinfunction "I-_2") (pintype "bidirectional"))
    )
    (net (code "258") (name "SW-1H") (class "Default")
      (node (ref "SHIFTER0") (pin "7") (pinfunction "Q7_7") (pintype "bidirectional"))
      (node (ref "SSR_1GH") (pin "4") (pinfunction "I-_4") (pintype "bidirectional"))
    )
    (net (code "259") (name "SW-1J") (class "Default")
      (node (ref "SHIFTER1") (pin "15") (pinfunction "Q0_15") (pintype "bidirectional"))
      (node (ref "SSR_1J/2A") (pin "2") (pinfunction "I-_2") (pintype "bidirectional"))
    )
    (net (code "260") (name "SW-2A") (class "Default")
      (node (ref "SHIFTER1") (pin "1") (pinfunction "Q1_1") (pintype "bidirectional"))
      (node (ref "SSR_1J/2A") (pin "4") (pinfunction "I-_4") (pintype "bidirectional"))
    )
    (net (code "261") (name "SW-2B") (class "Default")
      (node (ref "SHIFTER1") (pin "2") (pinfunction "Q2_2") (pintype "bidirectional"))
      (node (ref "SSR_2BC") (pin "2") (pinfunction "I-_2") (pintype "bidirectional"))
    )
    (net (code "262") (name "SW-2C") (class "Default")
      (node (ref "SHIFTER1") (pin "3") (pinfunction "Q3_3") (pintype "bidirectional"))
      (node (ref "SSR_2BC") (pin "4") (pinfunction "I-_4") (pintype "bidirectional"))
    )
    (net (code "263") (name "SW-2D") (class "Default")
      (node (ref "SHIFTER1") (pin "4") (pinfunction "Q4_4") (pintype "bidirectional"))
      (node (ref "SSR_2DE") (pin "2") (pinfunction "I-_2") (pintype "bidirectional"))
    )
    (net (code "264") (name "SW-2E") (class "Default")
      (node (ref "SHIFTER1") (pin "5") (pinfunction "Q5_5") (pintype "bidirectional"))
      (node (ref "SSR_2DE") (pin "4") (pinfunction "I-_4") (pintype "bidirectional"))
    )
    (net (code "265") (name "SW-2F") (class "Default")
      (node (ref "SHIFTER1") (pin "6") (pinfunction "Q6_6") (pintype "bidirectional"))
      (node (ref "SSR_2FG") (pin "2") (pinfunction "I-_2") (pintype "bidirectional"))
    )
    (net (code "266") (name "SW-2G") (class "Default")
      (node (ref "SHIFTER1") (pin "7") (pinfunction "Q7_7") (pintype "bidirectional"))
      (node (ref "SSR_2FG") (pin "4") (pinfunction "I-_4") (pintype "bidirectional"))
    )
    (net (code "267") (name "SW-2H") (class "Default")
      (node (ref "SHIFTER2") (pin "15") (pinfunction "Q0_15") (pintype "bidirectional"))
      (node (ref "SSR_2HJ") (pin "2") (pinfunction "I-_2") (pintype "bidirectional"))
    )
    (net (code "268") (name "SW-2J") (class "Default")
      (node (ref "SHIFTER2") (pin "1") (pinfunction "Q1_1") (pintype "bidirectional"))
      (node (ref "SSR_2HJ") (pin "4") (pinfunction "I-_4") (pintype "bidirectional"))
    )
    (net (code "269") (name "SW-3A") (class "Default")
      (node (ref "SHIFTER2") (pin "2") (pinfunction "Q2_2") (pintype "bidirectional"))
      (node (ref "SSR_3AB") (pin "2") (pinfunction "I-_2") (pintype "bidirectional"))
    )
    (net (code "270") (name "SW-3B") (class "Default")
      (node (ref "SHIFTER2") (pin "3") (pinfunction "Q3_3") (pintype "bidirectional"))
      (node (ref "SSR_3AB") (pin "4") (pinfunction "I-_4") (pintype "bidirectional"))
    )
    (net (code "271") (name "SW-3C") (class "Default")
      (node (ref "SHIFTER2") (pin "4") (pinfunction "Q4_4") (pintype "bidirectional"))
      (node (ref "SSR_3CD") (pin "2") (pinfunction "I-_2") (pintype "bidirectional"))
    )
    (net (code "272") (name "SW-3D") (class "Default")
      (node (ref "SHIFTER2") (pin "5") (pinfunction "Q5_5") (pintype "bidirectional"))
      (node (ref "SSR_3CD") (pin "4") (pinfunction "I-_4") (pintype "bidirectional"))
    )
    (net (code "273") (name "SW-3E") (class "Default")
      (node (ref "SHIFTER2") (pin "6") (pinfunction "Q6_6") (pintype "bidirectional"))
      (node (ref "SSR_3EF") (pin "2") (pinfunction "I-_2") (pintype "bidirectional"))
    )
    (net (code "274") (name "SW-3F") (class "Default")
      (node (ref "SHIFTER2") (pin "7") (pinfunction "Q7_7") (pintype "bidirectional"))
      (node (ref "SSR_3EF") (pin "4") (pinfunction "I-_4") (pintype "bidirectional"))
    )
    (net (code "275") (name "SW-3G") (class "Default")
      (node (ref "SHIFTER3") (pin "15") (pinfunction "Q0_15") (pintype "bidirectional"))
      (node (ref "SSR_3GH") (pin "2") (pinfunction "I-_2") (pintype "bidirectional"))
    )
    (net (code "276") (name "SW-3H") (class "Default")
      (node (ref "SHIFTER3") (pin "1") (pinfunction "Q1_1") (pintype "bidirectional"))
      (node (ref "SSR_3GH") (pin "4") (pinfunction "I-_4") (pintype "bidirectional"))
    )
    (net (code "277") (name "SW-3J") (class "Default")
      (node (ref "SHIFTER3") (pin "2") (pinfunction "Q2_2") (pintype "bidirectional"))
      (node (ref "SSR_3J/4A") (pin "2") (pinfunction "I-_2") (pintype "bidirectional"))
    )
    (net (code "278") (name "SW-4A") (class "Default")
      (node (ref "SHIFTER3") (pin "3") (pinfunction "Q3_3") (pintype "bidirectional"))
      (node (ref "SSR_3J/4A") (pin "4") (pinfunction "I-_4") (pintype "bidirectional"))
    )
    (net (code "279") (name "SW-4B") (class "Default")
      (node (ref "SHIFTER3") (pin "4") (pinfunction "Q4_4") (pintype "bidirectional"))
      (node (ref "SSR_4BC") (pin "2") (pinfunction "I-_2") (pintype "bidirectional"))
    )
    (net (code "280") (name "SW-4C") (class "Default")
      (node (ref "SHIFTER3") (pin "5") (pinfunction "Q5_5") (pintype "bidirectional"))
      (node (ref "SSR_4BC") (pin "4") (pinfunction "I-_4") (pintype "bidirectional"))
    )
    (net (code "281") (name "SW-4D") (class "Default")
      (node (ref "SHIFTER3") (pin "6") (pinfunction "Q6_6") (pintype "bidirectional"))
      (node (ref "SSR_4DE") (pin "2") (pinfunction "I-_2") (pintype "bidirectional"))
    )
    (net (code "282") (name "SW-4E") (class "Default")
      (node (ref "SHIFTER3") (pin "7") (pinfunction "Q7_7") (pintype "bidirectional"))
      (node (ref "SSR_4DE") (pin "4") (pinfunction "I-_4") (pintype "bidirectional"))
    )
    (net (code "283") (name "SW-4F") (class "Default")
      (node (ref "SHIFTER4") (pin "15") (pinfunction "Q0_15") (pintype "bidirectional"))
      (node (ref "SSR_4FG") (pin "2") (pinfunction "I-_2") (pintype "bidirectional"))
    )
    (net (code "284") (name "SW-4G") (class "Default")
      (node (ref "SHIFTER4") (pin "1") (pinfunction "Q1_1") (pintype "bidirectional"))
      (node (ref "SSR_4FG") (pin "4") (pinfunction "I-_4") (pintype "bidirectional"))
    )
    (net (code "285") (name "SW-4H") (class "Default")
      (node (ref "SHIFTER4") (pin "2") (pinfunction "Q2_2") (pintype "bidirectional"))
      (node (ref "SSR_4HJ") (pin "2") (pinfunction "I-_2") (pintype "bidirectional"))
    )
    (net (code "286") (name "SW-4J") (class "Default")
      (node (ref "SHIFTER4") (pin "3") (pinfunction "Q3_3") (pintype "bidirectional"))
      (node (ref "SSR_4HJ") (pin "4") (pinfunction "I-_4") (pintype "bidirectional"))
    )
    (net (code "287") (name "SW-5A") (class "Default")
      (node (ref "SHIFTER4") (pin "4") (pinfunction "Q4_4") (pintype "bidirectional"))
      (node (ref "SSR_5AB") (pin "2") (pinfunction "I-_2") (pintype "bidirectional"))
    )
    (net (code "288") (name "SW-5B") (class "Default")
      (node (ref "SHIFTER4") (pin "5") (pinfunction "Q5_5") (pintype "bidirectional"))
      (node (ref "SSR_5AB") (pin "4") (pinfunction "I-_4") (pintype "bidirectional"))
    )
    (net (code "289") (name "SW-5C") (class "Default")
      (node (ref "SHIFTER4") (pin "6") (pinfunction "Q6_6") (pintype "bidirectional"))
      (node (ref "SSR_5CD") (pin "2") (pinfunction "I-_2") (pintype "bidirectional"))
    )
    (net (code "290") (name "SW-5D") (class "Default")
      (node (ref "SHIFTER4") (pin "7") (pinfunction "Q7_7") (pintype "bidirectional"))
      (node (ref "SSR_5CD") (pin "4") (pinfunction "I-_4") (pintype "bidirectional"))
    )
    (net (code "291") (name "SW-5E") (class "Default")
      (node (ref "SHIFTER5") (pin "15") (pinfunction "Q0_15") (pintype "bidirectional"))
      (node (ref "SSR_5EF") (pin "2") (pinfunction "I-_2") (pintype "bidirectional"))
    )
    (net (code "292") (name "SW-5F") (class "Default")
      (node (ref "SHIFTER5") (pin "1") (pinfunction "Q1_1") (pintype "bidirectional"))
      (node (ref "SSR_5EF") (pin "4") (pinfunction "I-_4") (pintype "bidirectional"))
    )
    (net (code "293") (name "SW-5G") (class "Default")
      (node (ref "SHIFTER5") (pin "2") (pinfunction "Q2_2") (pintype "bidirectional"))
      (node (ref "SSR_5GH") (pin "2") (pinfunction "I-_2") (pintype "bidirectional"))
    )
    (net (code "294") (name "SW-5H") (class "Default")
      (node (ref "SHIFTER5") (pin "3") (pinfunction "Q3_3") (pintype "bidirectional"))
      (node (ref "SSR_5GH") (pin "4") (pinfunction "I-_4") (pintype "bidirectional"))
    )
    (net (code "295") (name "SW-5J") (class "Default")
      (node (ref "SHIFTER5") (pin "4") (pinfunction "Q4_4") (pintype "bidirectional"))
      (node (ref "SSR_5J/6A") (pin "2") (pinfunction "I-_2") (pintype "bidirectional"))
    )
    (net (code "296") (name "SW-6A") (class "Default")
      (node (ref "SHIFTER5") (pin "5") (pinfunction "Q5_5") (pintype "bidirectional"))
      (node (ref "SSR_5J/6A") (pin "4") (pinfunction "I-_4") (pintype "bidirectional"))
    )
    (net (code "297") (name "SW-6B") (class "Default")
      (node (ref "SHIFTER5") (pin "6") (pinfunction "Q6_6") (pintype "bidirectional"))
      (node (ref "SSR_6BC") (pin "2") (pinfunction "I-_2") (pintype "bidirectional"))
    )
    (net (code "298") (name "SW-6C") (class "Default")
      (node (ref "SHIFTER5") (pin "7") (pinfunction "Q7_7") (pintype "bidirectional"))
      (node (ref "SSR_6BC") (pin "4") (pinfunction "I-_4") (pintype "bidirectional"))
    )
    (net (code "299") (name "SW-6D") (class "Default")
      (node (ref "SHIFTER6") (pin "15") (pinfunction "Q0_15") (pintype "bidirectional"))
      (node (ref "SSR_6DE") (pin "2") (pinfunction "I-_2") (pintype "bidirectional"))
    )
    (net (code "300") (name "SW-6E") (class "Default")
      (node (ref "SHIFTER6") (pin "1") (pinfunction "Q1_1") (pintype "bidirectional"))
      (node (ref "SSR_6DE") (pin "4") (pinfunction "I-_4") (pintype "bidirectional"))
    )
    (net (code "301") (name "SW-6F") (class "Default")
      (node (ref "SHIFTER6") (pin "2") (pinfunction "Q2_2") (pintype "bidirectional"))
      (node (ref "SSR_6FG") (pin "2") (pinfunction "I-_2") (pintype "bidirectional"))
    )
    (net (code "302") (name "SW-6G") (class "Default")
      (node (ref "SHIFTER6") (pin "3") (pinfunction "Q3_3") (pintype "bidirectional"))
      (node (ref "SSR_6FG") (pin "4") (pinfunction "I-_4") (pintype "bidirectional"))
    )
    (net (code "303") (name "SW-6H") (class "Default")
      (node (ref "SHIFTER6") (pin "4") (pinfunction "Q4_4") (pintype "bidirectional"))
      (node (ref "SSR_6HJ") (pin "2") (pinfunction "I-_2") (pintype "bidirectional"))
    )
    (net (code "304") (name "SW-6J") (class "Default")
      (node (ref "SHIFTER6") (pin "5") (pinfunction "Q5_5") (pintype "bidirectional"))
      (node (ref "SSR_6HJ") (pin "4") (pinfunction "I-_4") (pintype "bidirectional"))
    )
    (net (code "305") (name "SW-7A") (class "Default")
      (node (ref "SHIFTER6") (pin "6") (pinfunction "Q6_6") (pintype "bidirectional"))
      (node (ref "SSR_7AB") (pin "2") (pinfunction "I-_2") (pintype "bidirectional"))
    )
    (net (code "306") (name "SW-7B") (class "Default")
      (node (ref "SHIFTER6") (pin "7") (pinfunction "Q7_7") (pintype "bidirectional"))
      (node (ref "SSR_7AB") (pin "4") (pinfunction "I-_4") (pintype "bidirectional"))
    )
    (net (code "307") (name "SW-7C") (class "Default")
      (node (ref "SHIFTER7") (pin "15") (pinfunction "Q0_15") (pintype "bidirectional"))
      (node (ref "SSR_7CD") (pin "2") (pinfunction "I-_2") (pintype "bidirectional"))
    )
    (net (code "308") (name "SW-7D") (class "Default")
      (node (ref "SHIFTER7") (pin "1") (pinfunction "Q1_1") (pintype "bidirectional"))
      (node (ref "SSR_7CD") (pin "4") (pinfunction "I-_4") (pintype "bidirectional"))
    )
    (net (code "309") (name "SW-7E") (class "Default")
      (node (ref "SHIFTER7") (pin "2") (pinfunction "Q2_2") (pintype "bidirectional"))
      (node (ref "SSR_7EF") (pin "2") (pinfunction "I-_2") (pintype "bidirectional"))
    )
    (net (code "310") (name "SW-7F") (class "Default")
      (node (ref "SHIFTER7") (pin "3") (pinfunction "Q3_3") (pintype "bidirectional"))
      (node (ref "SSR_7EF") (pin "4") (pinfunction "I-_4") (pintype "bidirectional"))
    )
    (net (code "311") (name "SW-7G") (class "Default")
      (node (ref "SHIFTER7") (pin "4") (pinfunction "Q4_4") (pintype "bidirectional"))
      (node (ref "SSR_7GH") (pin "2") (pinfunction "I-_2") (pintype "bidirectional"))
    )
    (net (code "312") (name "SW-7H") (class "Default")
      (node (ref "SHIFTER7") (pin "5") (pinfunction "Q5_5") (pintype "bidirectional"))
      (node (ref "SSR_7GH") (pin "4") (pinfunction "I-_4") (pintype "bidirectional"))
    )
    (net (code "313") (name "SW-7J") (class "Default")
      (node (ref "SHIFTER7") (pin "6") (pinfunction "Q6_6") (pintype "bidirectional"))
      (node (ref "SSR_7J/8A") (pin "2") (pinfunction "I-_2") (pintype "bidirectional"))
    )
    (net (code "314") (name "SW-8A") (class "Default")
      (node (ref "SHIFTER7") (pin "7") (pinfunction "Q7_7") (pintype "bidirectional"))
      (node (ref "SSR_7J/8A") (pin "4") (pinfunction "I-_4") (pintype "bidirectional"))
    )
    (net (code "315") (name "SW-8B") (class "Default")
      (node (ref "SHIFTER8") (pin "15") (pinfunction "Q0_15") (pintype "bidirectional"))
      (node (ref "SSR_8BC") (pin "2") (pinfunction "I-_2") (pintype "bidirectional"))
    )
    (net (code "316") (name "SW-8C") (class "Default")
      (node (ref "SHIFTER8") (pin "1") (pinfunction "Q1_1") (pintype "bidirectional"))
      (node (ref "SSR_8BC") (pin "4") (pinfunction "I-_4") (pintype "bidirectional"))
    )
    (net (code "317") (name "SW-8D") (class "Default")
      (node (ref "SHIFTER8") (pin "2") (pinfunction "Q2_2") (pintype "bidirectional"))
      (node (ref "SSR_8DE") (pin "2") (pinfunction "I-_2") (pintype "bidirectional"))
    )
    (net (code "318") (name "SW-8E") (class "Default")
      (node (ref "SHIFTER8") (pin "3") (pinfunction "Q3_3") (pintype "bidirectional"))
      (node (ref "SSR_8DE") (pin "4") (pinfunction "I-_4") (pintype "bidirectional"))
    )
    (net (code "319") (name "SW-8F") (class "Default")
      (node (ref "SHIFTER8") (pin "4") (pinfunction "Q4_4") (pintype "bidirectional"))
      (node (ref "SSR_8FG") (pin "2") (pinfunction "I-_2") (pintype "bidirectional"))
    )
    (net (code "320") (name "SW-8G") (class "Default")
      (node (ref "SHIFTER8") (pin "5") (pinfunction "Q5_5") (pintype "bidirectional"))
      (node (ref "SSR_8FG") (pin "4") (pinfunction "I-_4") (pintype "bidirectional"))
    )
    (net (code "321") (name "SW-8H") (class "Default")
      (node (ref "SHIFTER8") (pin "6") (pinfunction "Q6_6") (pintype "bidirectional"))
      (node (ref "SSR_8HJ") (pin "2") (pinfunction "I-_2") (pintype "bidirectional"))
    )
    (net (code "322") (name "SW-8J") (class "Default")
      (node (ref "SHIFTER8") (pin "7") (pinfunction "Q7_7") (pintype "bidirectional"))
      (node (ref "SSR_8HJ") (pin "4") (pinfunction "I-_4") (pintype "bidirectional"))
    )
    (net (code "323") (name "TWI_RST") (class "Default")
      (node (ref "I2C_SWITCH") (pin "3") (pinfunction "~{RESET}_3") (pintype "bidirectional"))
      (node (ref "R_RST") (pin "1") (pinfunction "1_1") (pintype "passive"))
    )
    (net (code "324") (name "TWI_SCL") (class "Default")
      (node (ref "ARDUINO_A") (pin "9") (pinfunction "9_9") (pintype "passive"))
      (node (ref "HEADER_EXT") (pin "8") (pinfunction "8_8") (pintype "passive"))
      (node (ref "I2C_SWITCH") (pin "22") (pinfunction "SCL_22") (pintype "bidirectional"))
      (node (ref "R_SCL") (pin "1") (pinfunction "1_1") (pintype "passive"))
    )
    (net (code "325") (name "TWI_SCL1") (class "Default")
      (node (ref "DRV1") (pin "18") (pinfunction "SCL_18") (pintype "bidirectional"))
      (node (ref "I2C_SWITCH") (pin "5") (pinfunction "SCL0_5") (pintype "bidirectional"))
      (node (ref "R_SCL1") (pin "1") (pinfunction "1_1") (pintype "passive"))
    )
    (net (code "326") (name "TWI_SCL2") (class "Default")
      (node (ref "DRV2") (pin "18") (pinfunction "SCL_18") (pintype "bidirectional"))
      (node (ref "I2C_SWITCH") (pin "7") (pinfunction "SCL1_7") (pintype "bidirectional"))
      (node (ref "R_SCL2") (pin "1") (pinfunction "1_1") (pintype "passive"))
    )
    (net (code "327") (name "TWI_SCL3") (class "Default")
      (node (ref "DRV3") (pin "18") (pinfunction "SCL_18") (pintype "bidirectional"))
      (node (ref "I2C_SWITCH") (pin "9") (pinfunction "SCL2_9") (pintype "bidirectional"))
      (node (ref "R_SCL3") (pin "1") (pinfunction "1_1") (pintype "passive"))
    )
    (net (code "328") (name "TWI_SCL4") (class "Default")
      (node (ref "DRV4") (pin "18") (pinfunction "SCL_18") (pintype "bidirectional"))
      (node (ref "I2C_SWITCH") (pin "11") (pinfunction "SCL3_11") (pintype "bidirectional"))
      (node (ref "R_SCL4") (pin "1") (pinfunction "1_1") (pintype "passive"))
    )
    (net (code "329") (name "TWI_SCL5") (class "Default")
      (node (ref "DRV5") (pin "18") (pinfunction "SCL_18") (pintype "bidirectional"))
      (node (ref "I2C_SWITCH") (pin "14") (pinfunction "SCL4_14") (pintype "bidirectional"))
      (node (ref "R_SCL5") (pin "1") (pinfunction "1_1") (pintype "passive"))
    )
    (net (code "330") (name "TWI_SCL6") (class "Default")
      (node (ref "DRV6") (pin "18") (pinfunction "SCL_18") (pintype "bidirectional"))
      (node (ref "I2C_SWITCH") (pin "16") (pinfunction "SCL5_16") (pintype "bidirectional"))
      (node (ref "R_SCL6") (pin "1") (pinfunction "1_1") (pintype "passive"))
    )
    (net (code "331") (name "TWI_SCL7") (class "Default")
      (node (ref "DRV7") (pin "18") (pinfunction "SCL_18") (pintype "bidirectional"))
      (node (ref "I2C_SWITCH") (pin "18") (pinfunction "SCL6_18") (pintype "bidirectional"))
      (node (ref "R_SCL7") (pin "1") (pinfunction "1_1") (pintype "passive"))
    )
    (net (code "332") (name "TWI_SCL8") (class "Default")
      (node (ref "DRV8") (pin "18") (pinfunction "SCL_18") (pintype "bidirectional"))
      (node (ref "I2C_SWITCH") (pin "20") (pinfunction "SCL7_20") (pintype "bidirectional"))
      (node (ref "R_SCL8") (pin "1") (pinfunction "1_1") (pintype "passive"))
    )
    (net (code "333") (name "TWI_SDA") (class "Default")
      (node (ref "ARDUINO_A") (pin "8") (pinfunction "8_8") (pintype "passive"))
      (node (ref "HEADER_EXT") (pin "7") (pinfunction "7_7") (pintype "passive"))
      (node (ref "I2C_SWITCH") (pin "23") (pinfunction "SDA_23") (pintype "bidirectional"))
      (node (ref "R_SDA") (pin "1") (pinfunction "1_1") (pintype "passive"))
    )
    (net (code "334") (name "TWI_SDA1") (class "Default")
      (node (ref "DRV1") (pin "19") (pinfunction "SDA_19") (pintype "bidirectional"))
      (node (ref "I2C_SWITCH") (pin "4") (pinfunction "SDA0_4") (pintype "bidirectional"))
      (node (ref "R_SDA1") (pin "1") (pinfunction "1_1") (pintype "passive"))
    )
    (net (code "335") (name "TWI_SDA2") (class "Default")
      (node (ref "DRV2") (pin "19") (pinfunction "SDA_19") (pintype "bidirectional"))
      (node (ref "I2C_SWITCH") (pin "6") (pinfunction "SDA1_6") (pintype "bidirectional"))
      (node (ref "R_SDA2") (pin "1") (pinfunction "1_1") (pintype "passive"))
    )
    (net (code "336") (name "TWI_SDA3") (class "Default")
      (node (ref "DRV3") (pin "19") (pinfunction "SDA_19") (pintype "bidirectional"))
      (node (ref "I2C_SWITCH") (pin "8") (pinfunction "SDA2_8") (pintype "bidirectional"))
      (node (ref "R_SDA3") (pin "1") (pinfunction "1_1") (pintype "passive"))
    )
    (net (code "337") (name "TWI_SDA4") (class "Default")
      (node (ref "DRV4") (pin "19") (pinfunction "SDA_19") (pintype "bidirectional"))
      (node (ref "I2C_SWITCH") (pin "10") (pinfunction "SDA3_10") (pintype "bidirectional"))
      (node (ref "R_SDA4") (pin "1") (pinfunction "1_1") (pintype "passive"))
    )
    (net (code "338") (name "TWI_SDA5") (class "Default")
      (node (ref "DRV5") (pin "19") (pinfunction "SDA_19") (pintype "bidirectional"))
      (node (ref "I2C_SWITCH") (pin "13") (pinfunction "SDA4_13") (pintype "bidirectional"))
      (node (ref "R_SDA5") (pin "1") (pinfunction "1_1") (pintype "passive"))
    )
    (net (code "339") (name "TWI_SDA6") (class "Default")
      (node (ref "DRV6") (pin "19") (pinfunction "SDA_19") (pintype "bidirectional"))
      (node (ref "I2C_SWITCH") (pin "15") (pinfunction "SDA5_15") (pintype "bidirectional"))
      (node (ref "R_SDA6") (pin "1") (pinfunction "1_1") (pintype "passive"))
    )
    (net (code "340") (name "TWI_SDA7") (class "Default")
      (node (ref "DRV7") (pin "19") (pinfunction "SDA_19") (pintype "bidirectional"))
      (node (ref "I2C_SWITCH") (pin "17") (pinfunction "SDA6_17") (pintype "bidirectional"))
      (node (ref "R_SDA7") (pin "1") (pinfunction "1_1") (pintype "passive"))
    )
    (net (code "341") (name "TWI_SDA8") (class "Default")
      (node (ref "DRV8") (pin "19") (pinfunction "SDA_19") (pintype "bidirectional"))
      (node (ref "I2C_SWITCH") (pin "19") (pinfunction "SDA7_19") (pintype "bidirectional"))
      (node (ref "R_SDA8") (pin "1") (pinfunction "1_1") (pintype "passive"))
    )
    (net (code "342") (name "TWI_SW0") (class "Default")
      (node (ref "ARDUINO_D") (pin "11") (pinfunction "11_11") (pintype "passive"))
      (node (ref "I2C_SWITCH") (pin "1") (pinfunction "A0_1") (pintype "bidirectional"))
    )
    (net (code "343") (name "TWI_SW1") (class "Default")
      (node (ref "ARDUINO_A") (pin "6") (pinfunction "6_6") (pintype "passive"))
      (node (ref "I2C_SWITCH") (pin "2") (pinfunction "A1_2") (pintype "bidirectional"))
    )
    (net (code "344") (name "TWI_SW2") (class "Default")
      (node (ref "ARDUINO_A") (pin "7") (pinfunction "7_7") (pintype "passive"))
      (node (ref "I2C_SWITCH") (pin "21") (pinfunction "A2_21") (pintype "bidirectional"))
    )
    (net (code "345") (name "UART_RXD") (class "Default")
      (node (ref "ARDUINO_D") (pin "14") (pinfunction "14_14") (pintype "passive"))
      (node (ref "HEADER_EXT") (pin "10") (pinfunction "10_10") (pintype "passive"))
    )
    (net (code "346") (name "UART_TXD") (class "Default")
      (node (ref "ARDUINO_D") (pin "15") (pinfunction "15_15") (pintype "passive"))
      (node (ref "HEADER_EXT") (pin "11") (pinfunction "11_11") (pintype "passive"))
    )
    (net (code "347") (name "UART_XCK") (class "Default")
      (node (ref "ARDUINO_D") (pin "9") (pinfunction "9_9") (pintype "passive"))
      (node (ref "HEADER_EXT") (pin "9") (pinfunction "9_9") (pintype "passive"))
    )
    (net (code "348") (name "unconnected-(ARDUINO_A-Pad2)") (class "Default")
      (node (ref "ARDUINO_A") (pin "2") (pinfunction "2_2") (pintype "passive"))
    )
    (net (code "349") (name "unconnected-(ARDUINO_A-Pad3)") (class "Default")
      (node (ref "ARDUINO_A") (pin "3") (pinfunction "3_3") (pintype "passive"))
    )
    (net (code "350") (name "unconnected-(ARDUINO_A-Pad4)") (class "Default")
      (node (ref "ARDUINO_A") (pin "4") (pinfunction "4_4") (pintype "passive"))
    )
    (net (code "351") (name "unconnected-(ARDUINO_A-Pad5)") (class "Default")
      (node (ref "ARDUINO_A") (pin "5") (pinfunction "5_5") (pintype "passive"))
    )
    (net (code "352") (name "unconnected-(ARDUINO_A-Pad10)") (class "Default")
      (node (ref "ARDUINO_A") (pin "10") (pinfunction "10_10") (pintype "passive"))
    )
    (net (code "353") (name "unconnected-(ARDUINO_A-Pad11)") (class "Default")
      (node (ref "ARDUINO_A") (pin "11") (pinfunction "11_11") (pintype "passive"))
    )
    (net (code "354") (name "unconnected-(ARDUINO_A-Pad12)") (class "Default")
      (node (ref "ARDUINO_A") (pin "12") (pinfunction "12_12") (pintype "passive"))
    )
    (net (code "355") (name "unconnected-(ARDUINO_A-Pad13)") (class "Default")
      (node (ref "ARDUINO_A") (pin "13") (pinfunction "13_13") (pintype "passive"))
    )
    (net (code "356") (name "unconnected-(ARDUINO_D-Pad13)") (class "Default")
      (node (ref "ARDUINO_D") (pin "13") (pinfunction "13_13") (pintype "passive"))
    )
    (net (code "357") (name "unconnected-(AUDIO_IN-Pad13)") (class "Default")
      (node (ref "AUDIO_IN") (pin "13") (pinfunction "13_13") (pintype "passive"))
    )
    (net (code "358") (name "unconnected-(GND_LIFT-T1B-Pad3)") (class "Default")
      (node (ref "GND_LIFT") (pin "3") (pinfunction "T1B_3") (pintype "bidirectional"))
    )
    (net (code "359") (name "unconnected-(GND_LIFT-T2B-Pad4)") (class "Default")
      (node (ref "GND_LIFT") (pin "4") (pinfunction "T2B_4") (pintype "bidirectional"))
    )
    (net (code "360") (name "unconnected-(SHIFTER8A-SO-Pad9)") (class "Default")
      (node (ref "SHIFTER8") (pin "9") (pinfunction "SO_9") (pintype "bidirectional"))
    )
  )
)
